# comando_24V.net
KiCad netlist of a schematic drawn in EAGLE
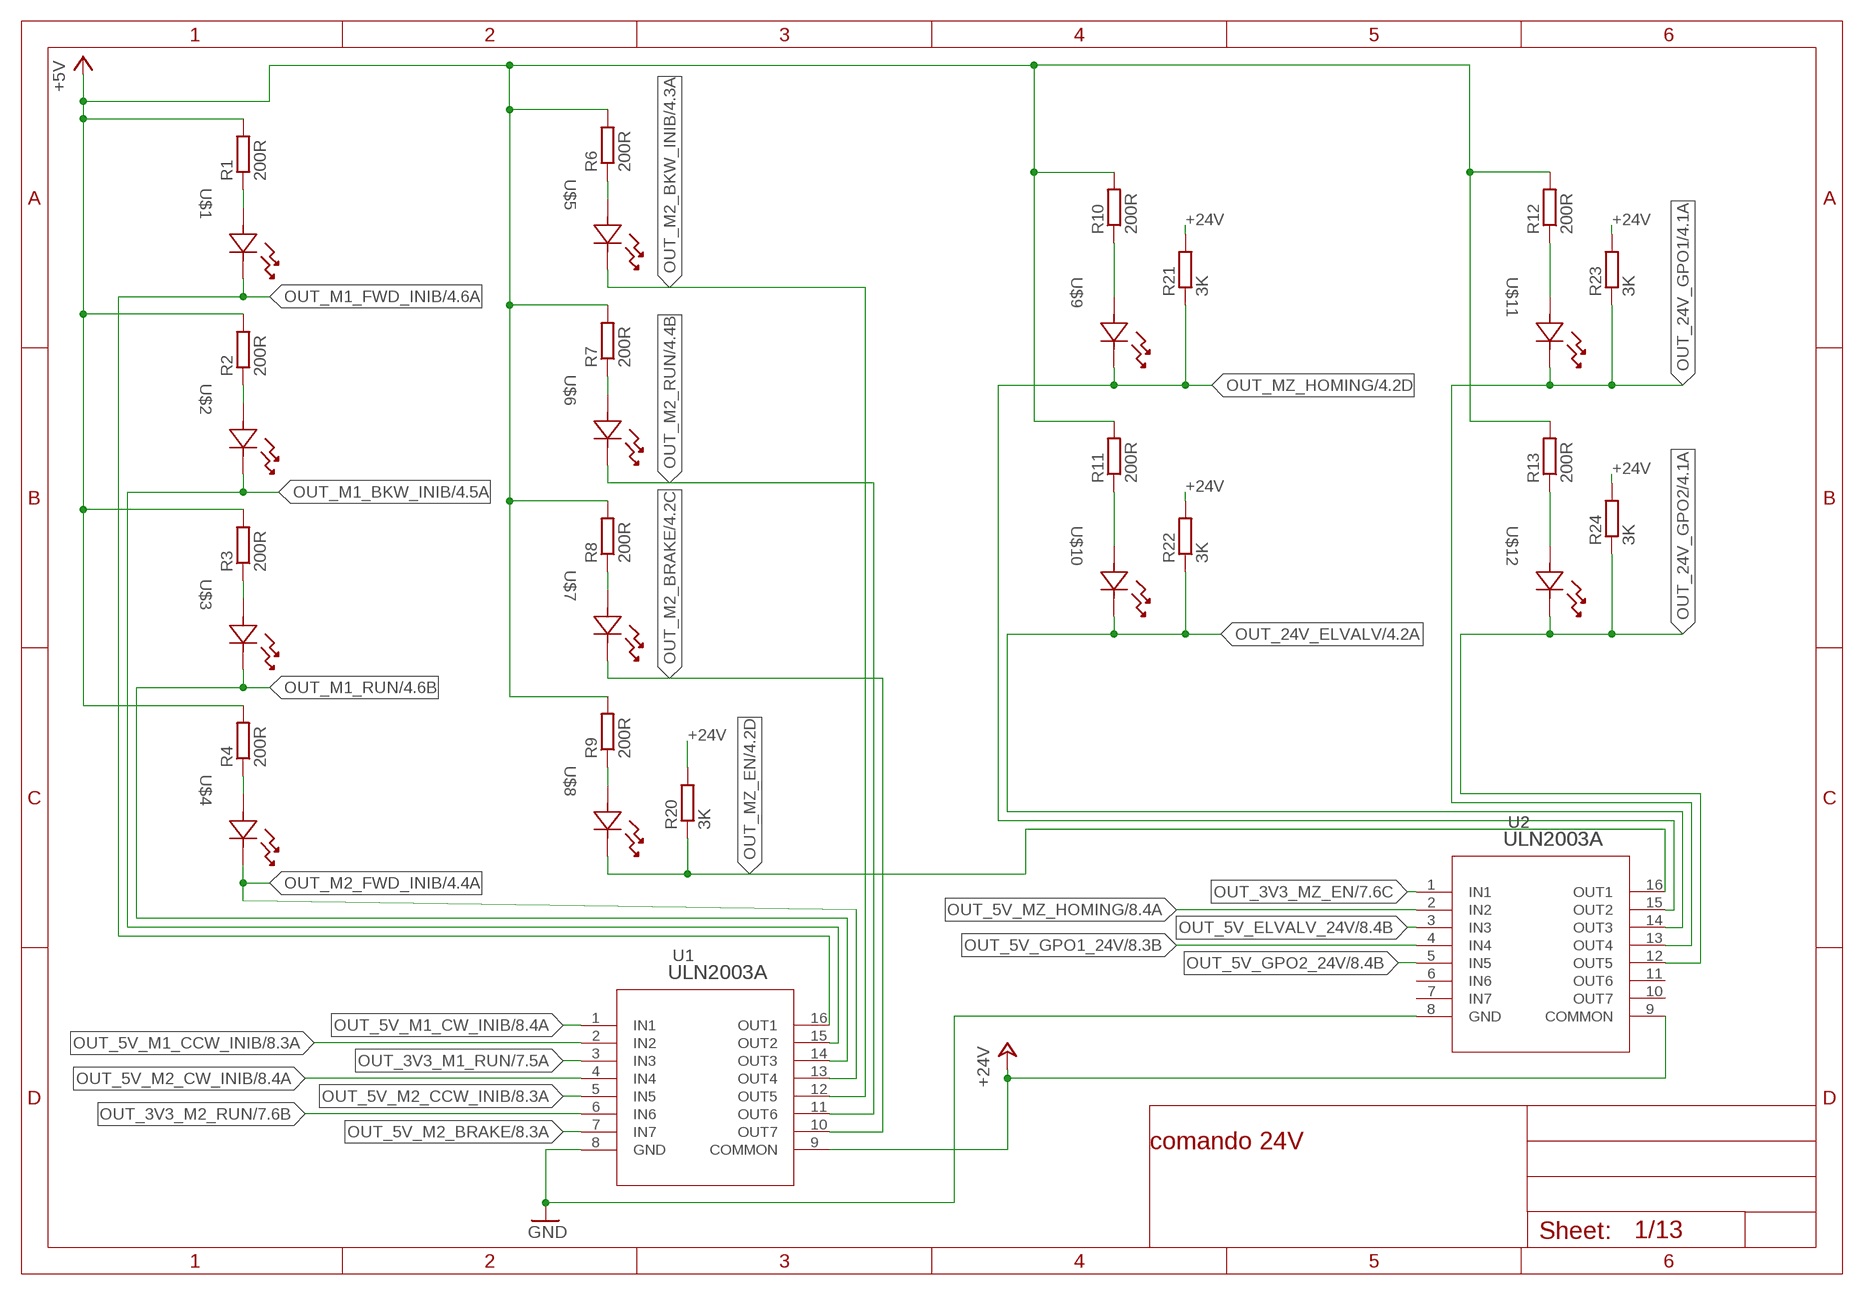
[diagram p0: schematic, sheet 1]
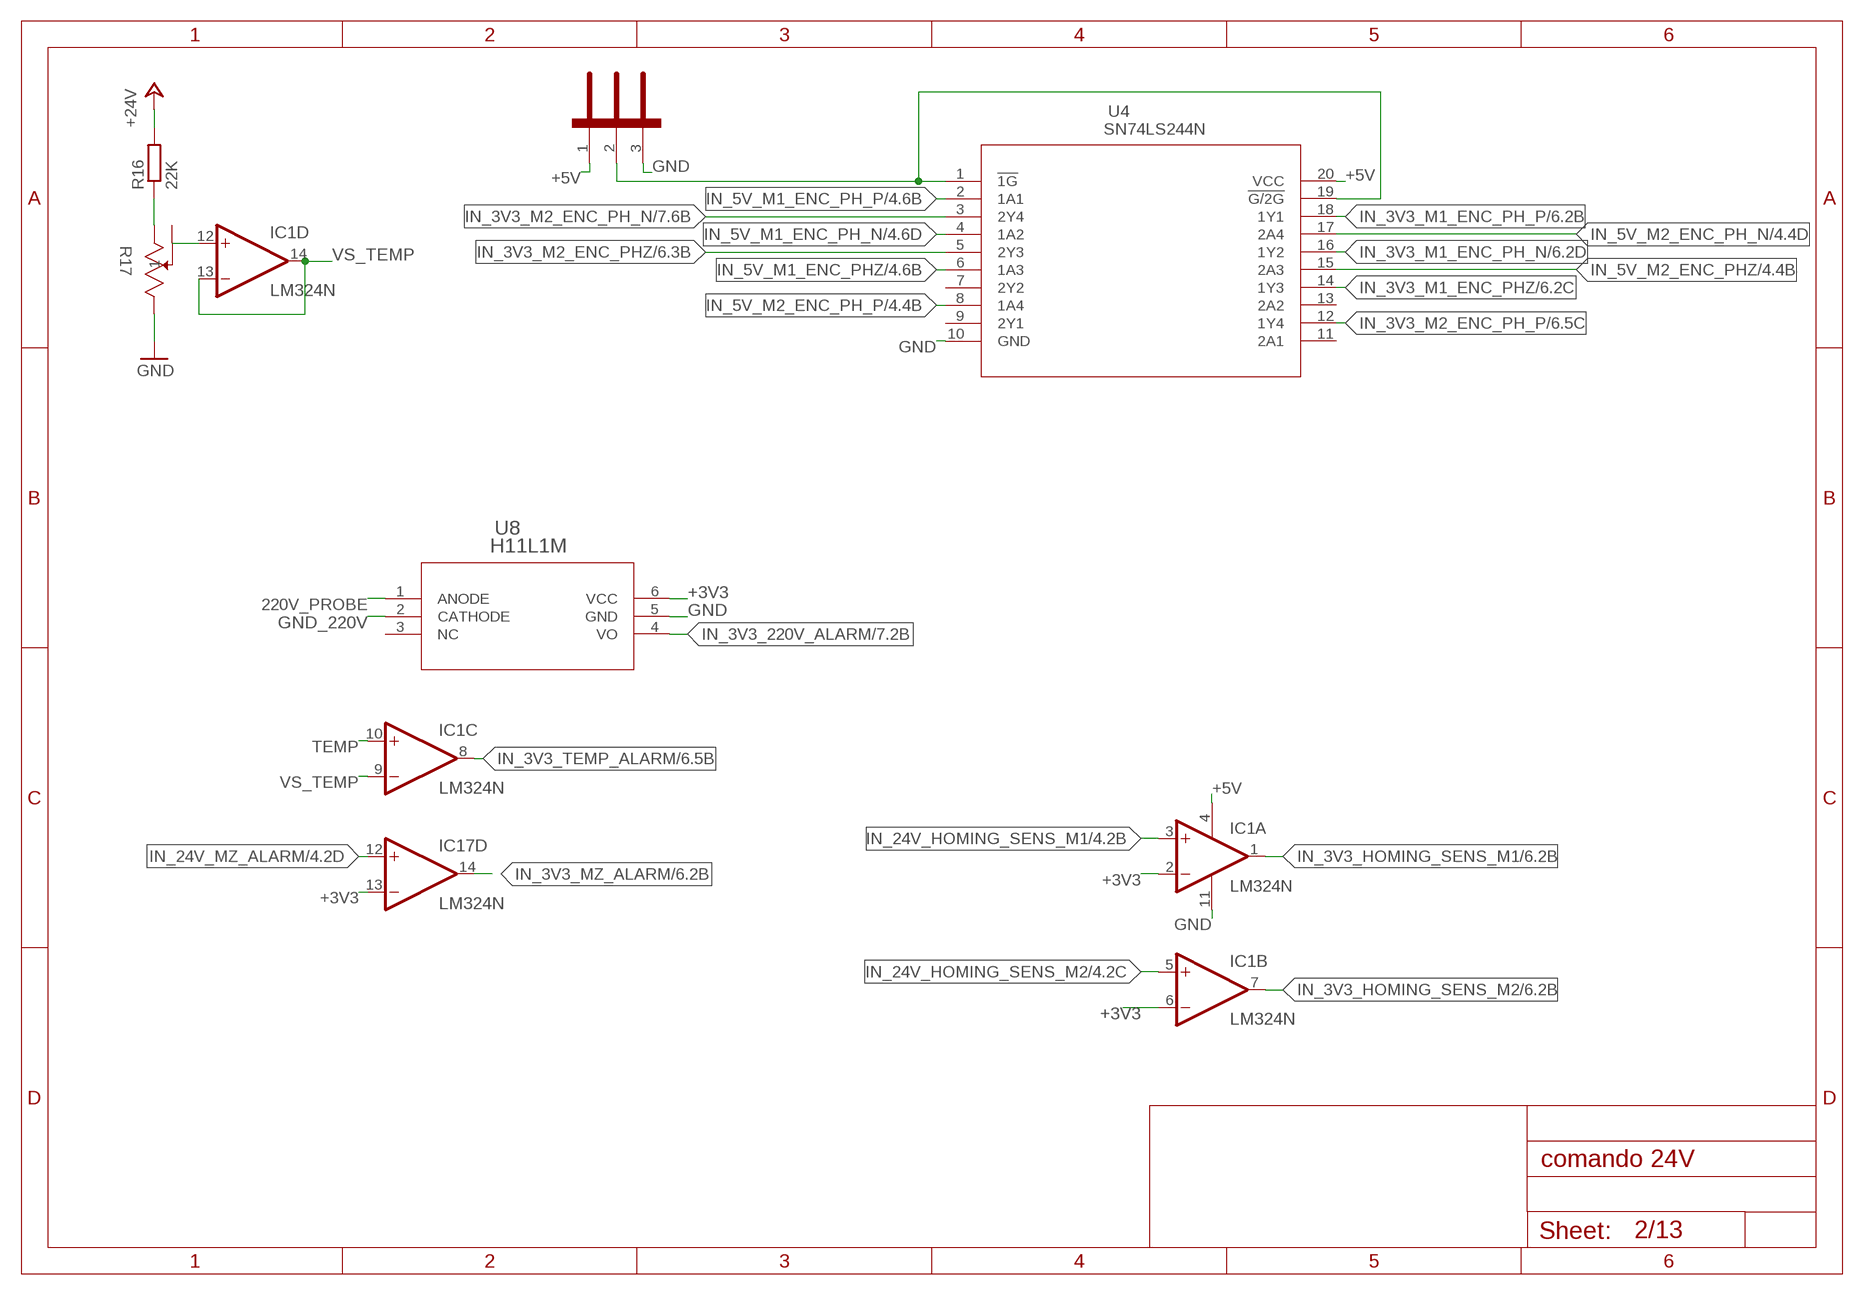
[diagram p1: schematic, sheet 2]
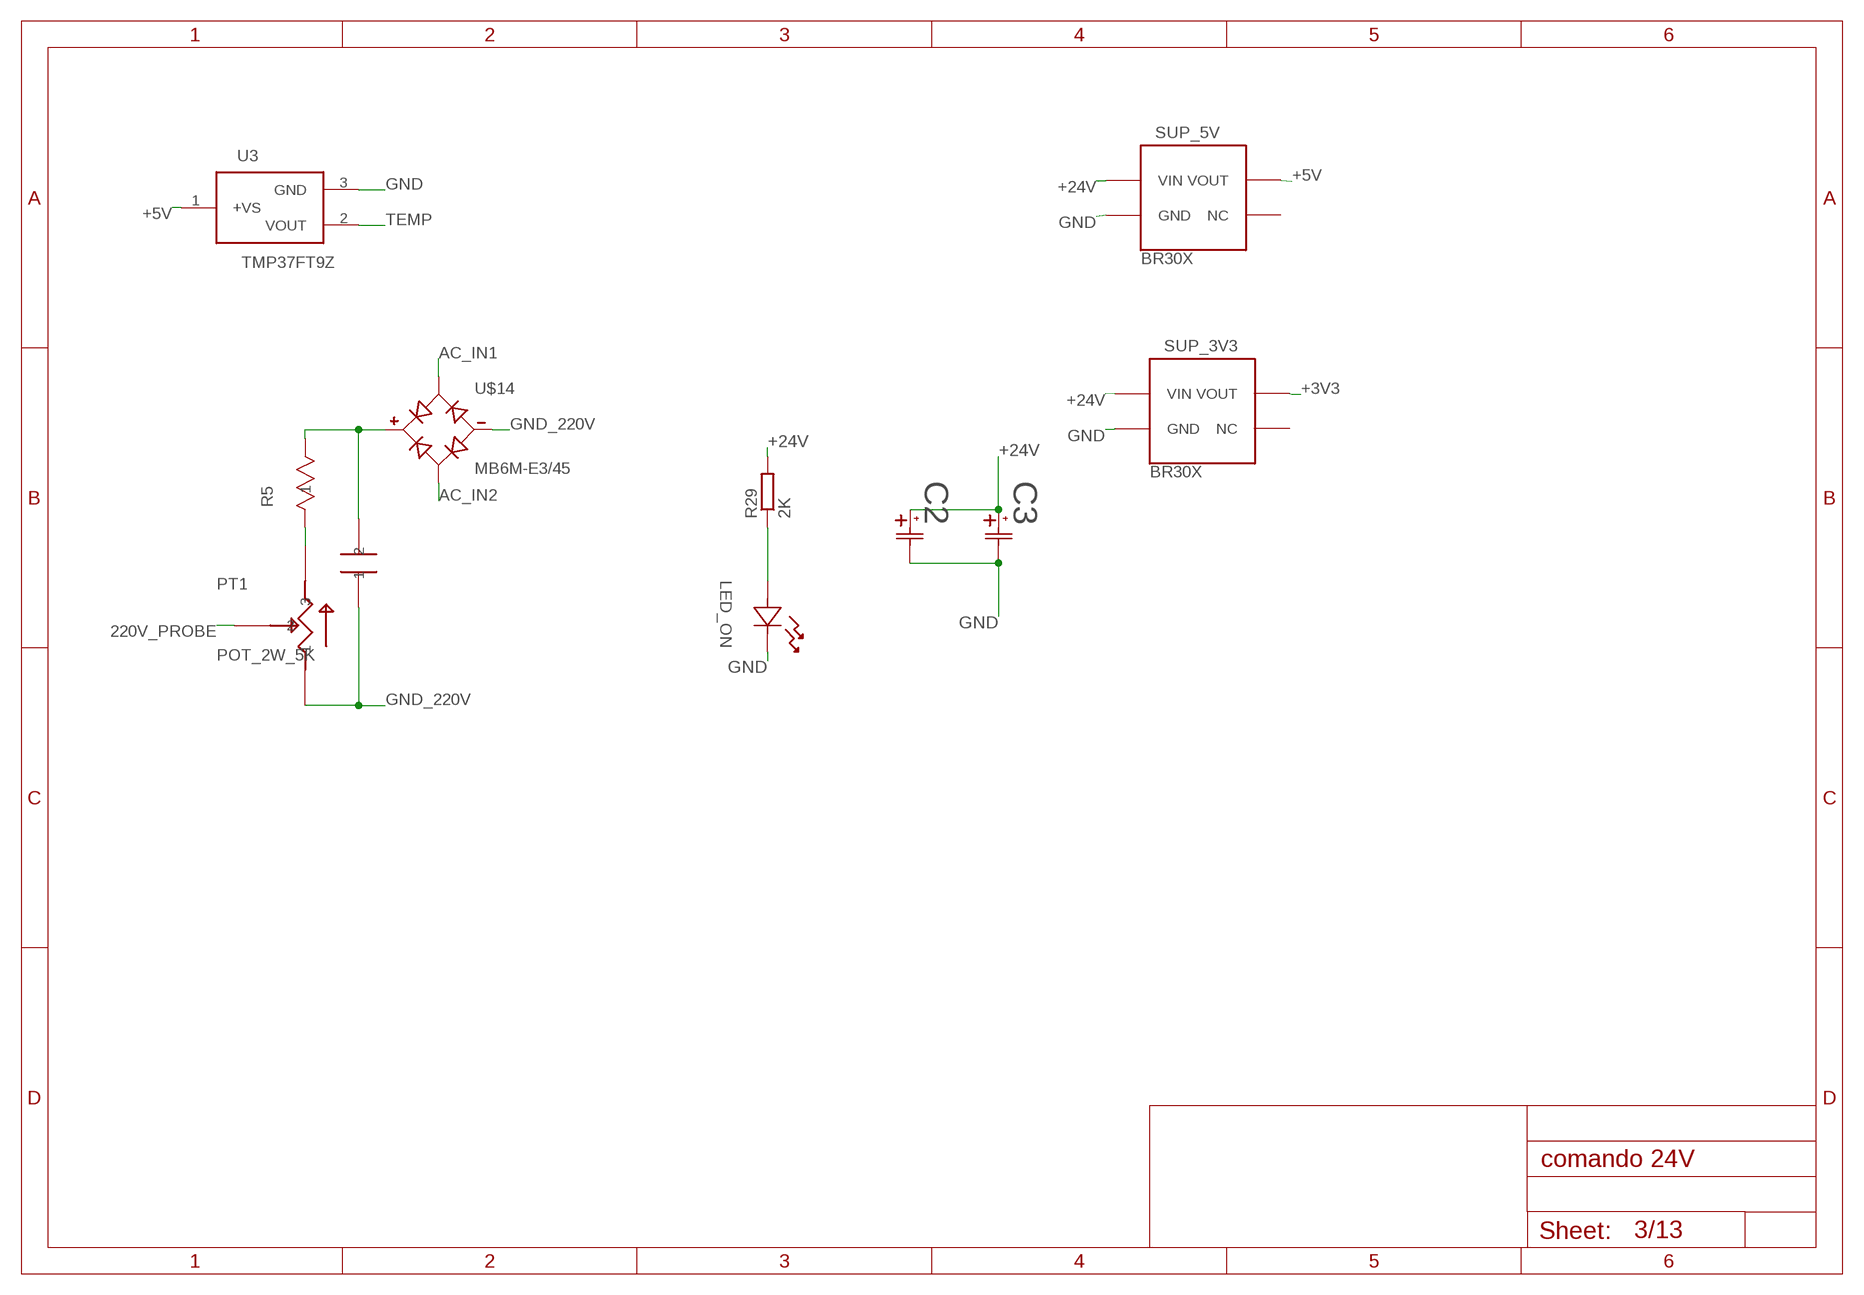
[diagram p2: schematic, sheet 3]
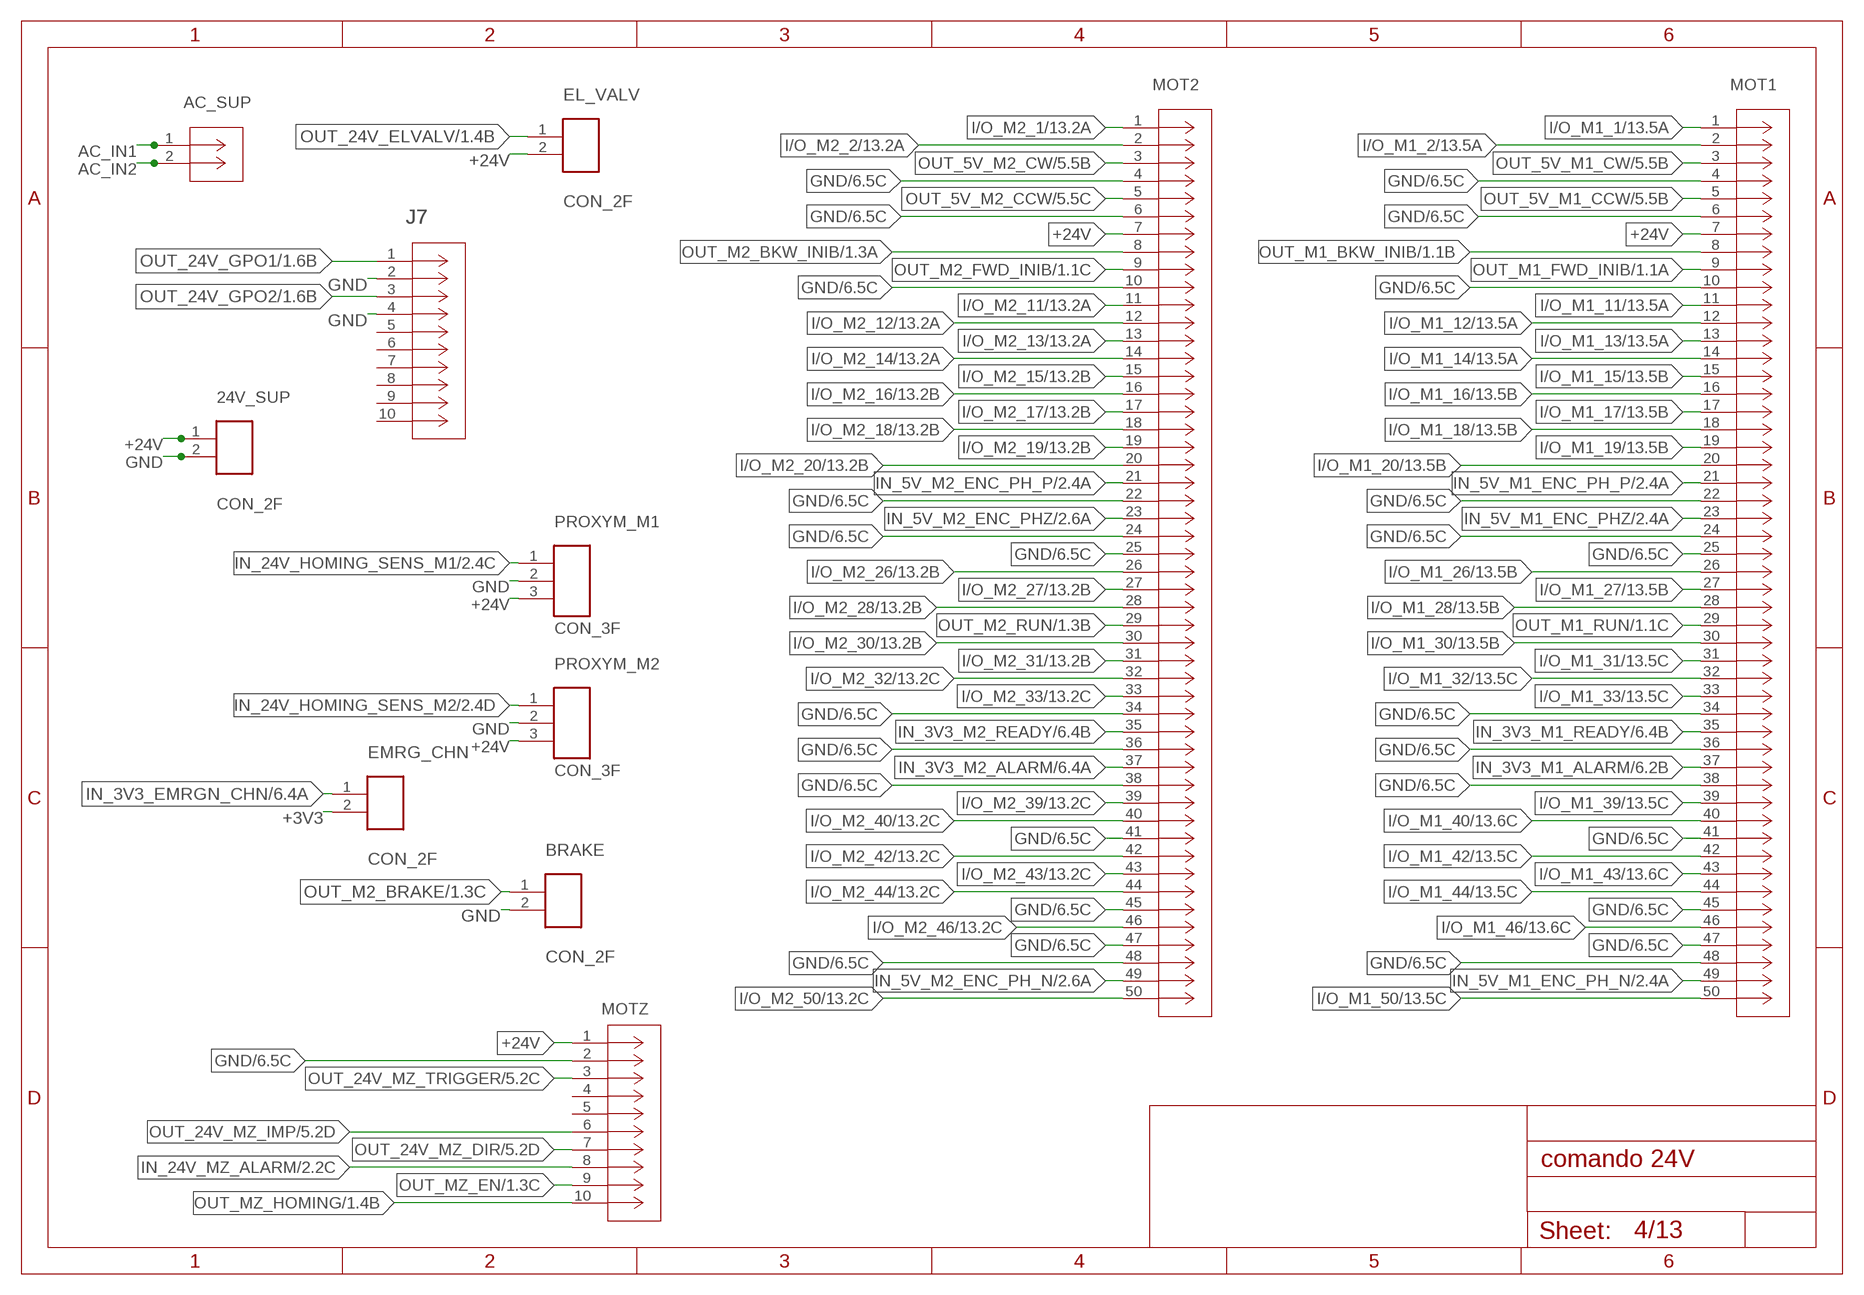
[diagram p3: schematic, sheet 4]
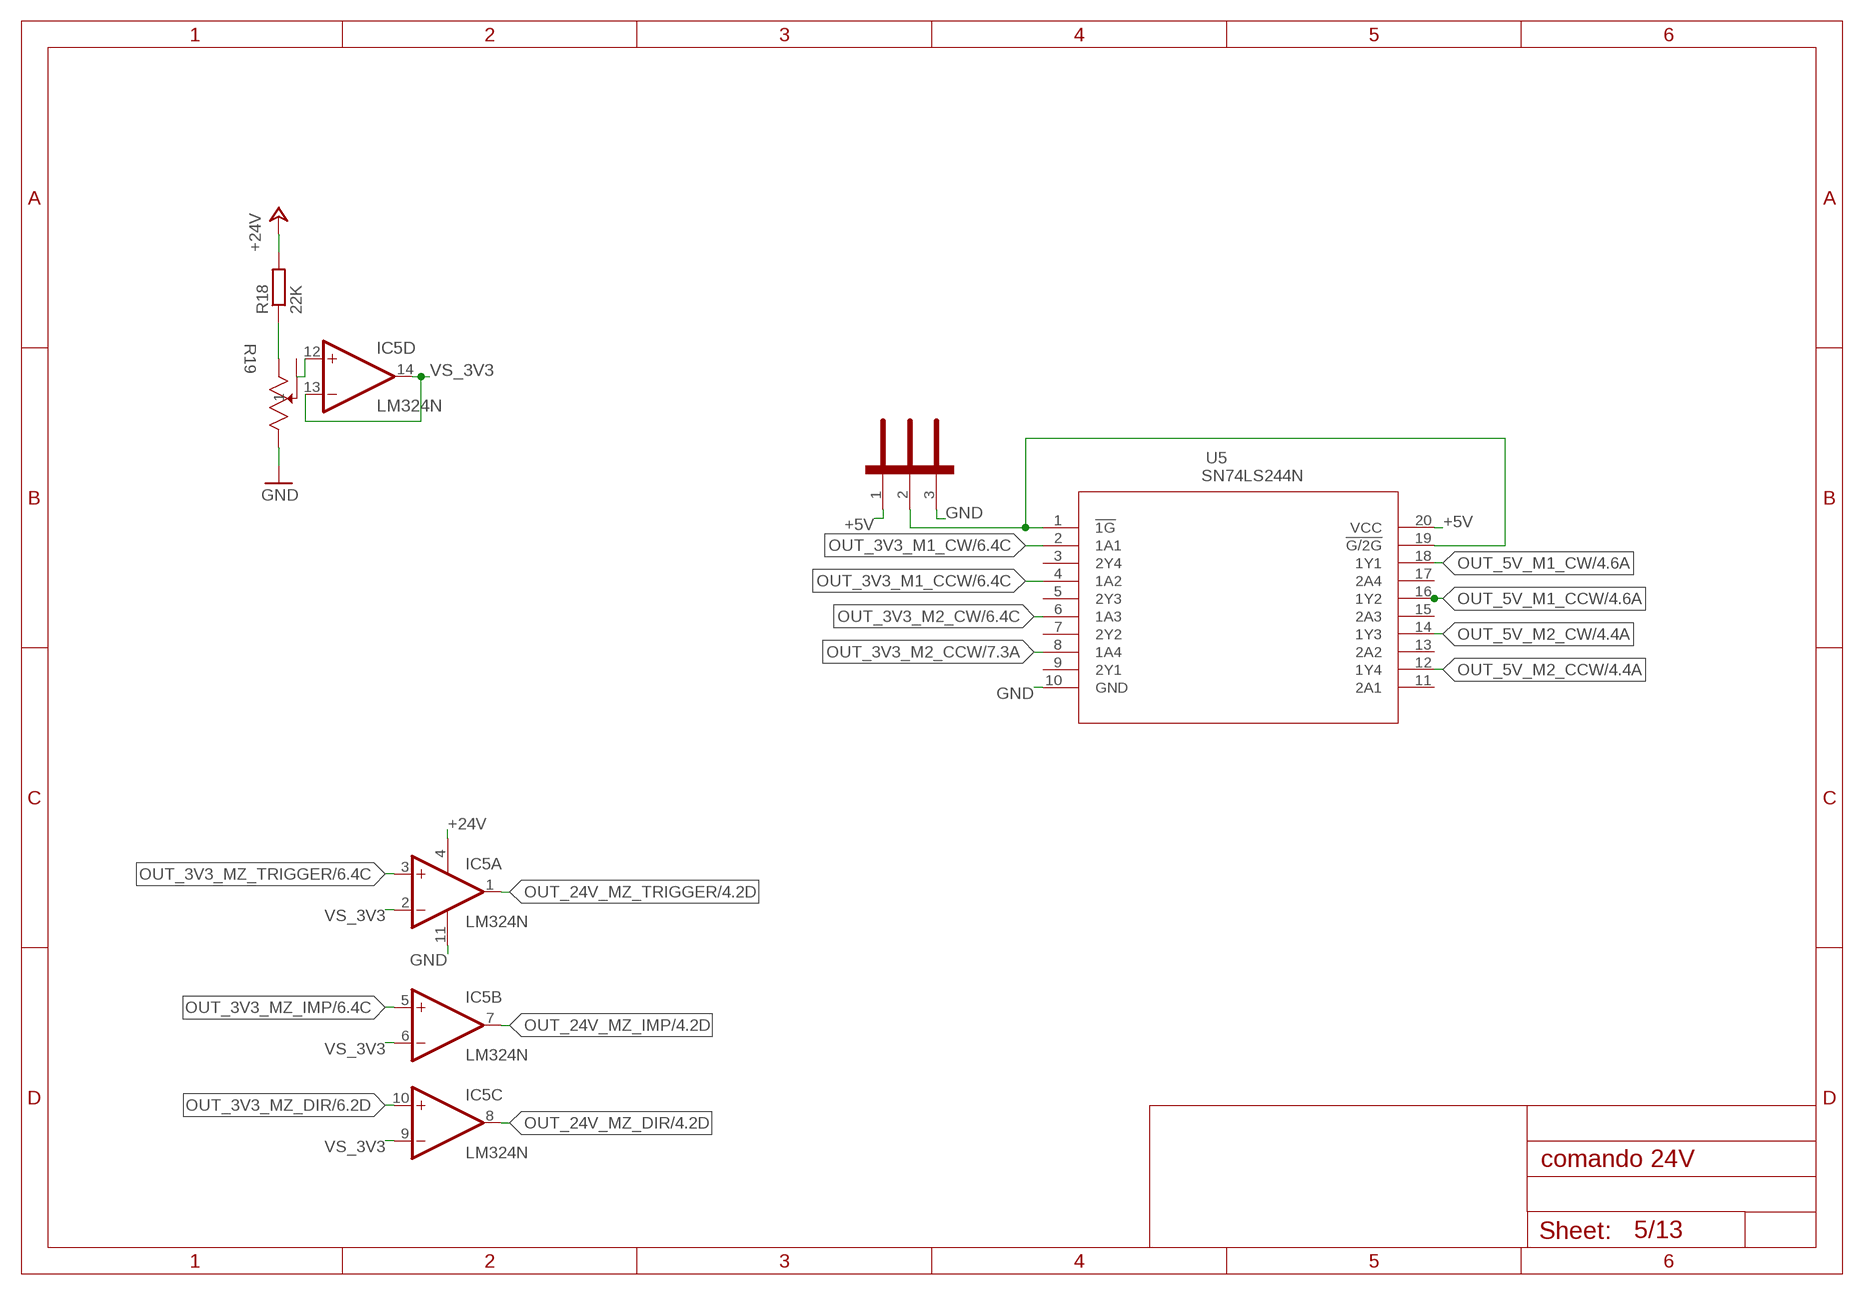
[diagram p4: schematic, sheet 5]
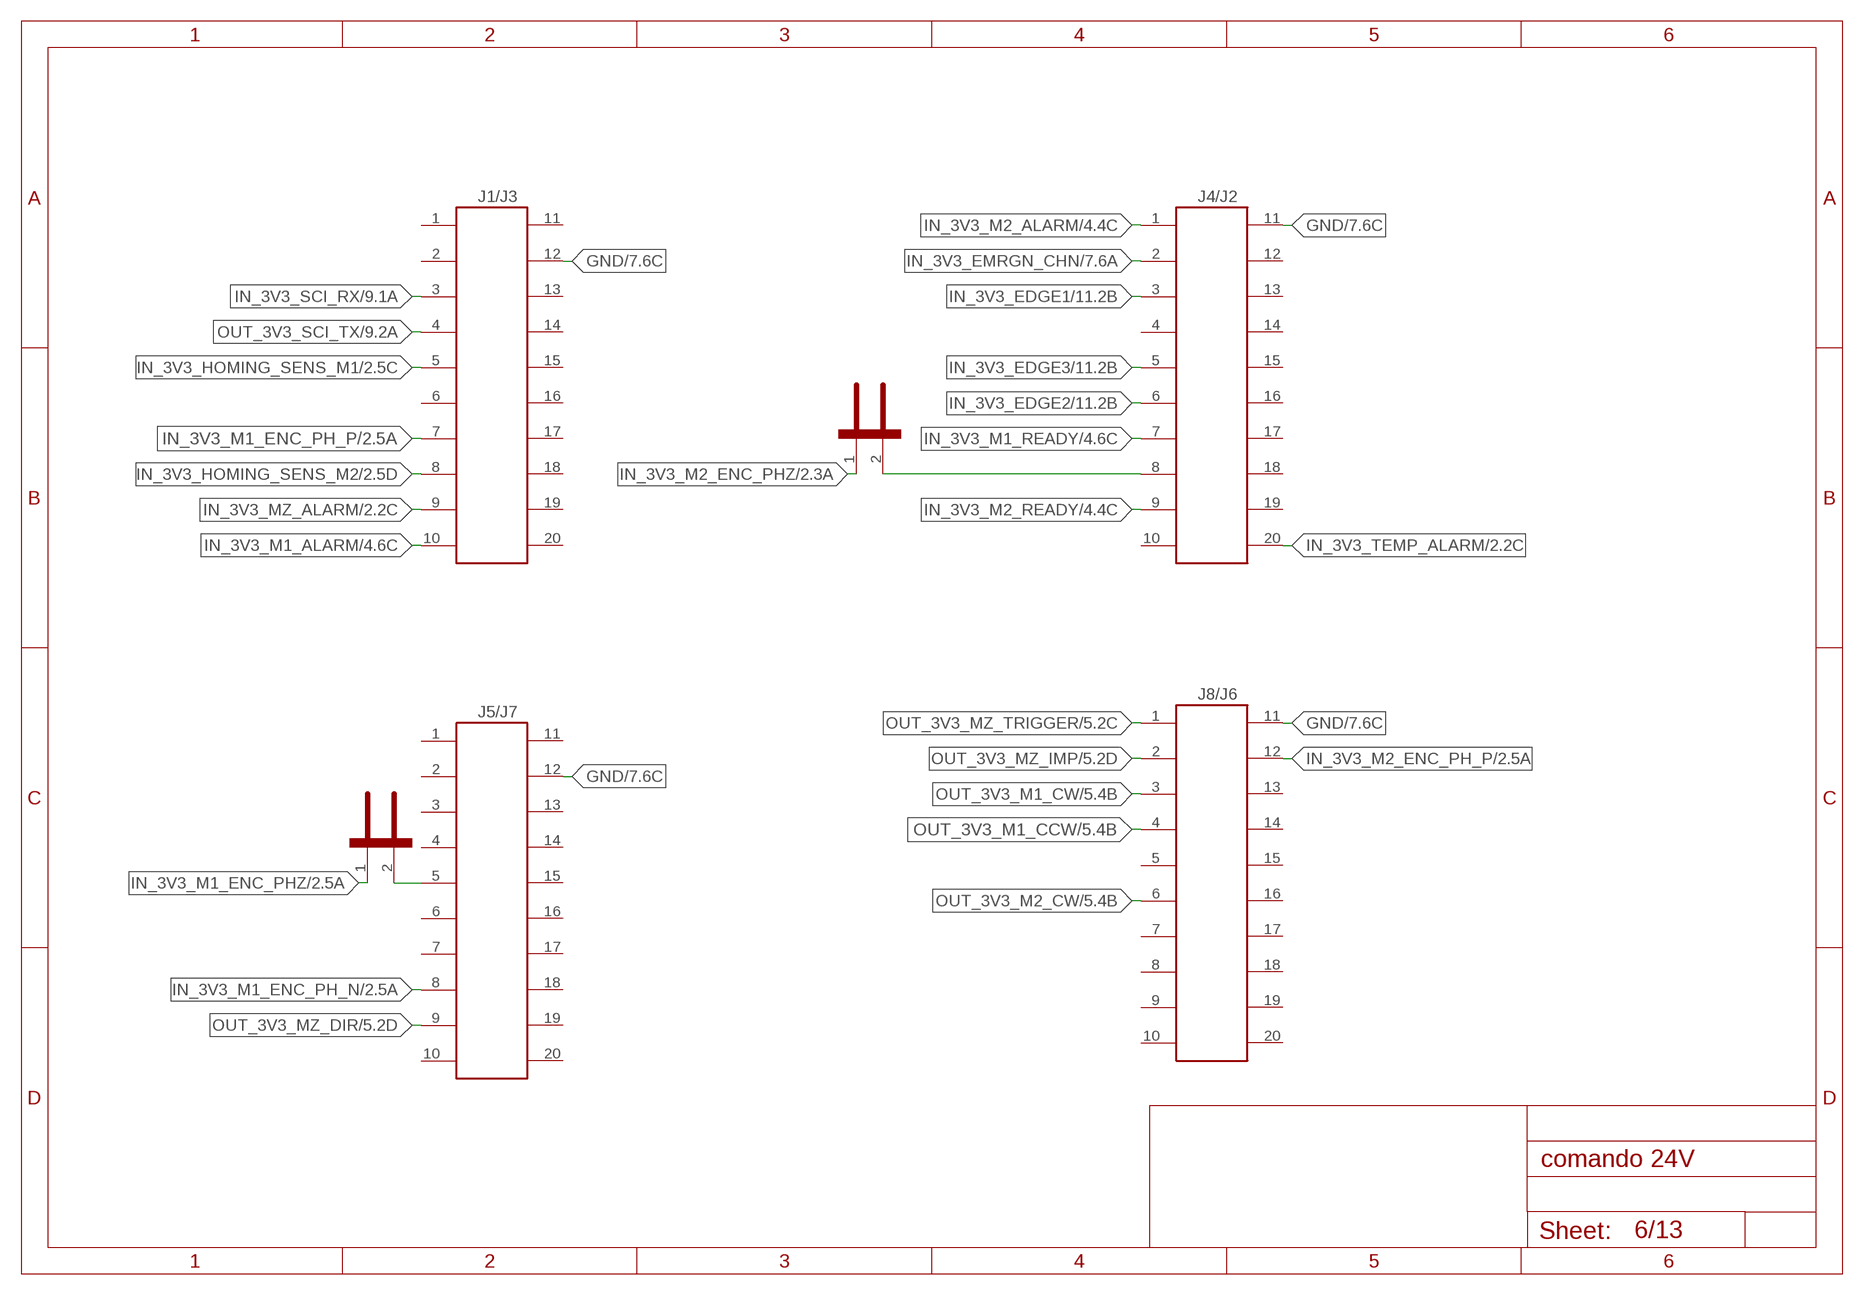
[diagram p5: schematic, sheet 6]
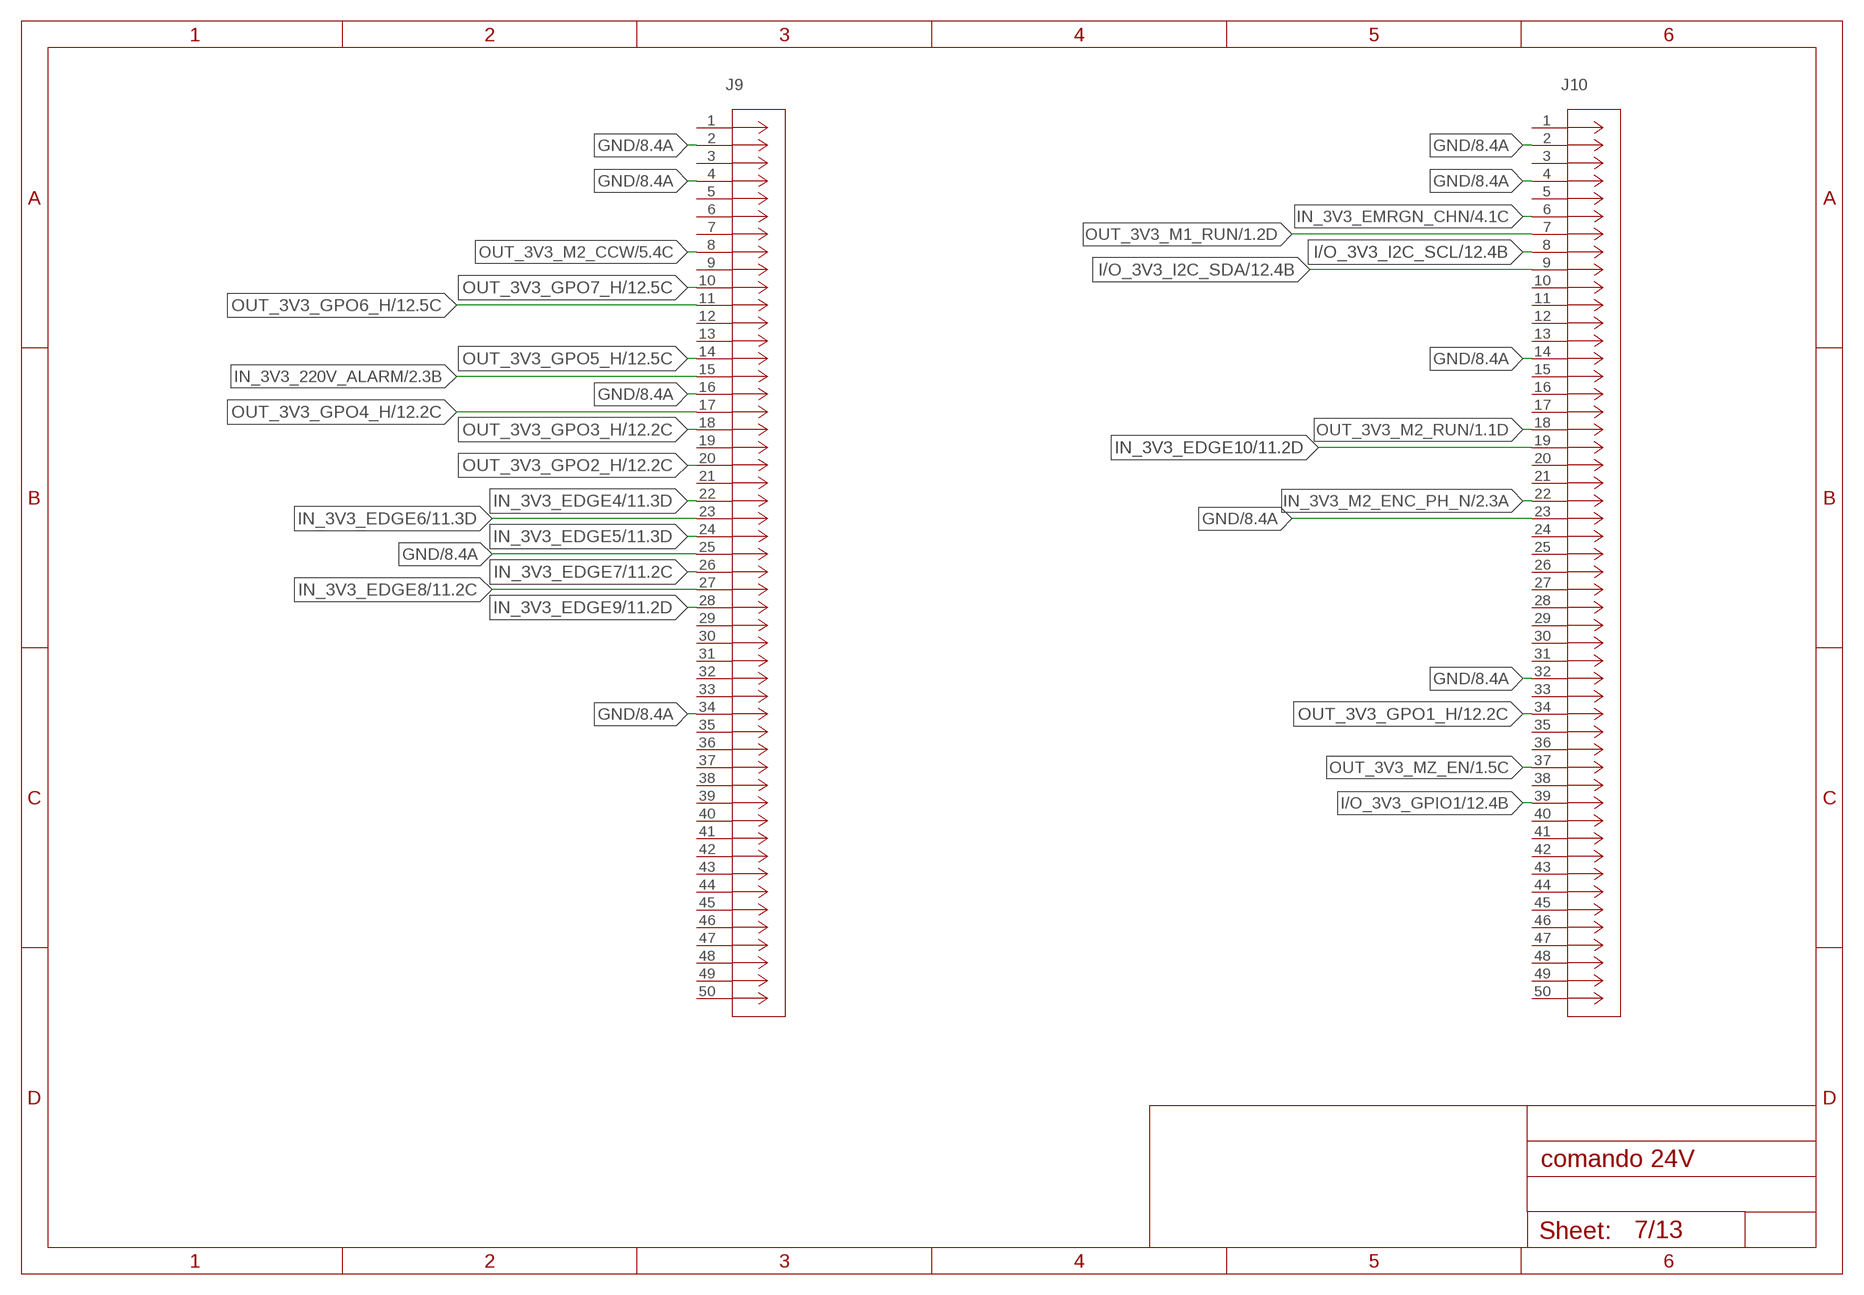
[diagram p6: schematic, sheet 7]
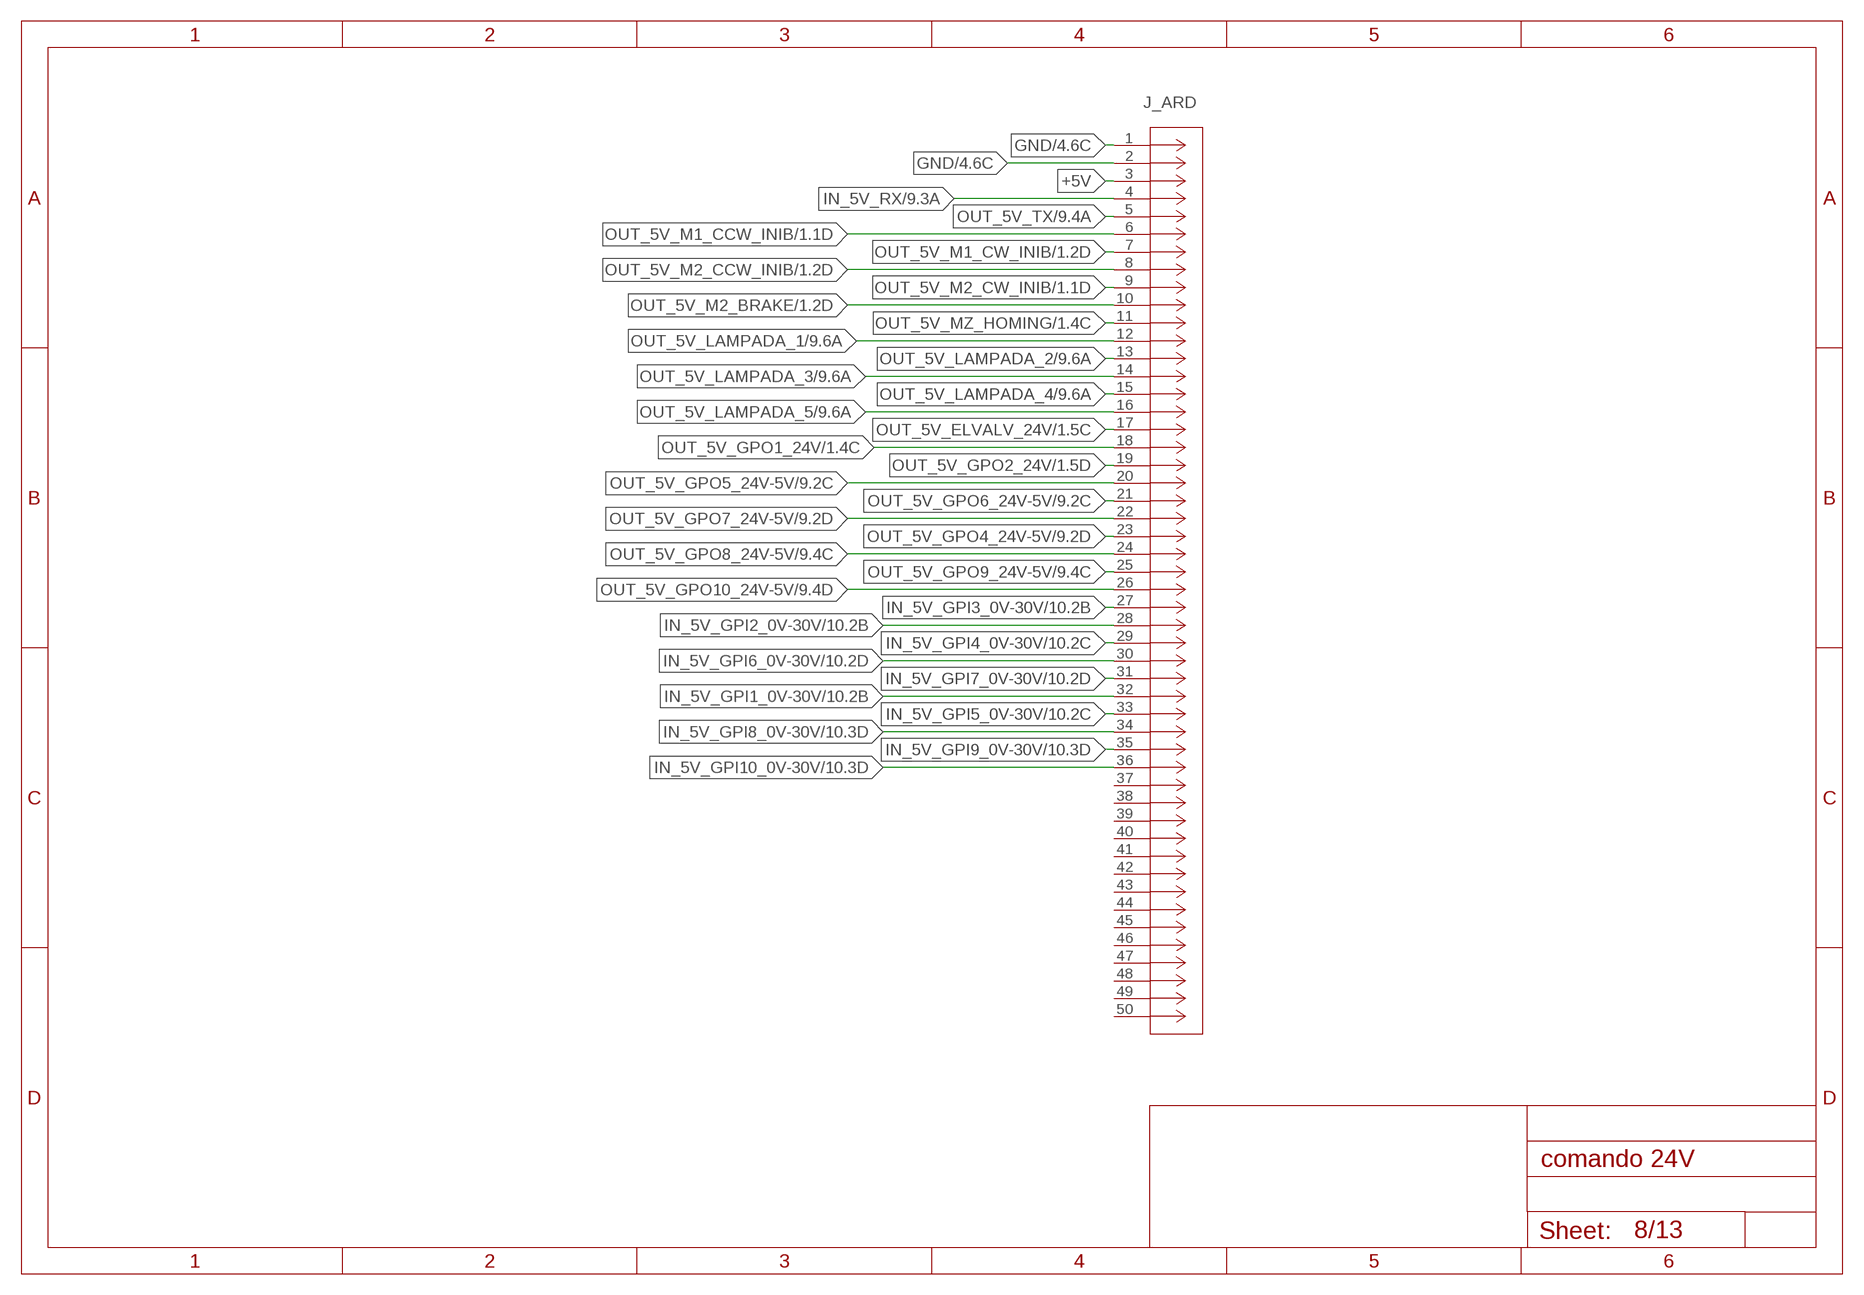
[diagram p7: schematic, sheet 8]
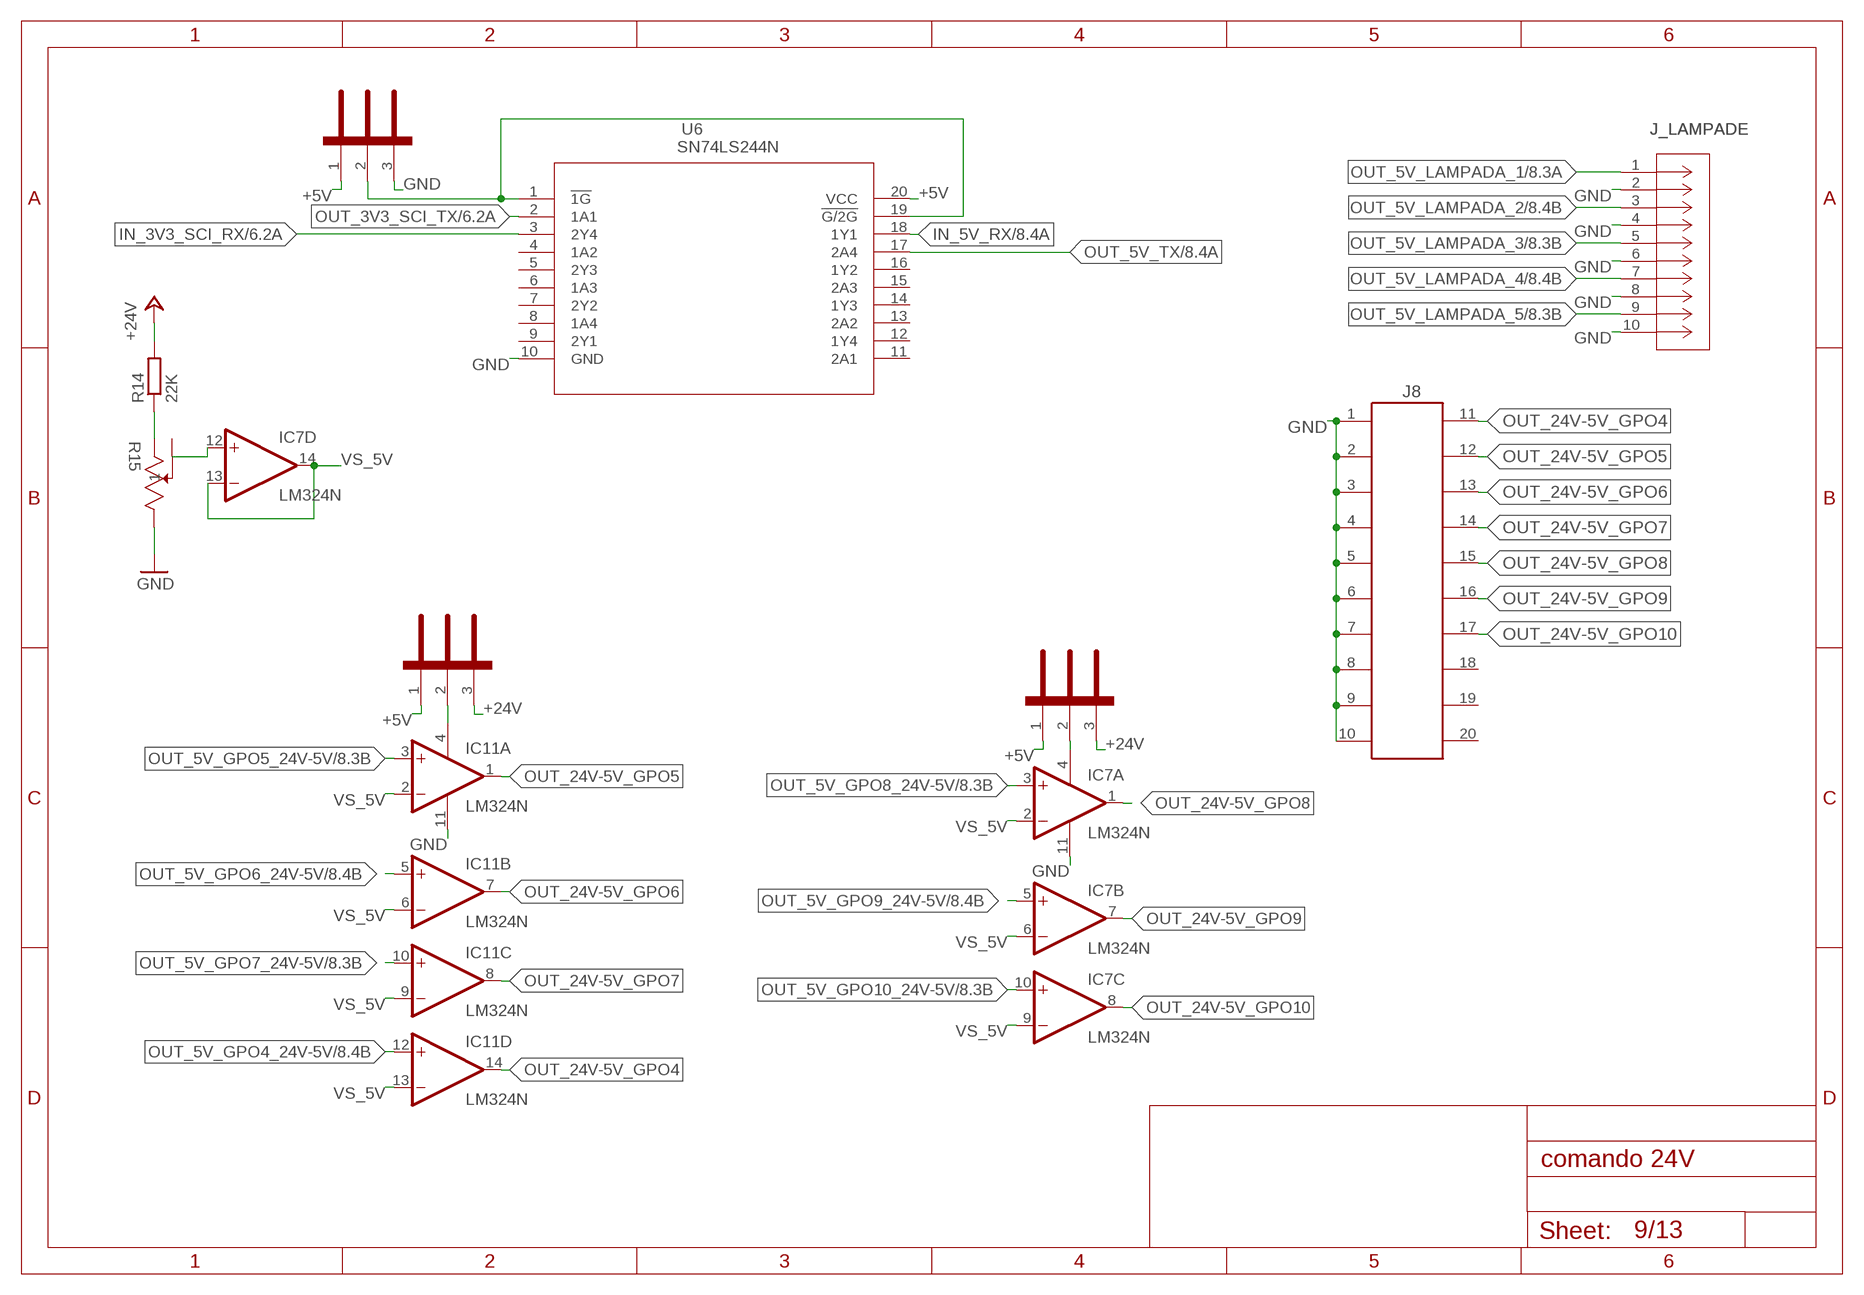
[diagram p8: schematic, sheet 9]
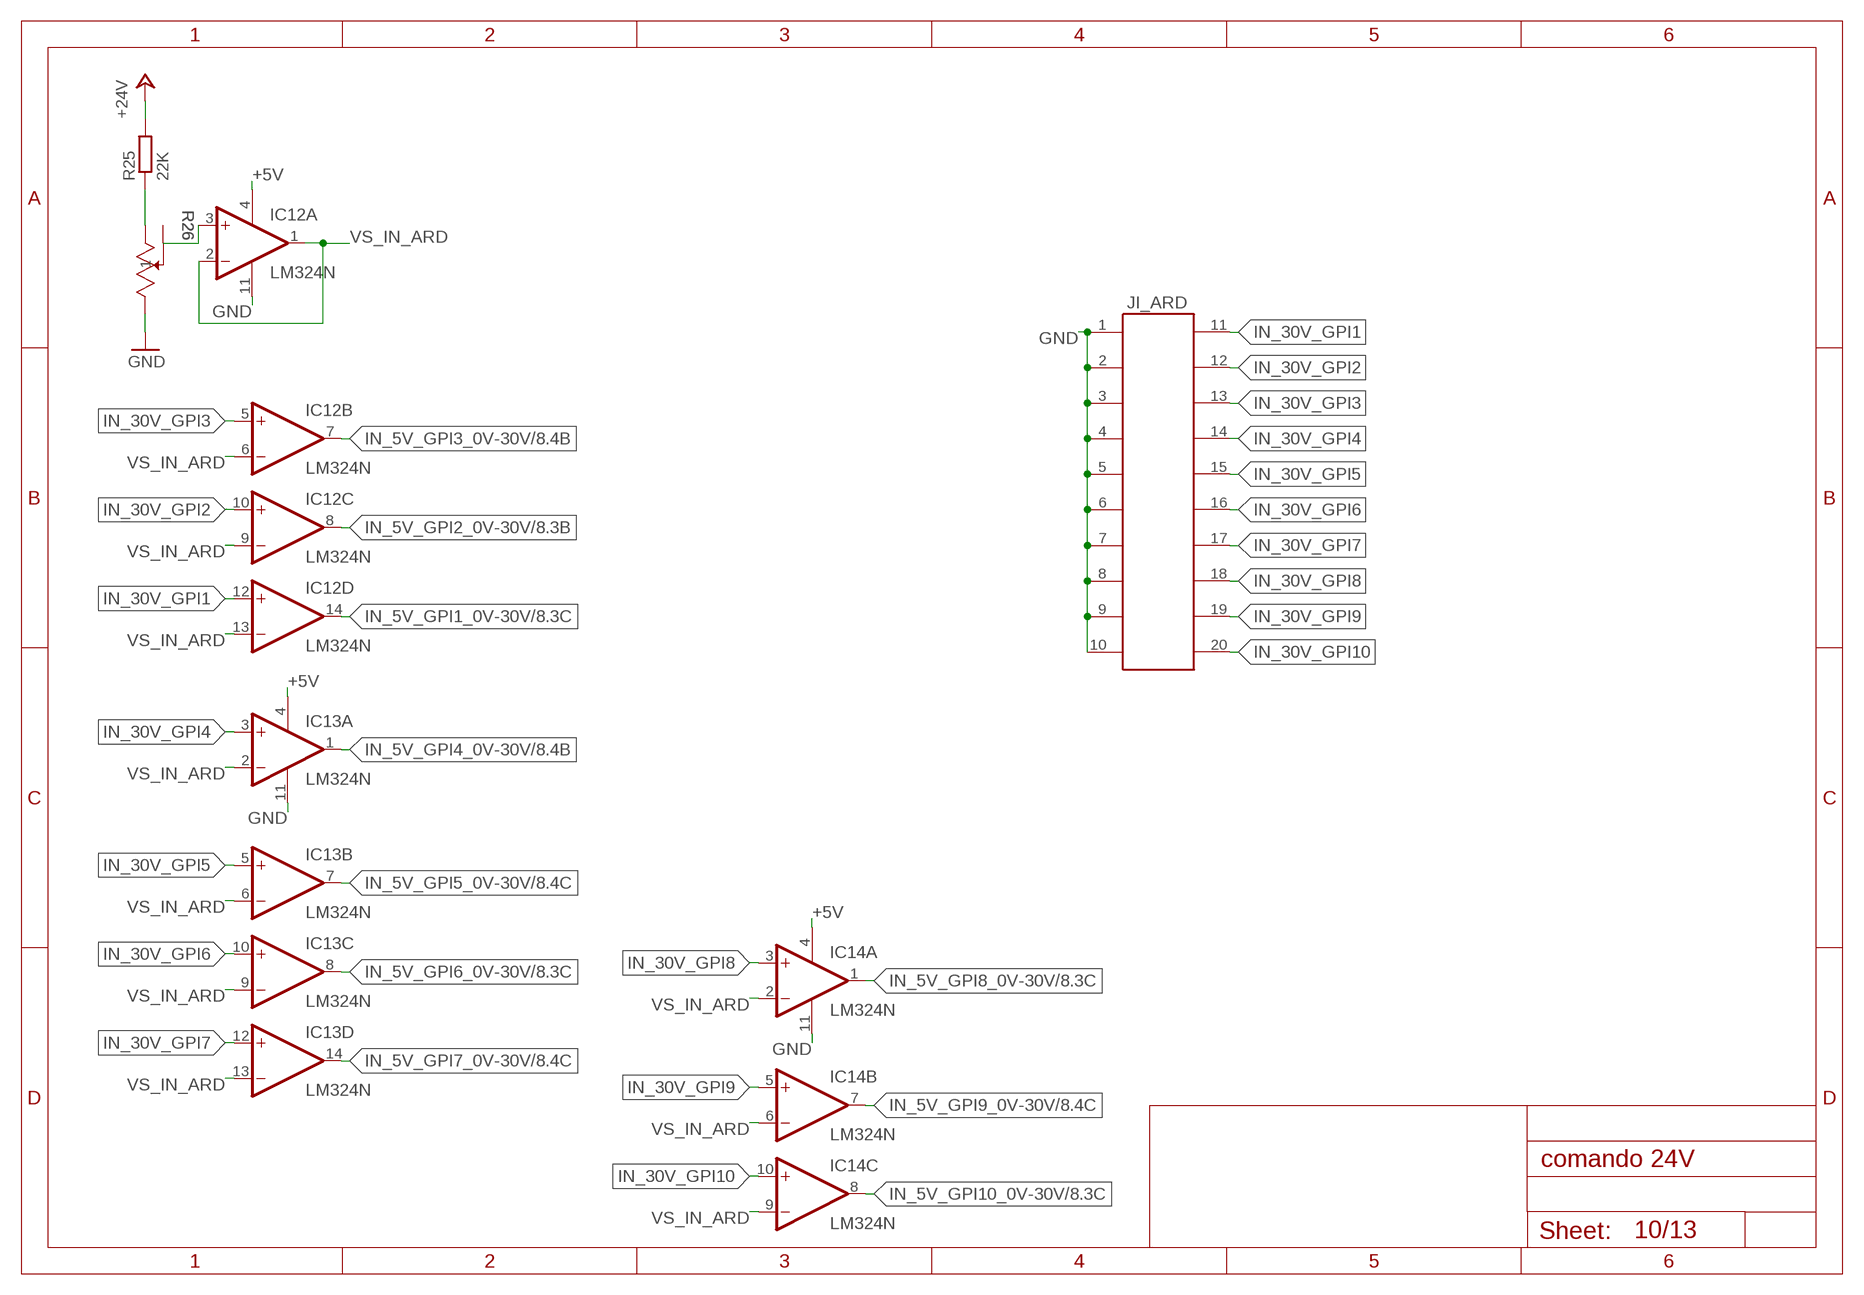
[diagram p9: schematic, sheet 10]
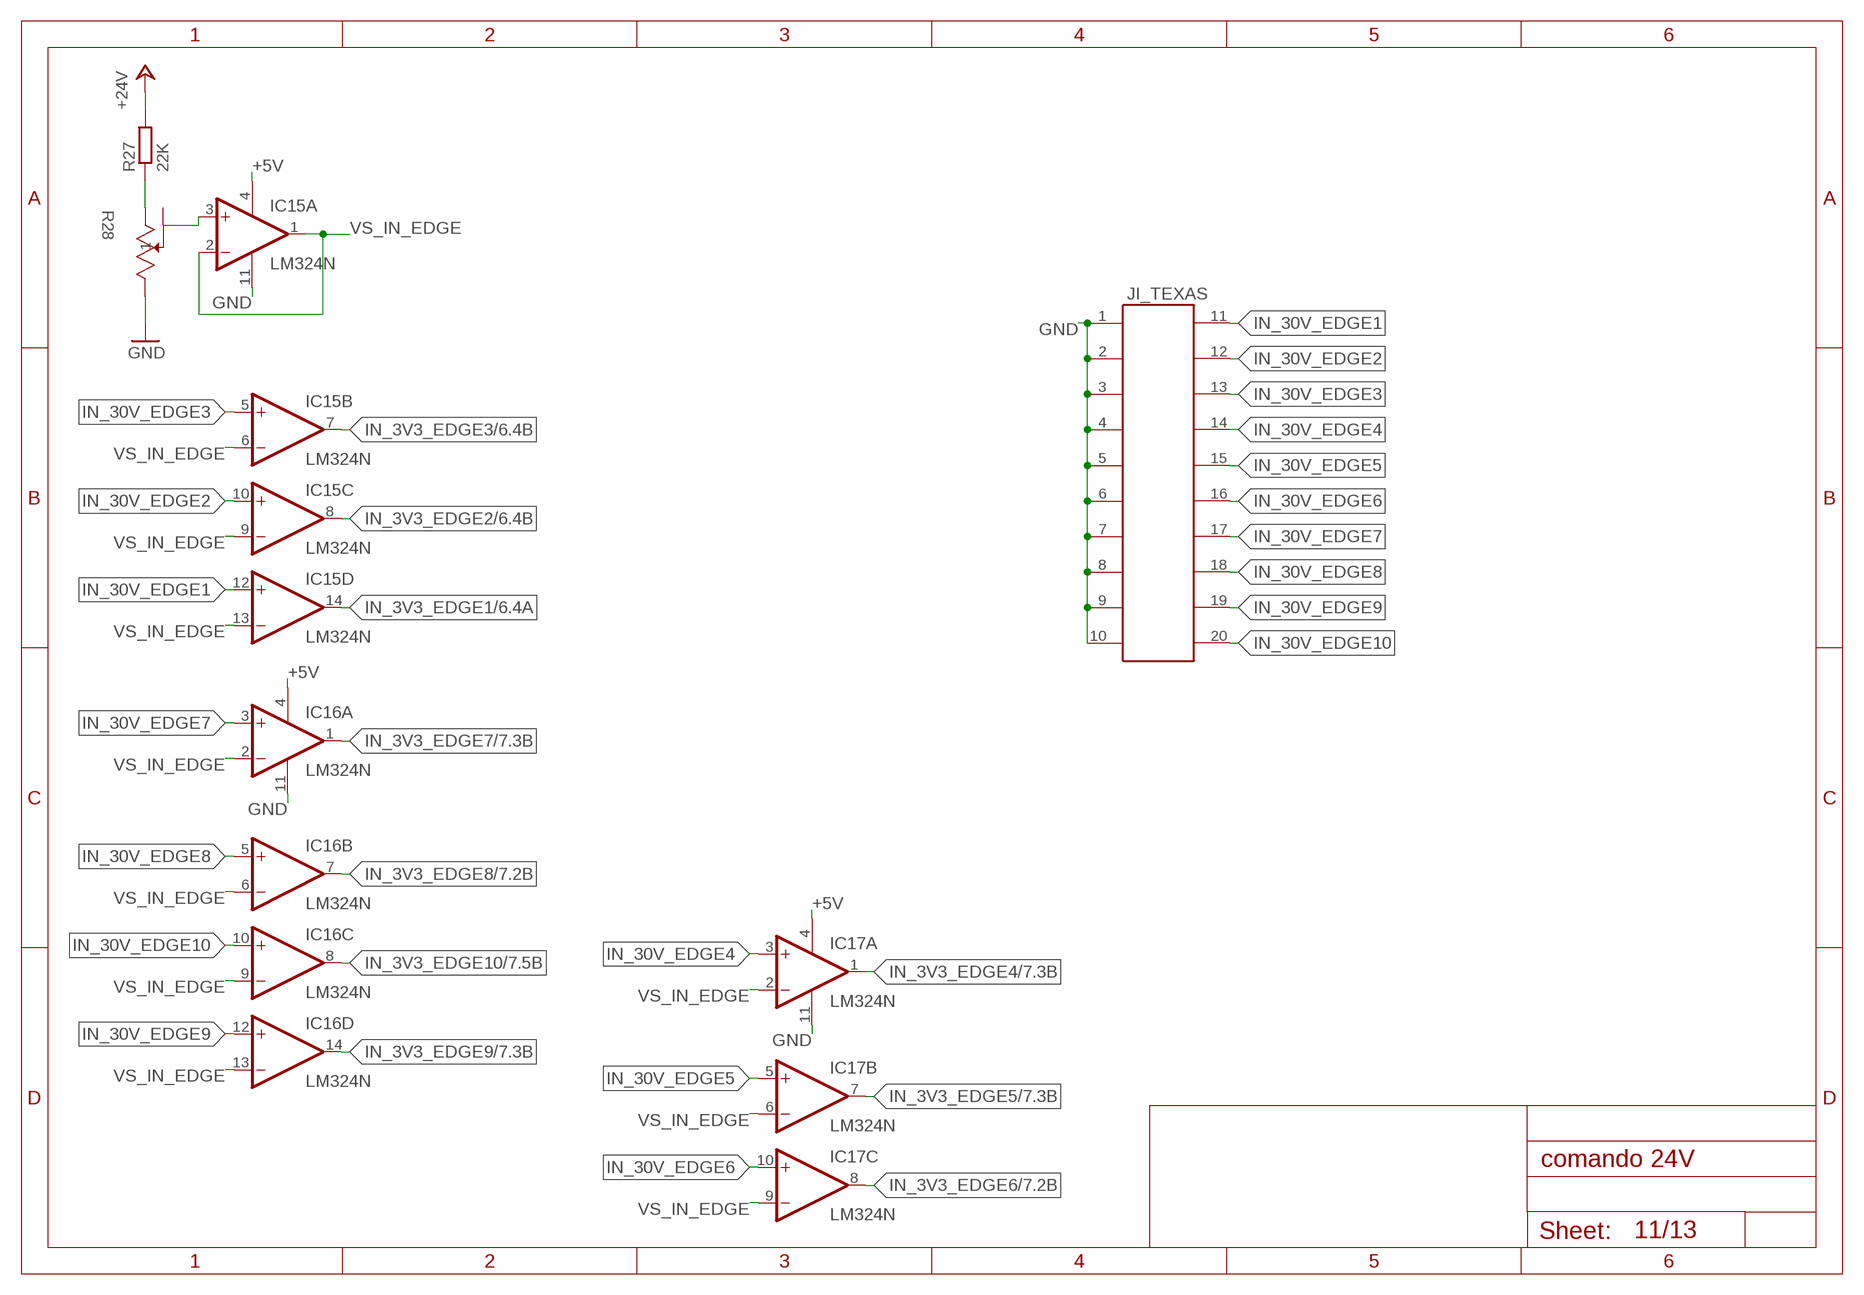
[diagram p10: schematic, sheet 11]
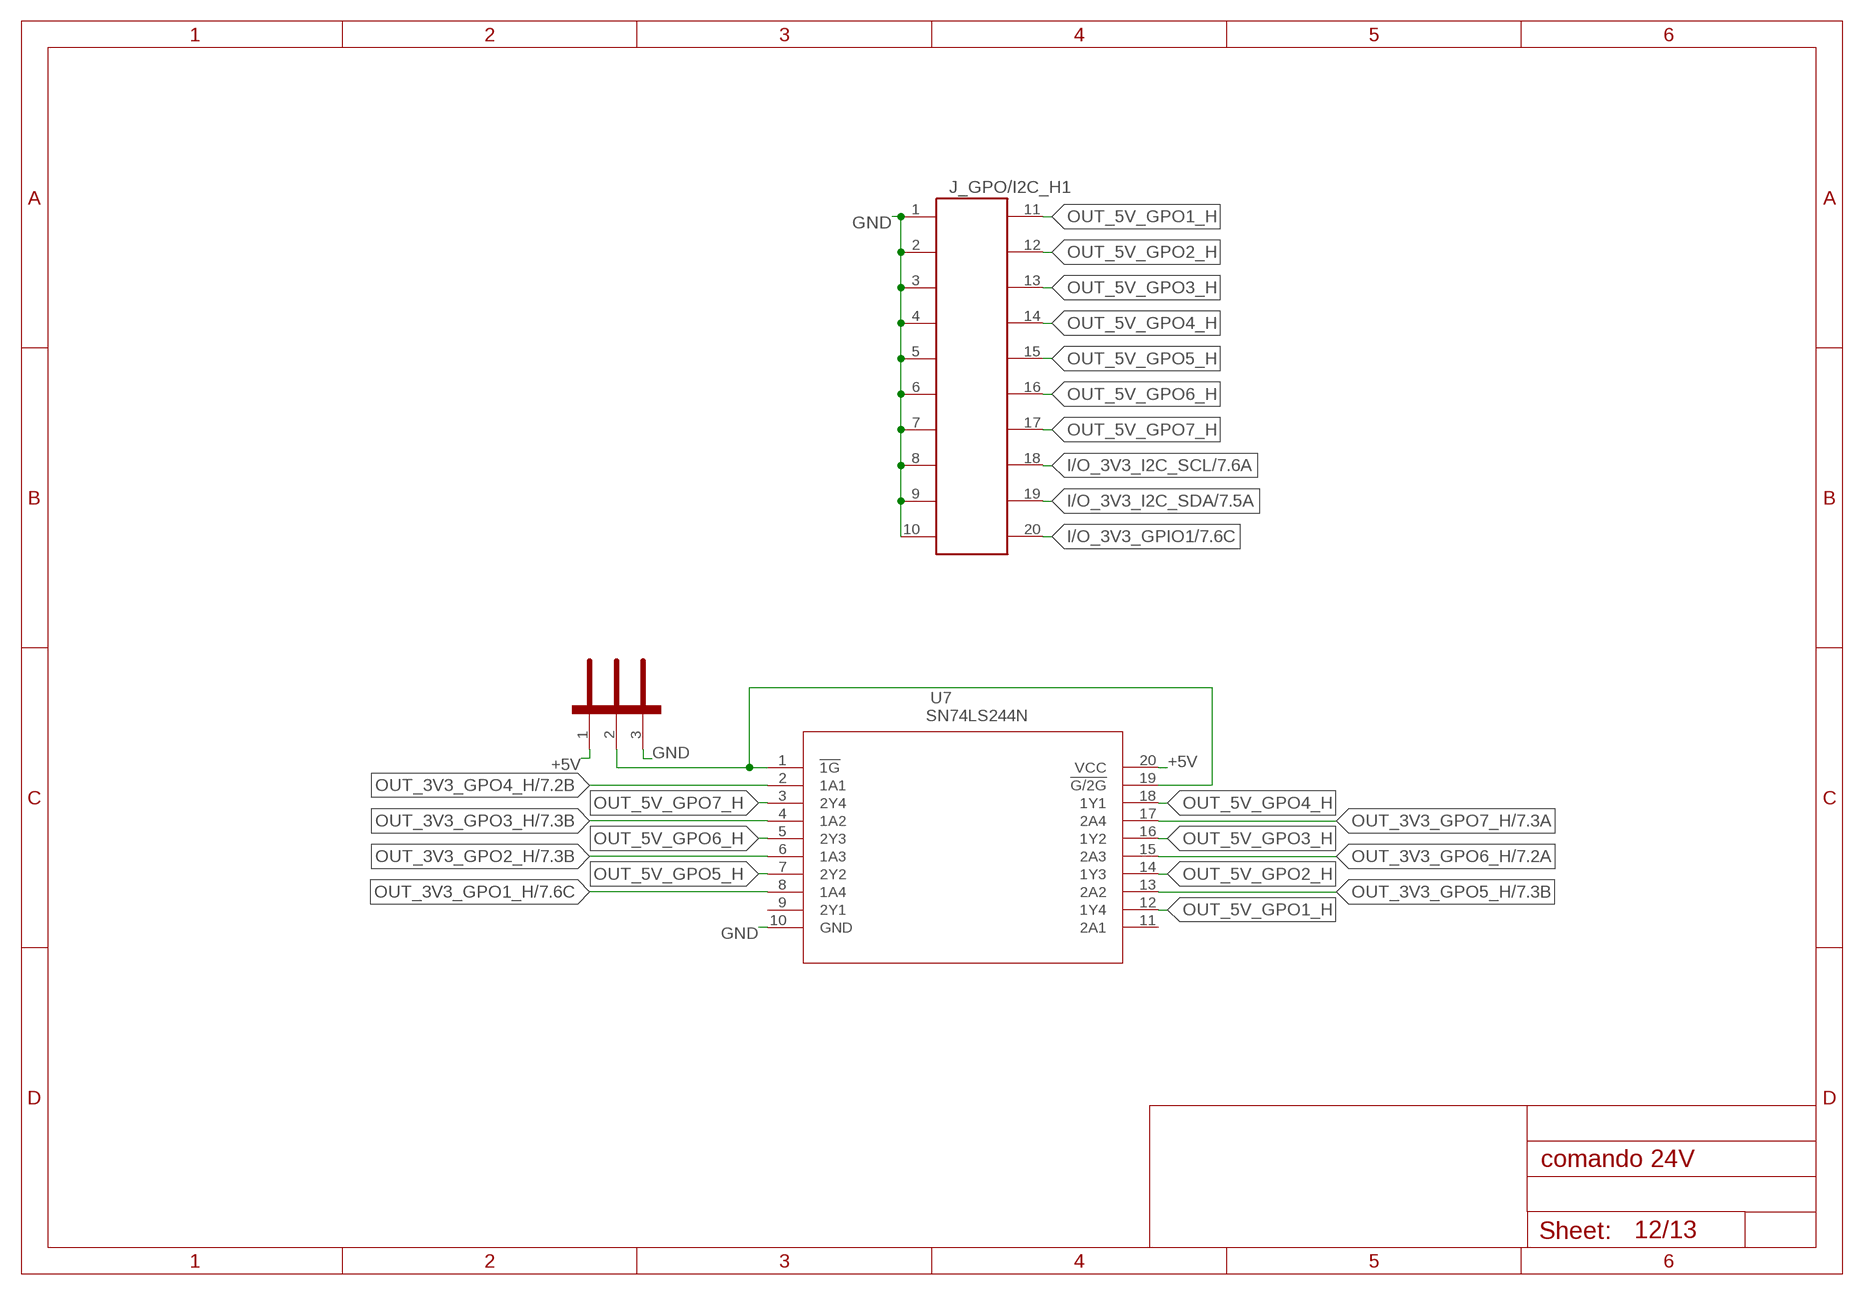
[diagram p11: schematic, sheet 12]
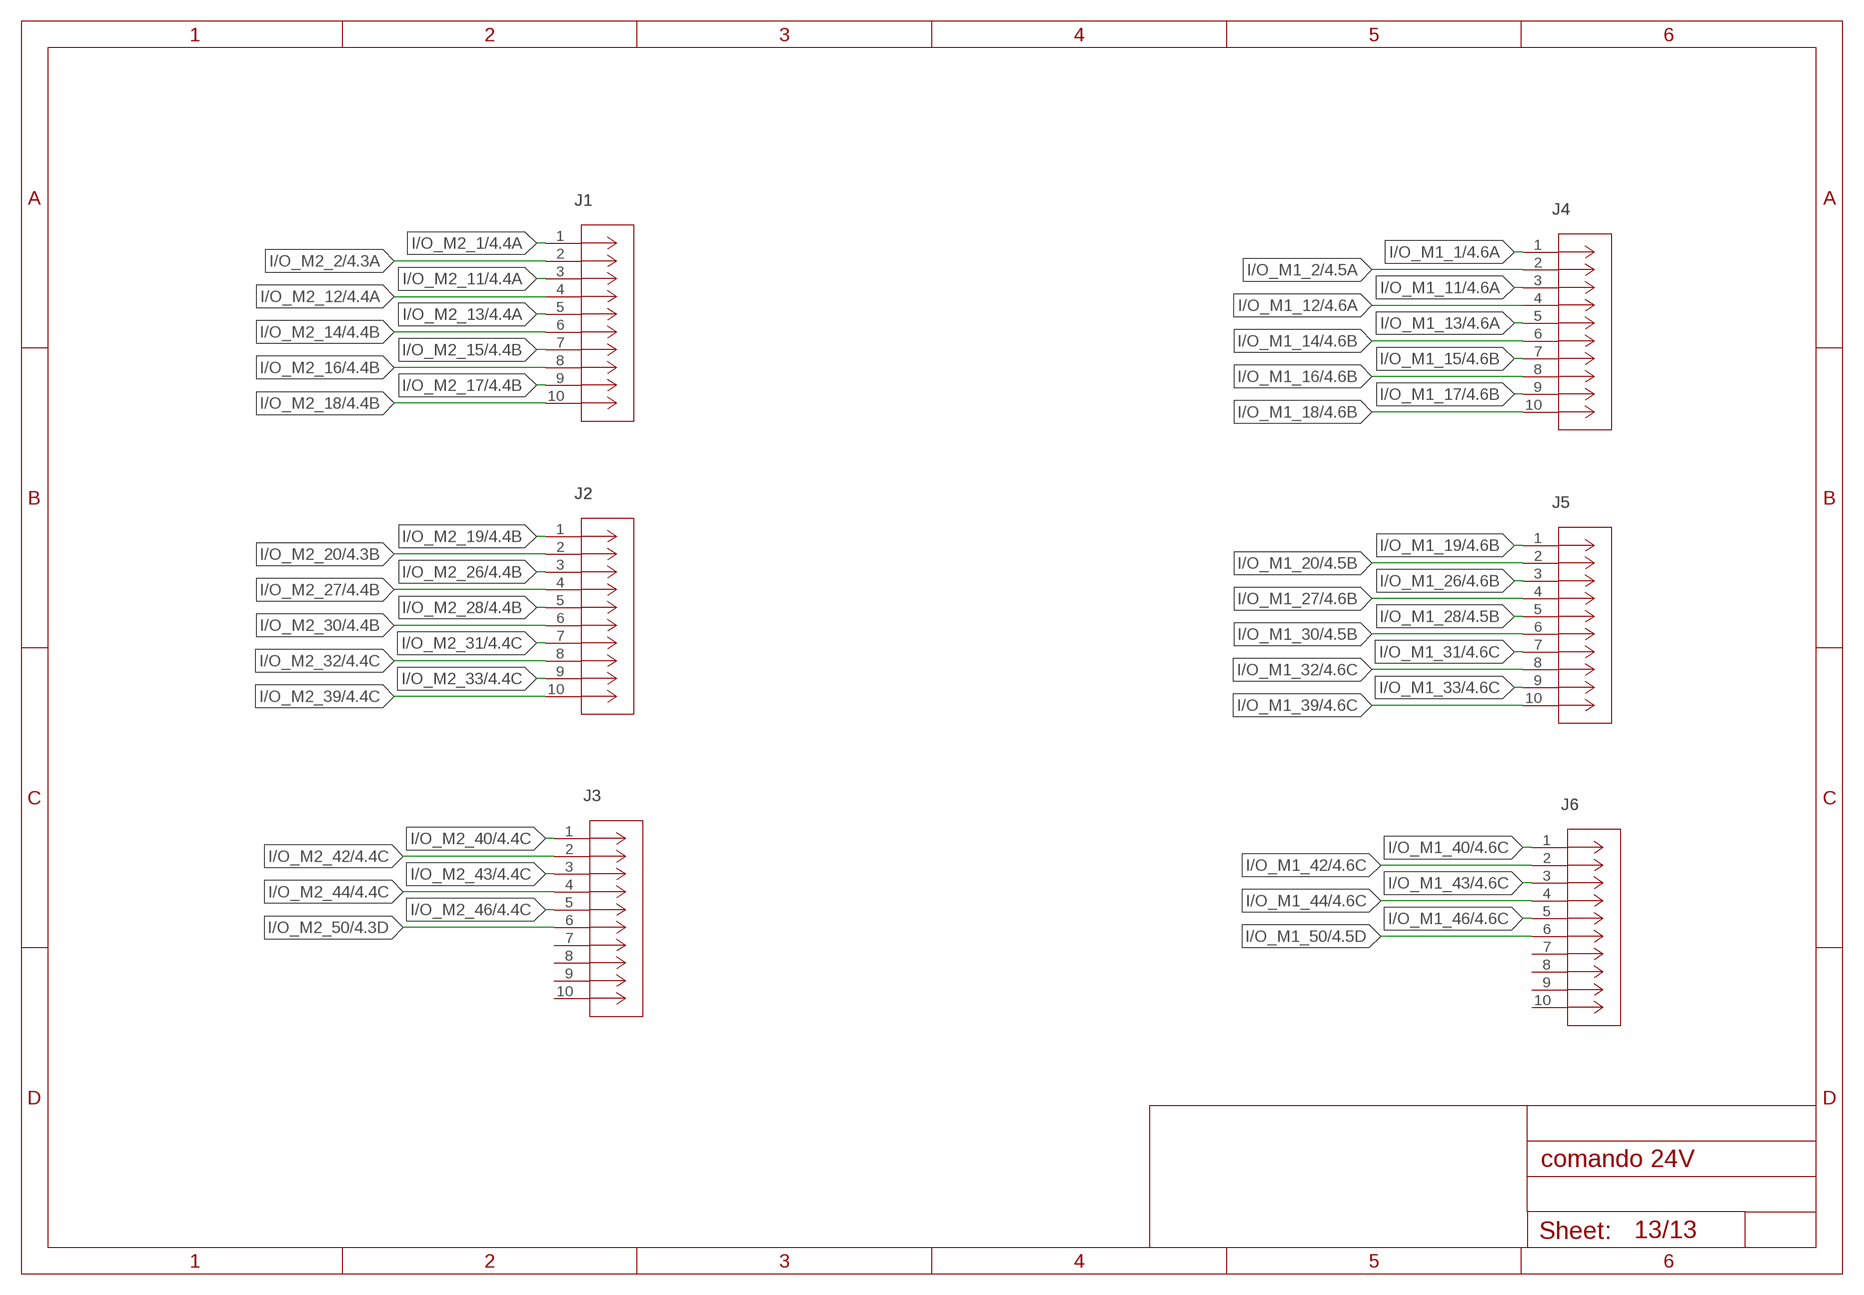
[diagram p12: schematic, sheet 13]

(export (version "E")
  (design (tool "Eeschema 10.0.6"))
  (components
    (comp (ref "J_ARD")
      (value "SBH11-PBPC-D25-ST-BK")
      (footprint "eagle-import:CONN_SBH11-PBPC-D25-ST-BK_SUL")
      (fields (field (name "COPYRIGHT") "Copyright (C) 2018 Accelerated Designs. All rights reserved"))
      (libsource (lib "eagle-import") (part "SBH11-PBPC-D25-ST-BK"))
    )
    (comp (ref "EN_IN_ENC")
      (value "STRIP_3")
      (footprint "eagle-import:STRIP_3")
      (libsource (lib "eagle-import") (part "STRIP_3"))
    )
    (comp (ref "IC1")
      (value "LM324N")
      (footprint "eagle-import:DIL14")
      (libsource (lib "eagle-import") (part "LM324N"))
    )
    (comp (ref "IC17")
      (value "LM324N")
      (footprint "eagle-import:DIL14")
      (libsource (lib "eagle-import") (part "LM324N"))
    )
    (comp (ref "R16")
      (value "22K")
      (footprint "eagle-import:0207_10")
      (libsource (lib "eagle-import") (part "R-EU_207/100207/10"))
    )
    (comp (ref "R17")
      (value "TEMP_ADJ")
      (footprint "eagle-import:RES3_64W_TTE")
      (fields
        (field (name "MANUFACTURER_PART_NUMBER") "64WR5KLF")
        (field (name "COPYRIGHT") "Copyright (C) 2016 Accelerated Designs. All rights reserved")
      )
      (libsource (lib "eagle-import") (part "64WR5KLF"))
    )
    (comp (ref "U4")
      (value "SN74LS244N")
      (footprint "eagle-import:N20")
      (fields
        (field (name "GENERIC_PART_NUMBER") "SN74LS244")
        (field (name "MANUFACTURER") "Texas Instruments")
      )
      (libsource (lib "eagle-import") (part "SN74LS244N"))
    )
    (comp (ref "U8")
      (value "H11L1M")
      (footprint "eagle-import:PDIP6-646BX_ONS")
      (fields (field (name "COPYRIGHT") "Copyright (C) 2018 Accelerated Designs. All rights reserved"))
      (libsource (lib "eagle-import") (part "H11L1M"))
    )
    (comp (ref "J1")
      (value "61201021621")
      (footprint "eagle-import:CONN_61201021621_WRE")
      (fields (field (name "COPYRIGHT") "Copyright (C) 2018 Accelerated Designs. All rights reserved"))
      (libsource (lib "eagle-import") (part "61201021621"))
    )
    (comp (ref "J2")
      (value "61201021621")
      (footprint "eagle-import:CONN_61201021621_WRE")
      (fields (field (name "COPYRIGHT") "Copyright (C) 2018 Accelerated Designs. All rights reserved"))
      (libsource (lib "eagle-import") (part "61201021621"))
    )
    (comp (ref "J3")
      (value "61201021621")
      (footprint "eagle-import:CONN_61201021621_WRE")
      (fields (field (name "COPYRIGHT") "Copyright (C) 2018 Accelerated Designs. All rights reserved"))
      (libsource (lib "eagle-import") (part "61201021621"))
    )
    (comp (ref "J4")
      (value "61201021621")
      (footprint "eagle-import:CONN_61201021621_WRE")
      (fields (field (name "COPYRIGHT") "Copyright (C) 2018 Accelerated Designs. All rights reserved"))
      (libsource (lib "eagle-import") (part "61201021621"))
    )
    (comp (ref "J5")
      (value "61201021621")
      (footprint "eagle-import:CONN_61201021621_WRE")
      (fields (field (name "COPYRIGHT") "Copyright (C) 2018 Accelerated Designs. All rights reserved"))
      (libsource (lib "eagle-import") (part "61201021621"))
    )
    (comp (ref "J6")
      (value "61201021621")
      (footprint "eagle-import:CONN_61201021621_WRE")
      (fields (field (name "COPYRIGHT") "Copyright (C) 2018 Accelerated Designs. All rights reserved"))
      (libsource (lib "eagle-import") (part "61201021621"))
    )
    (comp (ref "IC15")
      (value "LM324N")
      (footprint "eagle-import:DIL14")
      (libsource (lib "eagle-import") (part "LM324N"))
    )
    (comp (ref "IC16")
      (value "LM324N")
      (footprint "eagle-import:DIL14")
      (libsource (lib "eagle-import") (part "LM324N"))
    )
    (comp (ref "JI_TEXAS")
      (value "61202021621")
      (footprint "eagle-import:61202021621")
      (fields (field (name "DIGI-KEY_PART_NUMBER") "732-2096-ND") (field (name "MF") "Würth Elektronik"))
      (libsource (lib "eagle-import") (part "61202021621"))
    )
    (comp (ref "R27")
      (value "22K")
      (footprint "eagle-import:0207_10")
      (libsource (lib "eagle-import") (part "R-EU_207/100207/10"))
    )
    (comp (ref "R28")
      (value "VS_EDGE_ADJ")
      (footprint "eagle-import:RES3_64W_TTE")
      (fields
        (field (name "MANUFACTURER_PART_NUMBER") "64WR5KLF")
        (field (name "COPYRIGHT") "Copyright (C) 2016 Accelerated Designs. All rights reserved")
      )
      (libsource (lib "eagle-import") (part "64WR5KLF"))
    )
    (comp (ref "R1")
      (value "200R")
      (footprint "eagle-import:0207_10")
      (libsource (lib "eagle-import") (part "R-EU_207/100207/10"))
    )
    (comp (ref "R2")
      (value "200R")
      (footprint "eagle-import:0207_10")
      (libsource (lib "eagle-import") (part "R-EU_207/100207/10"))
    )
    (comp (ref "R3")
      (value "200R")
      (footprint "eagle-import:0207_10")
      (libsource (lib "eagle-import") (part "R-EU_207/100207/10"))
    )
    (comp (ref "R4")
      (value "200R")
      (footprint "eagle-import:0207_10")
      (libsource (lib "eagle-import") (part "R-EU_207/100207/10"))
    )
    (comp (ref "R6")
      (value "200R")
      (footprint "eagle-import:0207_10")
      (libsource (lib "eagle-import") (part "R-EU_207/100207/10"))
    )
    (comp (ref "R7")
      (value "200R")
      (footprint "eagle-import:0207_10")
      (libsource (lib "eagle-import") (part "R-EU_207/100207/10"))
    )
    (comp (ref "R8")
      (value "200R")
      (footprint "eagle-import:0207_10")
      (libsource (lib "eagle-import") (part "R-EU_207/100207/10"))
    )
    (comp (ref "R9")
      (value "200R")
      (footprint "eagle-import:0207_10")
      (libsource (lib "eagle-import") (part "R-EU_207/100207/10"))
    )
    (comp (ref "R10")
      (value "200R")
      (footprint "eagle-import:0207_10")
      (libsource (lib "eagle-import") (part "R-EU_207/100207/10"))
    )
    (comp (ref "R11")
      (value "200R")
      (footprint "eagle-import:0207_10")
      (libsource (lib "eagle-import") (part "R-EU_207/100207/10"))
    )
    (comp (ref "R12")
      (value "200R")
      (footprint "eagle-import:0207_10")
      (libsource (lib "eagle-import") (part "R-EU_207/100207/10"))
    )
    (comp (ref "R13")
      (value "200R")
      (footprint "eagle-import:0207_10")
      (libsource (lib "eagle-import") (part "R-EU_207/100207/10"))
    )
    (comp (ref "R20")
      (value "3K")
      (footprint "eagle-import:0207_10")
      (libsource (lib "eagle-import") (part "R-EU_207/100207/10"))
    )
    (comp (ref "R21")
      (value "3K")
      (footprint "eagle-import:0207_10")
      (libsource (lib "eagle-import") (part "R-EU_207/100207/10"))
    )
    (comp (ref "R22")
      (value "3K")
      (footprint "eagle-import:0207_10")
      (libsource (lib "eagle-import") (part "R-EU_207/100207/10"))
    )
    (comp (ref "R23")
      (value "3K")
      (footprint "eagle-import:0207_10")
      (libsource (lib "eagle-import") (part "R-EU_207/100207/10"))
    )
    (comp (ref "R24")
      (value "3K")
      (footprint "eagle-import:0207_10")
      (libsource (lib "eagle-import") (part "R-EU_207/100207/10"))
    )
    (comp (ref "U$1")
      (value "LED_TONDO")
      (footprint "eagle-import:LED_TONDO")
      (libsource (lib "eagle-import") (part "LED_TONDO"))
    )
    (comp (ref "U$2")
      (value "LED_TONDO")
      (footprint "eagle-import:LED_TONDO")
      (libsource (lib "eagle-import") (part "LED_TONDO"))
    )
    (comp (ref "U$3")
      (value "LED_TONDO")
      (footprint "eagle-import:LED_TONDO")
      (libsource (lib "eagle-import") (part "LED_TONDO"))
    )
    (comp (ref "U$4")
      (value "LED_TONDO")
      (footprint "eagle-import:LED_TONDO")
      (libsource (lib "eagle-import") (part "LED_TONDO"))
    )
    (comp (ref "U$5")
      (value "LED_TONDO")
      (footprint "eagle-import:LED_TONDO")
      (libsource (lib "eagle-import") (part "LED_TONDO"))
    )
    (comp (ref "U$6")
      (value "LED_TONDO")
      (footprint "eagle-import:LED_TONDO")
      (libsource (lib "eagle-import") (part "LED_TONDO"))
    )
    (comp (ref "U$7")
      (value "LED_TONDO")
      (footprint "eagle-import:LED_TONDO")
      (libsource (lib "eagle-import") (part "LED_TONDO"))
    )
    (comp (ref "U$8")
      (value "LED_TONDO")
      (footprint "eagle-import:LED_TONDO")
      (libsource (lib "eagle-import") (part "LED_TONDO"))
    )
    (comp (ref "U$9")
      (value "LED_TONDO")
      (footprint "eagle-import:LED_TONDO")
      (libsource (lib "eagle-import") (part "LED_TONDO"))
    )
    (comp (ref "U$10")
      (value "LED_TONDO")
      (footprint "eagle-import:LED_TONDO")
      (libsource (lib "eagle-import") (part "LED_TONDO"))
    )
    (comp (ref "U$11")
      (value "LED_TONDO")
      (footprint "eagle-import:LED_TONDO")
      (libsource (lib "eagle-import") (part "LED_TONDO"))
    )
    (comp (ref "U$12")
      (value "LED_TONDO")
      (footprint "eagle-import:LED_TONDO")
      (libsource (lib "eagle-import") (part "LED_TONDO"))
    )
    (comp (ref "U1")
      (value "ULN2003A")
      (footprint "eagle-import:DIP-16_STM")
      (libsource (lib "eagle-import") (part "ULN2003A"))
    )
    (comp (ref "U2")
      (value "ULN2003A")
      (footprint "eagle-import:DIP-16_STM")
      (libsource (lib "eagle-import") (part "ULN2003A"))
    )
    (comp (ref "EN_OUT_MOT")
      (value "STRIP_3")
      (footprint "eagle-import:STRIP_3")
      (libsource (lib "eagle-import") (part "STRIP_3"))
    )
    (comp (ref "IC5")
      (value "LM324N")
      (footprint "eagle-import:DIL14")
      (libsource (lib "eagle-import") (part "LM324N"))
    )
    (comp (ref "R18")
      (value "22K")
      (footprint "eagle-import:0207_10")
      (libsource (lib "eagle-import") (part "R-EU_207/100207/10"))
    )
    (comp (ref "R19")
      (value "VS_3V3_ADJ")
      (footprint "eagle-import:RES3_64W_TTE")
      (fields
        (field (name "MANUFACTURER_PART_NUMBER") "64WR5KLF")
        (field (name "COPYRIGHT") "Copyright (C) 2016 Accelerated Designs. All rights reserved")
      )
      (libsource (lib "eagle-import") (part "64WR5KLF"))
    )
    (comp (ref "U5")
      (value "SN74LS244N")
      (footprint "eagle-import:N20")
      (fields
        (field (name "GENERIC_PART_NUMBER") "SN74LS244")
        (field (name "MANUFACTURER") "Texas Instruments")
      )
      (libsource (lib "eagle-import") (part "SN74LS244N"))
    )
    (comp (ref "24V_SUP")
      (value "CON_2F")
      (footprint "eagle-import:CON_2F")
      (libsource (lib "eagle-import") (part "CON_2F"))
    )
    (comp (ref "AC_SUP")
      (value "B2B-XH-A(LF)(SN)")
      (footprint "eagle-import:CONN_B2B-XH-A(LF)(SN)_JST")
      (fields (field (name "COPYRIGHT") "Copyright (C) 2018 Accelerated Designs. All rights reserved"))
      (libsource (lib "eagle-import") (part "B2B-XH-A(LF)(SN)"))
    )
    (comp (ref "BRAKE")
      (value "CON_2F")
      (footprint "eagle-import:CON_2F")
      (libsource (lib "eagle-import") (part "CON_2F"))
    )
    (comp (ref "EL_VALV")
      (value "CON_2F")
      (footprint "eagle-import:CON_2F")
      (libsource (lib "eagle-import") (part "CON_2F"))
    )
    (comp (ref "EMRG_CHN")
      (value "CON_2F")
      (footprint "eagle-import:CON_2F")
      (libsource (lib "eagle-import") (part "CON_2F"))
    )
    (comp (ref "J7")
      (value "61201021621")
      (footprint "eagle-import:CONN_61201021621_WRE")
      (fields (field (name "COPYRIGHT") "Copyright (C) 2018 Accelerated Designs. All rights reserved"))
      (libsource (lib "eagle-import") (part "61201021621"))
    )
    (comp (ref "MOT1")
      (value "SBH11-PBPC-D25-ST-BK")
      (footprint "eagle-import:CONN_SBH11-PBPC-D25-ST-BK_SUL")
      (fields (field (name "COPYRIGHT") "Copyright (C) 2018 Accelerated Designs. All rights reserved"))
      (libsource (lib "eagle-import") (part "SBH11-PBPC-D25-ST-BK"))
    )
    (comp (ref "MOT2")
      (value "SBH11-PBPC-D25-ST-BK")
      (footprint "eagle-import:CONN_SBH11-PBPC-D25-ST-BK_SUL")
      (fields (field (name "COPYRIGHT") "Copyright (C) 2018 Accelerated Designs. All rights reserved"))
      (libsource (lib "eagle-import") (part "SBH11-PBPC-D25-ST-BK"))
    )
    (comp (ref "MOTZ")
      (value "61201021621")
      (footprint "eagle-import:CONN_61201021621_WRE")
      (fields (field (name "COPYRIGHT") "Copyright (C) 2018 Accelerated Designs. All rights reserved"))
      (libsource (lib "eagle-import") (part "61201021621"))
    )
    (comp (ref "PROXYM_M1")
      (value "CON_3F")
      (footprint "eagle-import:CON_3F")
      (libsource (lib "eagle-import") (part "CON_3F"))
    )
    (comp (ref "PROXYM_M2")
      (value "CON_3F")
      (footprint "eagle-import:CON_3F")
      (libsource (lib "eagle-import") (part "CON_3F"))
    )
    (comp (ref "J9")
      (value "SBH11-PBPC-D25-ST-BK")
      (footprint "eagle-import:CONN_SBH11-PBPC-D25-ST-BK_SUL")
      (fields (field (name "COPYRIGHT") "Copyright (C) 2018 Accelerated Designs. All rights reserved"))
      (libsource (lib "eagle-import") (part "SBH11-PBPC-D25-ST-BK"))
    )
    (comp (ref "J10")
      (value "SBH11-PBPC-D25-ST-BK")
      (footprint "eagle-import:CONN_SBH11-PBPC-D25-ST-BK_SUL")
      (fields (field (name "COPYRIGHT") "Copyright (C) 2018 Accelerated Designs. All rights reserved"))
      (libsource (lib "eagle-import") (part "SBH11-PBPC-D25-ST-BK"))
    )
    (comp (ref "EN_M1_ENC_PHZ")
      (value "STRIP_2")
      (footprint "eagle-import:STRIP_2")
      (libsource (lib "eagle-import") (part "STRIP_2"))
    )
    (comp (ref "EN_M2_ENC_PHZ")
      (value "STRIP_2")
      (footprint "eagle-import:STRIP_2")
      (libsource (lib "eagle-import") (part "STRIP_2"))
    )
    (comp (ref "J1/J3")
      (value "61202021621")
      (footprint "eagle-import:61202021621")
      (fields (field (name "DIGI-KEY_PART_NUMBER") "732-2096-ND") (field (name "MF") "Würth Elektronik"))
      (libsource (lib "eagle-import") (part "61202021621"))
    )
    (comp (ref "J4/J2")
      (value "61202021621")
      (footprint "eagle-import:61202021621")
      (fields (field (name "DIGI-KEY_PART_NUMBER") "732-2096-ND") (field (name "MF") "Würth Elektronik"))
      (libsource (lib "eagle-import") (part "61202021621"))
    )
    (comp (ref "J5/J7")
      (value "61202021621")
      (footprint "eagle-import:61202021621")
      (fields (field (name "DIGI-KEY_PART_NUMBER") "732-2096-ND") (field (name "MF") "Würth Elektronik"))
      (libsource (lib "eagle-import") (part "61202021621"))
    )
    (comp (ref "J8/J6")
      (value "61202021621")
      (footprint "eagle-import:61202021621")
      (fields (field (name "DIGI-KEY_PART_NUMBER") "732-2096-ND") (field (name "MF") "Würth Elektronik"))
      (libsource (lib "eagle-import") (part "61202021621"))
    )
    (comp (ref "C2")
      (value "QYX1H102JTP3TA")
      (footprint "eagle-import:CAP_QYX_2P5X5X8P5_NCH")
      (fields (field (name "COPYRIGHT") "Copyright (C) 2018 Accelerated Designs. All rights reserved"))
      (libsource (lib "eagle-import") (part "QYX1H102JTP3TA"))
    )
    (comp (ref "C3")
      (value "UBY2A301MHL")
      (footprint "eagle-import:CAP_UBY_12P5X31P5_NCH")
      (fields (field (name "COPYRIGHT") "Copyright (C) 2018 Accelerated Designs. All rights reserved"))
      (libsource (lib "eagle-import") (part "UBY2A301MHL"))
    )
    (comp (ref "PT1")
      (value "POT_2W_5K")
      (footprint "eagle-import:POT_2W_5K")
      (libsource (lib "eagle-import") (part "POT_2W_5K"))
    )
    (comp (ref "R5")
      (value "OY104KE")
      (footprint "eagle-import:RES_OY_OHM")
      (libsource (lib "eagle-import") (part "OY104KE"))
    )
    (comp (ref "R29")
      (value "2K")
      (footprint "eagle-import:0207_10")
      (libsource (lib "eagle-import") (part "R-EU_207/100207/10"))
    )
    (comp (ref "SUP_3V3")
      (value "BR30X")
      (footprint "eagle-import:BR30X")
      (libsource (lib "eagle-import") (part "BR30X"))
    )
    (comp (ref "SUP_5V")
      (value "BR30X")
      (footprint "eagle-import:BR30X")
      (libsource (lib "eagle-import") (part "BR30X"))
    )
    (comp (ref "U$13")
      (value "C0U12F")
      (footprint "eagle-import:C0U12F")
      (libsource (lib "eagle-import") (part "C0U12F"))
    )
    (comp (ref "U$14")
      (value "MB6M-E3/45")
      (footprint "eagle-import:DIP508W58P254L483H270Q4")
      (libsource (lib "eagle-import") (part "MB6M-E3/45"))
    )
    (comp (ref "U$15")
      (value "LED_ON")
      (footprint "eagle-import:LED_TONDO")
      (libsource (lib "eagle-import") (part "LED_TONDO"))
    )
    (comp (ref "U3")
      (value "TMP37FT9Z")
      (footprint "eagle-import:T_3_ADI")
      (libsource (lib "eagle-import") (part "TMP37FT9Z"))
    )
    (comp (ref "EN_SCI")
      (value "STRIP_3")
      (footprint "eagle-import:STRIP_3")
      (libsource (lib "eagle-import") (part "STRIP_3"))
    )
    (comp (ref "IC7")
      (value "LM324N")
      (footprint "eagle-import:DIL14")
      (libsource (lib "eagle-import") (part "LM324N"))
    )
    (comp (ref "IC11")
      (value "LM324N")
      (footprint "eagle-import:DIL14")
      (libsource (lib "eagle-import") (part "LM324N"))
    )
    (comp (ref "J8")
      (value "61202021621")
      (footprint "eagle-import:61202021621")
      (fields (field (name "DIGI-KEY_PART_NUMBER") "732-2096-ND") (field (name "MF") "Würth Elektronik"))
      (libsource (lib "eagle-import") (part "61202021621"))
    )
    (comp (ref "J_LAMPADE")
      (value "61201021621")
      (footprint "eagle-import:CONN_61201021621_WRE")
      (fields (field (name "COPYRIGHT") "Copyright (C) 2018 Accelerated Designs. All rights reserved"))
      (libsource (lib "eagle-import") (part "61201021621"))
    )
    (comp (ref "OUT_ARD_4-7_5V-24V")
      (value "STRIP_3")
      (footprint "eagle-import:STRIP_3")
      (libsource (lib "eagle-import") (part "STRIP_3"))
    )
    (comp (ref "OUT_ARD_8-11_5V-24V")
      (value "STRIP_3")
      (footprint "eagle-import:STRIP_3")
      (libsource (lib "eagle-import") (part "STRIP_3"))
    )
    (comp (ref "R14")
      (value "22K")
      (footprint "eagle-import:0207_10")
      (libsource (lib "eagle-import") (part "R-EU_207/100207/10"))
    )
    (comp (ref "R15")
      (value "VS_5v_ADJ")
      (footprint "eagle-import:RES3_64W_TTE")
      (fields
        (field (name "MANUFACTURER_PART_NUMBER") "64WR5KLF")
        (field (name "COPYRIGHT") "Copyright (C) 2016 Accelerated Designs. All rights reserved")
      )
      (libsource (lib "eagle-import") (part "64WR5KLF"))
    )
    (comp (ref "U6")
      (value "SN74LS244N")
      (footprint "eagle-import:N20")
      (fields
        (field (name "GENERIC_PART_NUMBER") "SN74LS244")
        (field (name "MANUFACTURER") "Texas Instruments")
      )
      (libsource (lib "eagle-import") (part "SN74LS244N"))
    )
    (comp (ref "EN_GPO_H")
      (value "STRIP_3")
      (footprint "eagle-import:STRIP_3")
      (libsource (lib "eagle-import") (part "STRIP_3"))
    )
    (comp (ref "J_GPO/I2C_H1")
      (value "61202021621")
      (footprint "eagle-import:61202021621")
      (fields (field (name "DIGI-KEY_PART_NUMBER") "732-2096-ND") (field (name "MF") "Würth Elektronik"))
      (libsource (lib "eagle-import") (part "61202021621"))
    )
    (comp (ref "U7")
      (value "SN74LS244N")
      (footprint "eagle-import:N20")
      (fields
        (field (name "GENERIC_PART_NUMBER") "SN74LS244")
        (field (name "MANUFACTURER") "Texas Instruments")
      )
      (libsource (lib "eagle-import") (part "SN74LS244N"))
    )
    (comp (ref "IC12")
      (value "LM324N")
      (footprint "eagle-import:DIL14")
      (libsource (lib "eagle-import") (part "LM324N"))
    )
    (comp (ref "IC13")
      (value "LM324N")
      (footprint "eagle-import:DIL14")
      (libsource (lib "eagle-import") (part "LM324N"))
    )
    (comp (ref "IC14")
      (value "LM324N")
      (footprint "eagle-import:DIL14")
      (libsource (lib "eagle-import") (part "LM324N"))
    )
    (comp (ref "JI_ARD")
      (value "61202021621")
      (footprint "eagle-import:61202021621")
      (fields (field (name "DIGI-KEY_PART_NUMBER") "732-2096-ND") (field (name "MF") "Würth Elektronik"))
      (libsource (lib "eagle-import") (part "61202021621"))
    )
    (comp (ref "R25")
      (value "22K")
      (footprint "eagle-import:0207_10")
      (libsource (lib "eagle-import") (part "R-EU_207/100207/10"))
    )
    (comp (ref "R26")
      (value "VS_ARD_ADJ")
      (footprint "eagle-import:RES3_64W_TTE")
      (fields
        (field (name "MANUFACTURER_PART_NUMBER") "64WR5KLF")
        (field (name "COPYRIGHT") "Copyright (C) 2016 Accelerated Designs. All rights reserved")
      )
      (libsource (lib "eagle-import") (part "64WR5KLF"))
    )
  )
  (nets
    (net (code "1") (name "+3V3") (class "Default")
      (node (ref "EMRG_CHN") (pin "2") (pinfunction "2_2") (pintype "bidirectional"))
      (node (ref "IC1") (pin "2") (pinfunction "-IN_2") (pintype "input"))
      (node (ref "IC1") (pin "6") (pinfunction "-IN_6") (pintype "input"))
      (node (ref "IC17") (pin "13") (pinfunction "-IN_13") (pintype "input"))
      (node (ref "SUP_3V3") (pin "VOUT") (pinfunction "VOUT_VOUT") (pintype "output"))
      (node (ref "U8") (pin "6") (pinfunction "VCC_6") (pintype "power_in"))
    )
    (net (code "2") (name "+5V") (class "Default")
      (node (ref "EN_GPO_H") (pin "1") (pinfunction "1_1") (pintype "passive"))
      (node (ref "EN_IN_ENC") (pin "1") (pinfunction "1_1") (pintype "passive"))
      (node (ref "EN_OUT_MOT") (pin "1") (pinfunction "1_1") (pintype "passive"))
      (node (ref "EN_SCI") (pin "1") (pinfunction "1_1") (pintype "passive"))
      (node (ref "IC1") (pin "4") (pinfunction "V+_4") (pintype "power_in"))
      (node (ref "IC12") (pin "4") (pinfunction "V+_4") (pintype "power_in"))
      (node (ref "IC13") (pin "4") (pinfunction "V+_4") (pintype "power_in"))
      (node (ref "IC14") (pin "4") (pinfunction "V+_4") (pintype "power_in"))
      (node (ref "IC15") (pin "4") (pinfunction "V+_4") (pintype "power_in"))
      (node (ref "IC16") (pin "4") (pinfunction "V+_4") (pintype "power_in"))
      (node (ref "IC17") (pin "4") (pinfunction "V+_4") (pintype "power_in"))
      (node (ref "J_ARD") (pin "3") (pinfunction "3_3") (pintype "passive"))
      (node (ref "OUT_ARD_4-7_5V-24V") (pin "1") (pinfunction "1_1") (pintype "passive"))
      (node (ref "OUT_ARD_8-11_5V-24V") (pin "1") (pinfunction "1_1") (pintype "passive"))
      (node (ref "R1") (pin "2") (pinfunction "2_2") (pintype "passive"))
      (node (ref "R10") (pin "2") (pinfunction "2_2") (pintype "passive"))
      (node (ref "R11") (pin "2") (pinfunction "2_2") (pintype "passive"))
      (node (ref "R12") (pin "2") (pinfunction "2_2") (pintype "passive"))
      (node (ref "R13") (pin "2") (pinfunction "2_2") (pintype "passive"))
      (node (ref "R2") (pin "2") (pinfunction "2_2") (pintype "passive"))
      (node (ref "R3") (pin "2") (pinfunction "2_2") (pintype "passive"))
      (node (ref "R4") (pin "2") (pinfunction "2_2") (pintype "passive"))
      (node (ref "R6") (pin "2") (pinfunction "2_2") (pintype "passive"))
      (node (ref "R7") (pin "2") (pinfunction "2_2") (pintype "passive"))
      (node (ref "R8") (pin "2") (pinfunction "2_2") (pintype "passive"))
      (node (ref "R9") (pin "2") (pinfunction "2_2") (pintype "passive"))
      (node (ref "SUP_5V") (pin "VOUT") (pinfunction "VOUT_VOUT") (pintype "output"))
      (node (ref "U3") (pin "1") (pinfunction "+VS_1") (pintype "power_in"))
      (node (ref "U4") (pin "20") (pinfunction "VCC_20") (pintype "power_in"))
      (node (ref "U5") (pin "20") (pinfunction "VCC_20") (pintype "power_in"))
      (node (ref "U6") (pin "20") (pinfunction "VCC_20") (pintype "power_in"))
      (node (ref "U7") (pin "20") (pinfunction "VCC_20") (pintype "power_in"))
    )
    (net (code "3") (name "+24V") (class "Default")
      (node (ref "24V_SUP") (pin "1") (pinfunction "1_1") (pintype "bidirectional"))
      (node (ref "C2") (pin "1") (pinfunction "1_1") (pintype "passive"))
      (node (ref "C3") (pin "1") (pinfunction "1_1") (pintype "passive"))
      (node (ref "EL_VALV") (pin "2") (pinfunction "2_2") (pintype "bidirectional"))
      (node (ref "IC5") (pin "4") (pinfunction "V+_4") (pintype "power_in"))
      (node (ref "MOT1") (pin "7") (pinfunction "7_7") (pintype "passive"))
      (node (ref "MOT2") (pin "7") (pinfunction "7_7") (pintype "passive"))
      (node (ref "MOTZ") (pin "1") (pinfunction "1_1") (pintype "passive"))
      (node (ref "OUT_ARD_4-7_5V-24V") (pin "3") (pinfunction "3_3") (pintype "passive"))
      (node (ref "OUT_ARD_8-11_5V-24V") (pin "3") (pinfunction "3_3") (pintype "passive"))
      (node (ref "PROXYM_M1") (pin "3") (pinfunction "3_3") (pintype "bidirectional"))
      (node (ref "PROXYM_M2") (pin "3") (pinfunction "3_3") (pintype "bidirectional"))
      (node (ref "R14") (pin "2") (pinfunction "2_2") (pintype "passive"))
      (node (ref "R16") (pin "2") (pinfunction "2_2") (pintype "passive"))
      (node (ref "R18") (pin "2") (pinfunction "2_2") (pintype "passive"))
      (node (ref "R20") (pin "2") (pinfunction "2_2") (pintype "passive"))
      (node (ref "R21") (pin "2") (pinfunction "2_2") (pintype "passive"))
      (node (ref "R22") (pin "2") (pinfunction "2_2") (pintype "passive"))
      (node (ref "R23") (pin "2") (pinfunction "2_2") (pintype "passive"))
      (node (ref "R24") (pin "2") (pinfunction "2_2") (pintype "passive"))
      (node (ref "R25") (pin "2") (pinfunction "2_2") (pintype "passive"))
      (node (ref "R27") (pin "2") (pinfunction "2_2") (pintype "passive"))
      (node (ref "R29") (pin "2") (pinfunction "2_2") (pintype "passive"))
      (node (ref "SUP_3V3") (pin "VIN") (pinfunction "VIN_VIN") (pintype "power_in"))
      (node (ref "SUP_5V") (pin "VIN") (pinfunction "VIN_VIN") (pintype "power_in"))
      (node (ref "U1") (pin "9") (pinfunction "COMMON_9") (pintype "passive"))
      (node (ref "U2") (pin "9") (pinfunction "COMMON_9") (pintype "passive"))
    )
    (net (code "4") (name "220V_PROBE") (class "Default")
      (node (ref "PT1") (pin "2") (pinfunction "2_2") (pintype "passive"))
      (node (ref "U8") (pin "1") (pinfunction "ANODE_1") (pintype "passive"))
    )
    (net (code "5") (name "AC_IN1") (class "Default")
      (node (ref "AC_SUP") (pin "1") (pinfunction "1_1") (pintype "passive"))
      (node (ref "U$14") (pin "3") (pinfunction "AC1_3") (pintype "passive"))
    )
    (net (code "6") (name "AC_IN2") (class "Default")
      (node (ref "AC_SUP") (pin "2") (pinfunction "2_2") (pintype "passive"))
      (node (ref "U$14") (pin "4") (pinfunction "AC2_4") (pintype "passive"))
    )
    (net (code "7") (name "GND") (class "Default")
      (node (ref "24V_SUP") (pin "2") (pinfunction "2_2") (pintype "bidirectional"))
      (node (ref "BRAKE") (pin "2") (pinfunction "2_2") (pintype "bidirectional"))
      (node (ref "C2") (pin "2") (pinfunction "2_2") (pintype "passive"))
      (node (ref "C3") (pin "2") (pinfunction "2_2") (pintype "passive"))
      (node (ref "EN_GPO_H") (pin "3") (pinfunction "3_3") (pintype "passive"))
      (node (ref "EN_IN_ENC") (pin "3") (pinfunction "3_3") (pintype "passive"))
      (node (ref "EN_OUT_MOT") (pin "3") (pinfunction "3_3") (pintype "passive"))
      (node (ref "EN_SCI") (pin "3") (pinfunction "3_3") (pintype "passive"))
      (node (ref "IC1") (pin "11") (pinfunction "V-_11") (pintype "power_in"))
      (node (ref "IC11") (pin "11") (pinfunction "V-_11") (pintype "power_in"))
      (node (ref "IC12") (pin "11") (pinfunction "V-_11") (pintype "power_in"))
      (node (ref "IC13") (pin "11") (pinfunction "V-_11") (pintype "power_in"))
      (node (ref "IC14") (pin "11") (pinfunction "V-_11") (pintype "power_in"))
      (node (ref "IC15") (pin "11") (pinfunction "V-_11") (pintype "power_in"))
      (node (ref "IC16") (pin "11") (pinfunction "V-_11") (pintype "power_in"))
      (node (ref "IC17") (pin "11") (pinfunction "V-_11") (pintype "power_in"))
      (node (ref "IC5") (pin "11") (pinfunction "V-_11") (pintype "power_in"))
      (node (ref "IC7") (pin "11") (pinfunction "V-_11") (pintype "power_in"))
      (node (ref "J1/J3") (pin "12") (pinfunction "4_12") (pintype "passive"))
      (node (ref "J10") (pin "14") (pinfunction "14_14") (pintype "passive"))
      (node (ref "J10") (pin "2") (pinfunction "2_2") (pintype "passive"))
      (node (ref "J10") (pin "23") (pinfunction "23_23") (pintype "passive"))
      (node (ref "J10") (pin "32") (pinfunction "32_32") (pintype "passive"))
      (node (ref "J10") (pin "4") (pinfunction "4_4") (pintype "passive"))
      (node (ref "J4/J2") (pin "11") (pinfunction "2_11") (pintype "passive"))
      (node (ref "J5/J7") (pin "12") (pinfunction "4_12") (pintype "passive"))
      (node (ref "J7") (pin "2") (pinfunction "2_2") (pintype "passive"))
      (node (ref "J7") (pin "4") (pinfunction "4_4") (pintype "passive"))
      (node (ref "J8") (pin "1") (pinfunction "1_1") (pintype "passive"))
      (node (ref "J8") (pin "10") (pinfunction "19_10") (pintype "passive"))
      (node (ref "J8") (pin "2") (pinfunction "3_2") (pintype "passive"))
      (node (ref "J8") (pin "3") (pinfunction "5_3") (pintype "passive"))
      (node (ref "J8") (pin "4") (pinfunction "7_4") (pintype "passive"))
      (node (ref "J8") (pin "5") (pinfunction "9_5") (pintype "passive"))
      (node (ref "J8") (pin "6") (pinfunction "11_6") (pintype "passive"))
      (node (ref "J8") (pin "7") (pinfunction "13_7") (pintype "passive"))
      (node (ref "J8") (pin "8") (pinfunction "15_8") (pintype "passive"))
      (node (ref "J8") (pin "9") (pinfunction "17_9") (pintype "passive"))
      (node (ref "J8/J6") (pin "11") (pinfunction "2_11") (pintype "passive"))
      (node (ref "J9") (pin "16") (pinfunction "16_16") (pintype "passive"))
      (node (ref "J9") (pin "2") (pinfunction "2_2") (pintype "passive"))
      (node (ref "J9") (pin "25") (pinfunction "25_25") (pintype "passive"))
      (node (ref "J9") (pin "34") (pinfunction "34_34") (pintype "passive"))
      (node (ref "J9") (pin "4") (pinfunction "4_4") (pintype "passive"))
      (node (ref "JI_ARD") (pin "1") (pinfunction "1_1") (pintype "passive"))
      (node (ref "JI_ARD") (pin "10") (pinfunction "19_10") (pintype "passive"))
      (node (ref "JI_ARD") (pin "2") (pinfunction "3_2") (pintype "passive"))
      (node (ref "JI_ARD") (pin "3") (pinfunction "5_3") (pintype "passive"))
      (node (ref "JI_ARD") (pin "4") (pinfunction "7_4") (pintype "passive"))
      (node (ref "JI_ARD") (pin "5") (pinfunction "9_5") (pintype "passive"))
      (node (ref "JI_ARD") (pin "6") (pinfunction "11_6") (pintype "passive"))
      (node (ref "JI_ARD") (pin "7") (pinfunction "13_7") (pintype "passive"))
      (node (ref "JI_ARD") (pin "8") (pinfunction "15_8") (pintype "passive"))
      (node (ref "JI_ARD") (pin "9") (pinfunction "17_9") (pintype "passive"))
      (node (ref "JI_TEXAS") (pin "1") (pinfunction "1_1") (pintype "passive"))
      (node (ref "JI_TEXAS") (pin "10") (pinfunction "19_10") (pintype "passive"))
      (node (ref "JI_TEXAS") (pin "2") (pinfunction "3_2") (pintype "passive"))
      (node (ref "JI_TEXAS") (pin "3") (pinfunction "5_3") (pintype "passive"))
      (node (ref "JI_TEXAS") (pin "4") (pinfunction "7_4") (pintype "passive"))
      (node (ref "JI_TEXAS") (pin "5") (pinfunction "9_5") (pintype "passive"))
      (node (ref "JI_TEXAS") (pin "6") (pinfunction "11_6") (pintype "passive"))
      (node (ref "JI_TEXAS") (pin "7") (pinfunction "13_7") (pintype "passive"))
      (node (ref "JI_TEXAS") (pin "8") (pinfunction "15_8") (pintype "passive"))
      (node (ref "JI_TEXAS") (pin "9") (pinfunction "17_9") (pintype "passive"))
      (node (ref "J_ARD") (pin "1") (pinfunction "1_1") (pintype "passive"))
      (node (ref "J_ARD") (pin "2") (pinfunction "2_2") (pintype "passive"))
      (node (ref "J_GPO/I2C_H1") (pin "1") (pinfunction "1_1") (pintype "passive"))
      (node (ref "J_GPO/I2C_H1") (pin "10") (pinfunction "19_10") (pintype "passive"))
      (node (ref "J_GPO/I2C_H1") (pin "2") (pinfunction "3_2") (pintype "passive"))
      (node (ref "J_GPO/I2C_H1") (pin "3") (pinfunction "5_3") (pintype "passive"))
      (node (ref "J_GPO/I2C_H1") (pin "4") (pinfunction "7_4") (pintype "passive"))
      (node (ref "J_GPO/I2C_H1") (pin "5") (pinfunction "9_5") (pintype "passive"))
      (node (ref "J_GPO/I2C_H1") (pin "6") (pinfunction "11_6") (pintype "passive"))
      (node (ref "J_GPO/I2C_H1") (pin "7") (pinfunction "13_7") (pintype "passive"))
      (node (ref "J_GPO/I2C_H1") (pin "8") (pinfunction "15_8") (pintype "passive"))
      (node (ref "J_GPO/I2C_H1") (pin "9") (pinfunction "17_9") (pintype "passive"))
      (node (ref "J_LAMPADE") (pin "10") (pinfunction "10_10") (pintype "passive"))
      (node (ref "J_LAMPADE") (pin "2") (pinfunction "2_2") (pintype "passive"))
      (node (ref "J_LAMPADE") (pin "4") (pinfunction "4_4") (pintype "passive"))
      (node (ref "J_LAMPADE") (pin "6") (pinfunction "6_6") (pintype "passive"))
      (node (ref "J_LAMPADE") (pin "8") (pinfunction "8_8") (pintype "passive"))
      (node (ref "MOT1") (pin "10") (pinfunction "10_10") (pintype "passive"))
      (node (ref "MOT1") (pin "22") (pinfunction "22_22") (pintype "passive"))
      (node (ref "MOT1") (pin "24") (pinfunction "24_24") (pintype "passive"))
      (node (ref "MOT1") (pin "25") (pinfunction "25_25") (pintype "passive"))
      (node (ref "MOT1") (pin "34") (pinfunction "34_34") (pintype "passive"))
      (node (ref "MOT1") (pin "36") (pinfunction "36_36") (pintype "passive"))
      (node (ref "MOT1") (pin "38") (pinfunction "38_38") (pintype "passive"))
      (node (ref "MOT1") (pin "4") (pinfunction "4_4") (pintype "passive"))
      (node (ref "MOT1") (pin "41") (pinfunction "41_41") (pintype "passive"))
      (node (ref "MOT1") (pin "45") (pinfunction "45_45") (pintype "passive"))
      (node (ref "MOT1") (pin "47") (pinfunction "47_47") (pintype "passive"))
      (node (ref "MOT1") (pin "48") (pinfunction "48_48") (pintype "passive"))
      (node (ref "MOT1") (pin "6") (pinfunction "6_6") (pintype "passive"))
      (node (ref "MOT2") (pin "10") (pinfunction "10_10") (pintype "passive"))
      (node (ref "MOT2") (pin "22") (pinfunction "22_22") (pintype "passive"))
      (node (ref "MOT2") (pin "24") (pinfunction "24_24") (pintype "passive"))
      (node (ref "MOT2") (pin "25") (pinfunction "25_25") (pintype "passive"))
      (node (ref "MOT2") (pin "34") (pinfunction "34_34") (pintype "passive"))
      (node (ref "MOT2") (pin "36") (pinfunction "36_36") (pintype "passive"))
      (node (ref "MOT2") (pin "38") (pinfunction "38_38") (pintype "passive"))
      (node (ref "MOT2") (pin "4") (pinfunction "4_4") (pintype "passive"))
      (node (ref "MOT2") (pin "41") (pinfunction "41_41") (pintype "passive"))
      (node (ref "MOT2") (pin "45") (pinfunction "45_45") (pintype "passive"))
      (node (ref "MOT2") (pin "47") (pinfunction "47_47") (pintype "passive"))
      (node (ref "MOT2") (pin "48") (pinfunction "48_48") (pintype "passive"))
      (node (ref "MOT2") (pin "6") (pinfunction "6_6") (pintype "passive"))
      (node (ref "MOTZ") (pin "2") (pinfunction "2_2") (pintype "passive"))
      (node (ref "PROXYM_M1") (pin "2") (pinfunction "2_2") (pintype "bidirectional"))
      (node (ref "PROXYM_M2") (pin "2") (pinfunction "2_2") (pintype "bidirectional"))
      (node (ref "R15") (pin "3") (pinfunction "3_3") (pintype "passive"))
      (node (ref "R17") (pin "3") (pinfunction "3_3") (pintype "passive"))
      (node (ref "R19") (pin "3") (pinfunction "3_3") (pintype "passive"))
      (node (ref "R26") (pin "3") (pinfunction "3_3") (pintype "passive"))
      (node (ref "R28") (pin "3") (pinfunction "3_3") (pintype "passive"))
      (node (ref "SUP_3V3") (pin "GND") (pinfunction "GND_GND") (pintype "power_in"))
      (node (ref "SUP_5V") (pin "GND") (pinfunction "GND_GND") (pintype "power_in"))
      (node (ref "U$15") (pin "1") (pinfunction "1_1") (pintype "passive"))
      (node (ref "U1") (pin "8") (pinfunction "GND_8") (pintype "passive"))
      (node (ref "U2") (pin "8") (pinfunction "GND_8") (pintype "passive"))
      (node (ref "U3") (pin "3") (pinfunction "GND_3") (pintype "passive"))
      (node (ref "U4") (pin "10") (pinfunction "GND_10") (pintype "power_in"))
      (node (ref "U5") (pin "10") (pinfunction "GND_10") (pintype "power_in"))
      (node (ref "U6") (pin "10") (pinfunction "GND_10") (pintype "power_in"))
      (node (ref "U7") (pin "10") (pinfunction "GND_10") (pintype "power_in"))
      (node (ref "U8") (pin "5") (pinfunction "GND_5") (pintype "passive"))
    )
    (net (code "8") (name "GND_220V") (class "Default")
      (node (ref "PT1") (pin "1") (pinfunction "1_1") (pintype "passive"))
      (node (ref "U$13") (pin "P$2") (pinfunction "2_P$2") (pintype "passive"))
      (node (ref "U$14") (pin "2") (pinfunction "-_2") (pintype "passive"))
      (node (ref "U8") (pin "2") (pinfunction "CATHODE_2") (pintype "passive"))
    )
    (net (code "9") (name "IN_3V3_220V_ALARM") (class "Default")
      (node (ref "J9") (pin "15") (pinfunction "15_15") (pintype "passive"))
      (node (ref "U8") (pin "4") (pinfunction "VO_4") (pintype "passive"))
    )
    (net (code "10") (name "IN_3V3_EDGE1") (class "Default")
      (node (ref "IC15") (pin "14") (pinfunction "OUT_14") (pintype "output"))
      (node (ref "J4/J2") (pin "3") (pinfunction "5_3") (pintype "passive"))
    )
    (net (code "11") (name "IN_3V3_EDGE2") (class "Default")
      (node (ref "IC15") (pin "8") (pinfunction "OUT_8") (pintype "output"))
      (node (ref "J4/J2") (pin "6") (pinfunction "11_6") (pintype "passive"))
    )
    (net (code "12") (name "IN_3V3_EDGE3") (class "Default")
      (node (ref "IC15") (pin "7") (pinfunction "OUT_7") (pintype "output"))
      (node (ref "J4/J2") (pin "5") (pinfunction "9_5") (pintype "passive"))
    )
    (net (code "13") (name "IN_3V3_EDGE4") (class "Default")
      (node (ref "IC17") (pin "1") (pinfunction "OUT_1") (pintype "output"))
      (node (ref "J9") (pin "22") (pinfunction "22_22") (pintype "passive"))
    )
    (net (code "14") (name "IN_3V3_EDGE5") (class "Default")
      (node (ref "IC17") (pin "7") (pinfunction "OUT_7") (pintype "output"))
      (node (ref "J9") (pin "24") (pinfunction "24_24") (pintype "passive"))
    )
    (net (code "15") (name "IN_3V3_EDGE6") (class "Default")
      (node (ref "IC17") (pin "8") (pinfunction "OUT_8") (pintype "output"))
      (node (ref "J9") (pin "23") (pinfunction "23_23") (pintype "passive"))
    )
    (net (code "16") (name "IN_3V3_EDGE7") (class "Default")
      (node (ref "IC16") (pin "1") (pinfunction "OUT_1") (pintype "output"))
      (node (ref "J9") (pin "26") (pinfunction "26_26") (pintype "passive"))
    )
    (net (code "17") (name "IN_3V3_EDGE8") (class "Default")
      (node (ref "IC16") (pin "7") (pinfunction "OUT_7") (pintype "output"))
      (node (ref "J9") (pin "27") (pinfunction "27_27") (pintype "passive"))
    )
    (net (code "18") (name "IN_3V3_EDGE9") (class "Default")
      (node (ref "IC16") (pin "14") (pinfunction "OUT_14") (pintype "output"))
      (node (ref "J9") (pin "28") (pinfunction "28_28") (pintype "passive"))
    )
    (net (code "19") (name "IN_3V3_EDGE10") (class "Default")
      (node (ref "IC16") (pin "8") (pinfunction "OUT_8") (pintype "output"))
      (node (ref "J10") (pin "19") (pinfunction "19_19") (pintype "passive"))
    )
    (net (code "20") (name "IN_3V3_EMRGN_CHN") (class "Default")
      (node (ref "EMRG_CHN") (pin "1") (pinfunction "1_1") (pintype "bidirectional"))
      (node (ref "J10") (pin "6") (pinfunction "6_6") (pintype "passive"))
      (node (ref "J4/J2") (pin "2") (pinfunction "3_2") (pintype "passive"))
    )
    (net (code "21") (name "IN_3V3_HOMING_SENS_M1") (class "Default")
      (node (ref "IC1") (pin "1") (pinfunction "OUT_1") (pintype "output"))
      (node (ref "J1/J3") (pin "5") (pinfunction "9_5") (pintype "passive"))
    )
    (net (code "22") (name "IN_3V3_HOMING_SENS_M2") (class "Default")
      (node (ref "IC1") (pin "7") (pinfunction "OUT_7") (pintype "output"))
      (node (ref "J1/J3") (pin "8") (pinfunction "15_8") (pintype "passive"))
    )
    (net (code "23") (name "IN_3V3_M1_ALARM") (class "Default")
      (node (ref "J1/J3") (pin "10") (pinfunction "19_10") (pintype "passive"))
      (node (ref "MOT1") (pin "37") (pinfunction "37_37") (pintype "passive"))
    )
    (net (code "24") (name "IN_3V3_M1_ENC_PHZ") (class "Default")
      (node (ref "EN_M1_ENC_PHZ") (pin "1") (pinfunction "1_1") (pintype "passive"))
      (node (ref "U4") (pin "14") (pinfunction "1Y3_14") (pintype "output"))
    )
    (net (code "25") (name "IN_3V3_M1_ENC_PH_N") (class "Default")
      (node (ref "J5/J7") (pin "8") (pinfunction "15_8") (pintype "passive"))
      (node (ref "U4") (pin "16") (pinfunction "1Y2_16") (pintype "output"))
    )
    (net (code "26") (name "IN_3V3_M1_ENC_PH_P") (class "Default")
      (node (ref "J1/J3") (pin "7") (pinfunction "13_7") (pintype "passive"))
      (node (ref "U4") (pin "18") (pinfunction "1Y1_18") (pintype "output"))
    )
    (net (code "27") (name "IN_3V3_M1_READY") (class "Default")
      (node (ref "J4/J2") (pin "7") (pinfunction "13_7") (pintype "passive"))
      (node (ref "MOT1") (pin "35") (pinfunction "35_35") (pintype "passive"))
    )
    (net (code "28") (name "IN_3V3_M2_ALARM") (class "Default")
      (node (ref "J4/J2") (pin "1") (pinfunction "1_1") (pintype "passive"))
      (node (ref "MOT2") (pin "37") (pinfunction "37_37") (pintype "passive"))
    )
    (net (code "29") (name "IN_3V3_M2_ENC_PHZ") (class "Default")
      (node (ref "EN_M2_ENC_PHZ") (pin "1") (pinfunction "1_1") (pintype "passive"))
      (node (ref "U4") (pin "5") (pinfunction "2Y3_5") (pintype "output"))
    )
    (net (code "30") (name "IN_3V3_M2_ENC_PH_N") (class "Default")
      (node (ref "J10") (pin "22") (pinfunction "22_22") (pintype "passive"))
      (node (ref "U4") (pin "3") (pinfunction "2Y4_3") (pintype "output"))
    )
    (net (code "31") (name "IN_3V3_M2_ENC_PH_P") (class "Default")
      (node (ref "J8/J6") (pin "12") (pinfunction "4_12") (pintype "passive"))
      (node (ref "U4") (pin "12") (pinfunction "1Y4_12") (pintype "output"))
    )
    (net (code "32") (name "IN_3V3_M2_READY") (class "Default")
      (node (ref "J4/J2") (pin "9") (pinfunction "17_9") (pintype "passive"))
      (node (ref "MOT2") (pin "35") (pinfunction "35_35") (pintype "passive"))
    )
    (net (code "33") (name "IN_3V3_MZ_ALARM") (class "Default")
      (node (ref "IC17") (pin "14") (pinfunction "OUT_14") (pintype "output"))
      (node (ref "J1/J3") (pin "9") (pinfunction "17_9") (pintype "passive"))
    )
    (net (code "34") (name "IN_3V3_SCI_RX") (class "Default")
      (node (ref "J1/J3") (pin "3") (pinfunction "5_3") (pintype "passive"))
      (node (ref "U6") (pin "3") (pinfunction "2Y4_3") (pintype "output"))
    )
    (net (code "35") (name "IN_3V3_TEMP_ALARM") (class "Default")
      (node (ref "IC1") (pin "8") (pinfunction "OUT_8") (pintype "output"))
      (node (ref "J4/J2") (pin "20") (pinfunction "20_20") (pintype "passive"))
    )
    (net (code "36") (name "IN_5V_GPI1_0V-30V") (class "Default")
      (node (ref "IC12") (pin "14") (pinfunction "OUT_14") (pintype "output"))
      (node (ref "J_ARD") (pin "32") (pinfunction "32_32") (pintype "passive"))
    )
    (net (code "37") (name "IN_5V_GPI2_0V-30V") (class "Default")
      (node (ref "IC12") (pin "8") (pinfunction "OUT_8") (pintype "output"))
      (node (ref "J_ARD") (pin "28") (pinfunction "28_28") (pintype "passive"))
    )
    (net (code "38") (name "IN_5V_GPI3_0V-30V") (class "Default")
      (node (ref "IC12") (pin "7") (pinfunction "OUT_7") (pintype "output"))
      (node (ref "J_ARD") (pin "27") (pinfunction "27_27") (pintype "passive"))
    )
    (net (code "39") (name "IN_5V_GPI4_0V-30V") (class "Default")
      (node (ref "IC13") (pin "1") (pinfunction "OUT_1") (pintype "output"))
      (node (ref "J_ARD") (pin "29") (pinfunction "29_29") (pintype "passive"))
    )
    (net (code "40") (name "IN_5V_GPI5_0V-30V") (class "Default")
      (node (ref "IC13") (pin "7") (pinfunction "OUT_7") (pintype "output"))
      (node (ref "J_ARD") (pin "33") (pinfunction "33_33") (pintype "passive"))
    )
    (net (code "41") (name "IN_5V_GPI6_0V-30V") (class "Default")
      (node (ref "IC13") (pin "8") (pinfunction "OUT_8") (pintype "output"))
      (node (ref "J_ARD") (pin "30") (pinfunction "30_30") (pintype "passive"))
    )
    (net (code "42") (name "IN_5V_GPI7_0V-30V") (class "Default")
      (node (ref "IC13") (pin "14") (pinfunction "OUT_14") (pintype "output"))
      (node (ref "J_ARD") (pin "31") (pinfunction "31_31") (pintype "passive"))
    )
    (net (code "43") (name "IN_5V_GPI8_0V-30V") (class "Default")
      (node (ref "IC14") (pin "1") (pinfunction "OUT_1") (pintype "output"))
      (node (ref "J_ARD") (pin "34") (pinfunction "34_34") (pintype "passive"))
    )
    (net (code "44") (name "IN_5V_GPI9_0V-30V") (class "Default")
      (node (ref "IC14") (pin "7") (pinfunction "OUT_7") (pintype "output"))
      (node (ref "J_ARD") (pin "35") (pinfunction "35_35") (pintype "passive"))
    )
    (net (code "45") (name "IN_5V_GPI10_0V-30V") (class "Default")
      (node (ref "IC14") (pin "8") (pinfunction "OUT_8") (pintype "output"))
      (node (ref "J_ARD") (pin "36") (pinfunction "36_36") (pintype "passive"))
    )
    (net (code "46") (name "IN_5V_M1_ENC_PHZ") (class "Default")
      (node (ref "MOT1") (pin "23") (pinfunction "23_23") (pintype "passive"))
      (node (ref "U4") (pin "6") (pinfunction "1A3_6") (pintype "input"))
    )
    (net (code "47") (name "IN_5V_M1_ENC_PH_N") (class "Default")
      (node (ref "MOT1") (pin "49") (pinfunction "49_49") (pintype "passive"))
      (node (ref "U4") (pin "4") (pinfunction "1A2_4") (pintype "input"))
    )
    (net (code "48") (name "IN_5V_M1_ENC_PH_P") (class "Default")
      (node (ref "MOT1") (pin "21") (pinfunction "21_21") (pintype "passive"))
      (node (ref "U4") (pin "2") (pinfunction "1A1_2") (pintype "input"))
    )
    (net (code "49") (name "IN_5V_M2_ENC_PHZ") (class "Default")
      (node (ref "MOT2") (pin "23") (pinfunction "23_23") (pintype "passive"))
      (node (ref "U4") (pin "15") (pinfunction "2A3_15") (pintype "input"))
    )
    (net (code "50") (name "IN_5V_M2_ENC_PH_N") (class "Default")
      (node (ref "MOT2") (pin "49") (pinfunction "49_49") (pintype "passive"))
      (node (ref "U4") (pin "17") (pinfunction "2A4_17") (pintype "input"))
    )
    (net (code "51") (name "IN_5V_M2_ENC_PH_P") (class "Default")
      (node (ref "MOT2") (pin "21") (pinfunction "21_21") (pintype "passive"))
      (node (ref "U4") (pin "8") (pinfunction "1A4_8") (pintype "input"))
    )
    (net (code "52") (name "IN_5V_RX") (class "Default")
      (node (ref "J_ARD") (pin "4") (pinfunction "4_4") (pintype "passive"))
      (node (ref "U6") (pin "18") (pinfunction "1Y1_18") (pintype "output"))
    )
    (net (code "53") (name "IN_24V_HOMING_SENS_M1") (class "Default")
      (node (ref "IC1") (pin "3") (pinfunction "+IN_3") (pintype "input"))
      (node (ref "PROXYM_M1") (pin "1") (pinfunction "1_1") (pintype "bidirectional"))
    )
    (net (code "54") (name "IN_24V_HOMING_SENS_M2") (class "Default")
      (node (ref "IC1") (pin "5") (pinfunction "+IN_5") (pintype "input"))
      (node (ref "PROXYM_M2") (pin "1") (pinfunction "1_1") (pintype "bidirectional"))
    )
    (net (code "55") (name "IN_24V_MZ_ALARM") (class "Default")
      (node (ref "IC17") (pin "12") (pinfunction "+IN_12") (pintype "input"))
      (node (ref "MOTZ") (pin "8") (pinfunction "8_8") (pintype "passive"))
    )
    (net (code "56") (name "IN_30V_EDGE1") (class "Default")
      (node (ref "IC15") (pin "12") (pinfunction "+IN_12") (pintype "input"))
      (node (ref "JI_TEXAS") (pin "11") (pinfunction "2_11") (pintype "passive"))
    )
    (net (code "57") (name "IN_30V_EDGE2") (class "Default")
      (node (ref "IC15") (pin "10") (pinfunction "+IN_10") (pintype "input"))
      (node (ref "JI_TEXAS") (pin "12") (pinfunction "4_12") (pintype "passive"))
    )
    (net (code "58") (name "IN_30V_EDGE3") (class "Default")
      (node (ref "IC15") (pin "5") (pinfunction "+IN_5") (pintype "input"))
      (node (ref "JI_TEXAS") (pin "13") (pinfunction "6_13") (pintype "passive"))
    )
    (net (code "59") (name "IN_30V_EDGE4") (class "Default")
      (node (ref "IC17") (pin "3") (pinfunction "+IN_3") (pintype "input"))
      (node (ref "JI_TEXAS") (pin "14") (pinfunction "8_14") (pintype "passive"))
    )
    (net (code "60") (name "IN_30V_EDGE5") (class "Default")
      (node (ref "IC17") (pin "5") (pinfunction "+IN_5") (pintype "input"))
      (node (ref "JI_TEXAS") (pin "15") (pinfunction "10_15") (pintype "passive"))
    )
    (net (code "61") (name "IN_30V_EDGE6") (class "Default")
      (node (ref "IC17") (pin "10") (pinfunction "+IN_10") (pintype "input"))
      (node (ref "JI_TEXAS") (pin "16") (pinfunction "12_16") (pintype "passive"))
    )
    (net (code "62") (name "IN_30V_EDGE7") (class "Default")
      (node (ref "IC16") (pin "3") (pinfunction "+IN_3") (pintype "input"))
      (node (ref "JI_TEXAS") (pin "17") (pinfunction "14_17") (pintype "passive"))
    )
    (net (code "63") (name "IN_30V_EDGE8") (class "Default")
      (node (ref "IC16") (pin "5") (pinfunction "+IN_5") (pintype "input"))
      (node (ref "JI_TEXAS") (pin "18") (pinfunction "16_18") (pintype "passive"))
    )
    (net (code "64") (name "IN_30V_EDGE9") (class "Default")
      (node (ref "IC16") (pin "12") (pinfunction "+IN_12") (pintype "input"))
      (node (ref "JI_TEXAS") (pin "19") (pinfunction "18_19") (pintype "passive"))
    )
    (net (code "65") (name "IN_30V_EDGE10") (class "Default")
      (node (ref "IC16") (pin "10") (pinfunction "+IN_10") (pintype "input"))
      (node (ref "JI_TEXAS") (pin "20") (pinfunction "20_20") (pintype "passive"))
    )
    (net (code "66") (name "IN_30V_GPI1") (class "Default")
      (node (ref "IC12") (pin "12") (pinfunction "+IN_12") (pintype "input"))
      (node (ref "JI_ARD") (pin "11") (pinfunction "2_11") (pintype "passive"))
    )
    (net (code "67") (name "IN_30V_GPI2") (class "Default")
      (node (ref "IC12") (pin "10") (pinfunction "+IN_10") (pintype "input"))
      (node (ref "JI_ARD") (pin "12") (pinfunction "4_12") (pintype "passive"))
    )
    (net (code "68") (name "IN_30V_GPI3") (class "Default")
      (node (ref "IC12") (pin "5") (pinfunction "+IN_5") (pintype "input"))
      (node (ref "JI_ARD") (pin "13") (pinfunction "6_13") (pintype "passive"))
    )
    (net (code "69") (name "IN_30V_GPI4") (class "Default")
      (node (ref "IC13") (pin "3") (pinfunction "+IN_3") (pintype "input"))
      (node (ref "JI_ARD") (pin "14") (pinfunction "8_14") (pintype "passive"))
    )
    (net (code "70") (name "IN_30V_GPI5") (class "Default")
      (node (ref "IC13") (pin "5") (pinfunction "+IN_5") (pintype "input"))
      (node (ref "JI_ARD") (pin "15") (pinfunction "10_15") (pintype "passive"))
    )
    (net (code "71") (name "IN_30V_GPI6") (class "Default")
      (node (ref "IC13") (pin "10") (pinfunction "+IN_10") (pintype "input"))
      (node (ref "JI_ARD") (pin "16") (pinfunction "12_16") (pintype "passive"))
    )
    (net (code "72") (name "IN_30V_GPI7") (class "Default")
      (node (ref "IC13") (pin "12") (pinfunction "+IN_12") (pintype "input"))
      (node (ref "JI_ARD") (pin "17") (pinfunction "14_17") (pintype "passive"))
    )
    (net (code "73") (name "IN_30V_GPI8") (class "Default")
      (node (ref "IC14") (pin "3") (pinfunction "+IN_3") (pintype "input"))
      (node (ref "JI_ARD") (pin "18") (pinfunction "16_18") (pintype "passive"))
    )
    (net (code "74") (name "IN_30V_GPI9") (class "Default")
      (node (ref "IC14") (pin "5") (pinfunction "+IN_5") (pintype "input"))
      (node (ref "JI_ARD") (pin "19") (pinfunction "18_19") (pintype "passive"))
    )
    (net (code "75") (name "IN_30V_GPI10") (class "Default")
      (node (ref "IC14") (pin "10") (pinfunction "+IN_10") (pintype "input"))
      (node (ref "JI_ARD") (pin "20") (pinfunction "20_20") (pintype "passive"))
    )
    (net (code "76") (name "I{slash}O_3V3_GPIO1") (class "Default")
      (node (ref "J10") (pin "39") (pinfunction "39_39") (pintype "passive"))
      (node (ref "J_GPO/I2C_H1") (pin "20") (pinfunction "20_20") (pintype "passive"))
    )
    (net (code "77") (name "I{slash}O_3V3_I2C_SCL") (class "Default")
      (node (ref "J10") (pin "8") (pinfunction "8_8") (pintype "passive"))
      (node (ref "J_GPO/I2C_H1") (pin "18") (pinfunction "16_18") (pintype "passive"))
    )
    (net (code "78") (name "I{slash}O_3V3_I2C_SDA") (class "Default")
      (node (ref "J10") (pin "9") (pinfunction "9_9") (pintype "passive"))
      (node (ref "J_GPO/I2C_H1") (pin "19") (pinfunction "18_19") (pintype "passive"))
    )
    (net (code "79") (name "I{slash}O_M1_1") (class "Default")
      (node (ref "J4") (pin "1") (pinfunction "1_1") (pintype "passive"))
      (node (ref "MOT1") (pin "1") (pinfunction "1_1") (pintype "passive"))
    )
    (net (code "80") (name "I{slash}O_M1_2") (class "Default")
      (node (ref "J4") (pin "2") (pinfunction "2_2") (pintype "passive"))
      (node (ref "MOT1") (pin "2") (pinfunction "2_2") (pintype "passive"))
    )
    (net (code "81") (name "I{slash}O_M1_11") (class "Default")
      (node (ref "J4") (pin "3") (pinfunction "3_3") (pintype "passive"))
      (node (ref "MOT1") (pin "11") (pinfunction "11_11") (pintype "passive"))
    )
    (net (code "82") (name "I{slash}O_M1_12") (class "Default")
      (node (ref "J4") (pin "4") (pinfunction "4_4") (pintype "passive"))
      (node (ref "MOT1") (pin "12") (pinfunction "12_12") (pintype "passive"))
    )
    (net (code "83") (name "I{slash}O_M1_13") (class "Default")
      (node (ref "J4") (pin "5") (pinfunction "5_5") (pintype "passive"))
      (node (ref "MOT1") (pin "13") (pinfunction "13_13") (pintype "passive"))
    )
    (net (code "84") (name "I{slash}O_M1_14") (class "Default")
      (node (ref "J4") (pin "6") (pinfunction "6_6") (pintype "passive"))
      (node (ref "MOT1") (pin "14") (pinfunction "14_14") (pintype "passive"))
    )
    (net (code "85") (name "I{slash}O_M1_15") (class "Default")
      (node (ref "J4") (pin "7") (pinfunction "7_7") (pintype "passive"))
      (node (ref "MOT1") (pin "15") (pinfunction "15_15") (pintype "passive"))
    )
    (net (code "86") (name "I{slash}O_M1_16") (class "Default")
      (node (ref "J4") (pin "8") (pinfunction "8_8") (pintype "passive"))
      (node (ref "MOT1") (pin "16") (pinfunction "16_16") (pintype "passive"))
    )
    (net (code "87") (name "I{slash}O_M1_17") (class "Default")
      (node (ref "J4") (pin "9") (pinfunction "9_9") (pintype "passive"))
      (node (ref "MOT1") (pin "17") (pinfunction "17_17") (pintype "passive"))
    )
    (net (code "88") (name "I{slash}O_M1_18") (class "Default")
      (node (ref "J4") (pin "10") (pinfunction "10_10") (pintype "passive"))
      (node (ref "MOT1") (pin "18") (pinfunction "18_18") (pintype "passive"))
    )
    (net (code "89") (name "I{slash}O_M1_19") (class "Default")
      (node (ref "J5") (pin "1") (pinfunction "1_1") (pintype "passive"))
      (node (ref "MOT1") (pin "19") (pinfunction "19_19") (pintype "passive"))
    )
    (net (code "90") (name "I{slash}O_M1_20") (class "Default")
      (node (ref "J5") (pin "2") (pinfunction "2_2") (pintype "passive"))
      (node (ref "MOT1") (pin "20") (pinfunction "20_20") (pintype "passive"))
    )
    (net (code "91") (name "I{slash}O_M1_26") (class "Default")
      (node (ref "J5") (pin "3") (pinfunction "3_3") (pintype "passive"))
      (node (ref "MOT1") (pin "26") (pinfunction "26_26") (pintype "passive"))
    )
    (net (code "92") (name "I{slash}O_M1_27") (class "Default")
      (node (ref "J5") (pin "4") (pinfunction "4_4") (pintype "passive"))
      (node (ref "MOT1") (pin "27") (pinfunction "27_27") (pintype "passive"))
    )
    (net (code "93") (name "I{slash}O_M1_28") (class "Default")
      (node (ref "J5") (pin "5") (pinfunction "5_5") (pintype "passive"))
      (node (ref "MOT1") (pin "28") (pinfunction "28_28") (pintype "passive"))
    )
    (net (code "94") (name "I{slash}O_M1_30") (class "Default")
      (node (ref "J5") (pin "6") (pinfunction "6_6") (pintype "passive"))
      (node (ref "MOT1") (pin "30") (pinfunction "30_30") (pintype "passive"))
    )
    (net (code "95") (name "I{slash}O_M1_31") (class "Default")
      (node (ref "J5") (pin "7") (pinfunction "7_7") (pintype "passive"))
      (node (ref "MOT1") (pin "31") (pinfunction "31_31") (pintype "passive"))
    )
    (net (code "96") (name "I{slash}O_M1_32") (class "Default")
      (node (ref "J5") (pin "8") (pinfunction "8_8") (pintype "passive"))
      (node (ref "MOT1") (pin "32") (pinfunction "32_32") (pintype "passive"))
    )
    (net (code "97") (name "I{slash}O_M1_33") (class "Default")
      (node (ref "J5") (pin "9") (pinfunction "9_9") (pintype "passive"))
      (node (ref "MOT1") (pin "33") (pinfunction "33_33") (pintype "passive"))
    )
    (net (code "98") (name "I{slash}O_M1_39") (class "Default")
      (node (ref "J5") (pin "10") (pinfunction "10_10") (pintype "passive"))
      (node (ref "MOT1") (pin "39") (pinfunction "39_39") (pintype "passive"))
    )
    (net (code "99") (name "I{slash}O_M1_40") (class "Default")
      (node (ref "J6") (pin "1") (pinfunction "1_1") (pintype "passive"))
      (node (ref "MOT1") (pin "40") (pinfunction "40_40") (pintype "passive"))
    )
    (net (code "100") (name "I{slash}O_M1_42") (class "Default")
      (node (ref "J6") (pin "2") (pinfunction "2_2") (pintype "passive"))
      (node (ref "MOT1") (pin "42") (pinfunction "42_42") (pintype "passive"))
    )
    (net (code "101") (name "I{slash}O_M1_43") (class "Default")
      (node (ref "J6") (pin "3") (pinfunction "3_3") (pintype "passive"))
      (node (ref "MOT1") (pin "43") (pinfunction "43_43") (pintype "passive"))
    )
    (net (code "102") (name "I{slash}O_M1_44") (class "Default")
      (node (ref "J6") (pin "4") (pinfunction "4_4") (pintype "passive"))
      (node (ref "MOT1") (pin "44") (pinfunction "44_44") (pintype "passive"))
    )
    (net (code "103") (name "I{slash}O_M1_46") (class "Default")
      (node (ref "J6") (pin "5") (pinfunction "5_5") (pintype "passive"))
      (node (ref "MOT1") (pin "46") (pinfunction "46_46") (pintype "passive"))
    )
    (net (code "104") (name "I{slash}O_M1_50") (class "Default")
      (node (ref "J6") (pin "6") (pinfunction "6_6") (pintype "passive"))
      (node (ref "MOT1") (pin "50") (pinfunction "50_50") (pintype "passive"))
    )
    (net (code "105") (name "I{slash}O_M2_1") (class "Default")
      (node (ref "J1") (pin "1") (pinfunction "1_1") (pintype "passive"))
      (node (ref "MOT2") (pin "1") (pinfunction "1_1") (pintype "passive"))
    )
    (net (code "106") (name "I{slash}O_M2_2") (class "Default")
      (node (ref "J1") (pin "2") (pinfunction "2_2") (pintype "passive"))
      (node (ref "MOT2") (pin "2") (pinfunction "2_2") (pintype "passive"))
    )
    (net (code "107") (name "I{slash}O_M2_11") (class "Default")
      (node (ref "J1") (pin "3") (pinfunction "3_3") (pintype "passive"))
      (node (ref "MOT2") (pin "11") (pinfunction "11_11") (pintype "passive"))
    )
    (net (code "108") (name "I{slash}O_M2_12") (class "Default")
      (node (ref "J1") (pin "4") (pinfunction "4_4") (pintype "passive"))
      (node (ref "MOT2") (pin "12") (pinfunction "12_12") (pintype "passive"))
    )
    (net (code "109") (name "I{slash}O_M2_13") (class "Default")
      (node (ref "J1") (pin "5") (pinfunction "5_5") (pintype "passive"))
      (node (ref "MOT2") (pin "13") (pinfunction "13_13") (pintype "passive"))
    )
    (net (code "110") (name "I{slash}O_M2_14") (class "Default")
      (node (ref "J1") (pin "6") (pinfunction "6_6") (pintype "passive"))
      (node (ref "MOT2") (pin "14") (pinfunction "14_14") (pintype "passive"))
    )
    (net (code "111") (name "I{slash}O_M2_15") (class "Default")
      (node (ref "J1") (pin "7") (pinfunction "7_7") (pintype "passive"))
      (node (ref "MOT2") (pin "15") (pinfunction "15_15") (pintype "passive"))
    )
    (net (code "112") (name "I{slash}O_M2_16") (class "Default")
      (node (ref "J1") (pin "8") (pinfunction "8_8") (pintype "passive"))
      (node (ref "MOT2") (pin "16") (pinfunction "16_16") (pintype "passive"))
    )
    (net (code "113") (name "I{slash}O_M2_17") (class "Default")
      (node (ref "J1") (pin "9") (pinfunction "9_9") (pintype "passive"))
      (node (ref "MOT2") (pin "17") (pinfunction "17_17") (pintype "passive"))
    )
    (net (code "114") (name "I{slash}O_M2_18") (class "Default")
      (node (ref "J1") (pin "10") (pinfunction "10_10") (pintype "passive"))
      (node (ref "MOT2") (pin "18") (pinfunction "18_18") (pintype "passive"))
    )
    (net (code "115") (name "I{slash}O_M2_19") (class "Default")
      (node (ref "J2") (pin "1") (pinfunction "1_1") (pintype "passive"))
      (node (ref "MOT2") (pin "19") (pinfunction "19_19") (pintype "passive"))
    )
    (net (code "116") (name "I{slash}O_M2_20") (class "Default")
      (node (ref "J2") (pin "2") (pinfunction "2_2") (pintype "passive"))
      (node (ref "MOT2") (pin "20") (pinfunction "20_20") (pintype "passive"))
    )
    (net (code "117") (name "I{slash}O_M2_26") (class "Default")
      (node (ref "J2") (pin "3") (pinfunction "3_3") (pintype "passive"))
      (node (ref "MOT2") (pin "26") (pinfunction "26_26") (pintype "passive"))
    )
    (net (code "118") (name "I{slash}O_M2_27") (class "Default")
      (node (ref "J2") (pin "4") (pinfunction "4_4") (pintype "passive"))
      (node (ref "MOT2") (pin "27") (pinfunction "27_27") (pintype "passive"))
    )
    (net (code "119") (name "I{slash}O_M2_28") (class "Default")
      (node (ref "J2") (pin "5") (pinfunction "5_5") (pintype "passive"))
      (node (ref "MOT2") (pin "28") (pinfunction "28_28") (pintype "passive"))
    )
    (net (code "120") (name "I{slash}O_M2_30") (class "Default")
      (node (ref "J2") (pin "6") (pinfunction "6_6") (pintype "passive"))
      (node (ref "MOT2") (pin "30") (pinfunction "30_30") (pintype "passive"))
    )
    (net (code "121") (name "I{slash}O_M2_31") (class "Default")
      (node (ref "J2") (pin "7") (pinfunction "7_7") (pintype "passive"))
      (node (ref "MOT2") (pin "31") (pinfunction "31_31") (pintype "passive"))
    )
    (net (code "122") (name "I{slash}O_M2_32") (class "Default")
      (node (ref "J2") (pin "8") (pinfunction "8_8") (pintype "passive"))
      (node (ref "MOT2") (pin "32") (pinfunction "32_32") (pintype "passive"))
    )
    (net (code "123") (name "I{slash}O_M2_33") (class "Default")
      (node (ref "J2") (pin "9") (pinfunction "9_9") (pintype "passive"))
      (node (ref "MOT2") (pin "33") (pinfunction "33_33") (pintype "passive"))
    )
    (net (code "124") (name "I{slash}O_M2_39") (class "Default")
      (node (ref "J2") (pin "10") (pinfunction "10_10") (pintype "passive"))
      (node (ref "MOT2") (pin "39") (pinfunction "39_39") (pintype "passive"))
    )
    (net (code "125") (name "I{slash}O_M2_40") (class "Default")
      (node (ref "J3") (pin "1") (pinfunction "1_1") (pintype "passive"))
      (node (ref "MOT2") (pin "40") (pinfunction "40_40") (pintype "passive"))
    )
    (net (code "126") (name "I{slash}O_M2_42") (class "Default")
      (node (ref "J3") (pin "2") (pinfunction "2_2") (pintype "passive"))
      (node (ref "MOT2") (pin "42") (pinfunction "42_42") (pintype "passive"))
    )
    (net (code "127") (name "I{slash}O_M2_43") (class "Default")
      (node (ref "J3") (pin "3") (pinfunction "3_3") (pintype "passive"))
      (node (ref "MOT2") (pin "43") (pinfunction "43_43") (pintype "passive"))
    )
    (net (code "128") (name "I{slash}O_M2_44") (class "Default")
      (node (ref "J3") (pin "4") (pinfunction "4_4") (pintype "passive"))
      (node (ref "MOT2") (pin "44") (pinfunction "44_44") (pintype "passive"))
    )
    (net (code "129") (name "I{slash}O_M2_46") (class "Default")
      (node (ref "J3") (pin "5") (pinfunction "5_5") (pintype "passive"))
      (node (ref "MOT2") (pin "46") (pinfunction "46_46") (pintype "passive"))
    )
    (net (code "130") (name "I{slash}O_M2_50") (class "Default")
      (node (ref "J3") (pin "6") (pinfunction "6_6") (pintype "passive"))
      (node (ref "MOT2") (pin "50") (pinfunction "50_50") (pintype "passive"))
    )
    (net (code "131") (name "Net-(IC1D-+IN)") (class "Default")
      (node (ref "IC1") (pin "12") (pinfunction "+IN_12") (pintype "input"))
      (node (ref "R17") (pin "2") (pinfunction "2_2") (pintype "passive"))
    )
    (net (code "132") (name "Net-(IC5D-+IN)") (class "Default")
      (node (ref "IC5") (pin "12") (pinfunction "+IN_12") (pintype "input"))
      (node (ref "R19") (pin "2") (pinfunction "2_2") (pintype "passive"))
    )
    (net (code "133") (name "Net-(IC7D-+IN)") (class "Default")
      (node (ref "IC7") (pin "12") (pinfunction "+IN_12") (pintype "input"))
      (node (ref "R15") (pin "2") (pinfunction "2_2") (pintype "passive"))
    )
    (net (code "134") (name "Net-(IC7E-V+)") (class "Default")
      (node (ref "IC7") (pin "4") (pinfunction "V+_4") (pintype "power_in"))
      (node (ref "OUT_ARD_8-11_5V-24V") (pin "2") (pinfunction "2_2") (pintype "passive"))
    )
    (net (code "135") (name "Net-(IC11E-V+)") (class "Default")
      (node (ref "IC11") (pin "4") (pinfunction "V+_4") (pintype "power_in"))
      (node (ref "OUT_ARD_4-7_5V-24V") (pin "2") (pinfunction "2_2") (pintype "passive"))
    )
    (net (code "136") (name "Net-(IC12A-+IN)") (class "Default")
      (node (ref "IC12") (pin "3") (pinfunction "+IN_3") (pintype "input"))
      (node (ref "R26") (pin "2") (pinfunction "2_2") (pintype "passive"))
    )
    (net (code "137") (name "Net-(IC15A-+IN)") (class "Default")
      (node (ref "IC15") (pin "3") (pinfunction "+IN_3") (pintype "input"))
      (node (ref "R28") (pin "2") (pinfunction "2_2") (pintype "passive"))
    )
    (net (code "138") (name "Net-(J4/J2-15)") (class "Default")
      (node (ref "EN_M2_ENC_PHZ") (pin "2") (pinfunction "2_2") (pintype "passive"))
      (node (ref "J4/J2") (pin "8") (pinfunction "15_8") (pintype "passive"))
    )
    (net (code "139") (name "Net-(J5/J7-9)") (class "Default")
      (node (ref "EN_M1_ENC_PHZ") (pin "2") (pinfunction "2_2") (pintype "passive"))
      (node (ref "J5/J7") (pin "5") (pinfunction "9_5") (pintype "passive"))
    )
    (net (code "140") (name "Net-(PT1-Pad3)") (class "Default")
      (node (ref "PT1") (pin "3") (pinfunction "3_3") (pintype "passive"))
      (node (ref "R5") (pin "1") (pinfunction "1_1") (pintype "passive"))
    )
    (net (code "141") (name "Net-(R1-Pad1)") (class "Default")
      (node (ref "R1") (pin "1") (pinfunction "1_1") (pintype "passive"))
      (node (ref "U$1") (pin "2") (pinfunction "2_2") (pintype "passive"))
    )
    (net (code "142") (name "Net-(R2-Pad1)") (class "Default")
      (node (ref "R2") (pin "1") (pinfunction "1_1") (pintype "passive"))
      (node (ref "U$2") (pin "2") (pinfunction "2_2") (pintype "passive"))
    )
    (net (code "143") (name "Net-(R3-Pad1)") (class "Default")
      (node (ref "R3") (pin "1") (pinfunction "1_1") (pintype "passive"))
      (node (ref "U$3") (pin "2") (pinfunction "2_2") (pintype "passive"))
    )
    (net (code "144") (name "Net-(R4-Pad1)") (class "Default")
      (node (ref "R4") (pin "1") (pinfunction "1_1") (pintype "passive"))
      (node (ref "U$4") (pin "2") (pinfunction "2_2") (pintype "passive"))
    )
    (net (code "145") (name "Net-(R6-Pad1)") (class "Default")
      (node (ref "R6") (pin "1") (pinfunction "1_1") (pintype "passive"))
      (node (ref "U$5") (pin "2") (pinfunction "2_2") (pintype "passive"))
    )
    (net (code "146") (name "Net-(R7-Pad1)") (class "Default")
      (node (ref "R7") (pin "1") (pinfunction "1_1") (pintype "passive"))
      (node (ref "U$6") (pin "2") (pinfunction "2_2") (pintype "passive"))
    )
    (net (code "147") (name "Net-(R8-Pad1)") (class "Default")
      (node (ref "R8") (pin "1") (pinfunction "1_1") (pintype "passive"))
      (node (ref "U$7") (pin "2") (pinfunction "2_2") (pintype "passive"))
    )
    (net (code "148") (name "Net-(R9-Pad1)") (class "Default")
      (node (ref "R9") (pin "1") (pinfunction "1_1") (pintype "passive"))
      (node (ref "U$8") (pin "2") (pinfunction "2_2") (pintype "passive"))
    )
    (net (code "149") (name "Net-(R10-Pad1)") (class "Default")
      (node (ref "R10") (pin "1") (pinfunction "1_1") (pintype "passive"))
      (node (ref "U$9") (pin "2") (pinfunction "2_2") (pintype "passive"))
    )
    (net (code "150") (name "Net-(R11-Pad1)") (class "Default")
      (node (ref "R11") (pin "1") (pinfunction "1_1") (pintype "passive"))
      (node (ref "U$10") (pin "2") (pinfunction "2_2") (pintype "passive"))
    )
    (net (code "151") (name "Net-(R12-Pad1)") (class "Default")
      (node (ref "R12") (pin "1") (pinfunction "1_1") (pintype "passive"))
      (node (ref "U$11") (pin "2") (pinfunction "2_2") (pintype "passive"))
    )
    (net (code "152") (name "Net-(R13-Pad1)") (class "Default")
      (node (ref "R13") (pin "1") (pinfunction "1_1") (pintype "passive"))
      (node (ref "U$12") (pin "2") (pinfunction "2_2") (pintype "passive"))
    )
    (net (code "153") (name "Net-(R14-Pad1)") (class "Default")
      (node (ref "R14") (pin "1") (pinfunction "1_1") (pintype "passive"))
      (node (ref "R15") (pin "1") (pinfunction "1_1") (pintype "passive"))
    )
    (net (code "154") (name "Net-(R16-Pad1)") (class "Default")
      (node (ref "R16") (pin "1") (pinfunction "1_1") (pintype "passive"))
      (node (ref "R17") (pin "1") (pinfunction "1_1") (pintype "passive"))
    )
    (net (code "155") (name "Net-(R18-Pad1)") (class "Default")
      (node (ref "R18") (pin "1") (pinfunction "1_1") (pintype "passive"))
      (node (ref "R19") (pin "1") (pinfunction "1_1") (pintype "passive"))
    )
    (net (code "156") (name "Net-(R25-Pad1)") (class "Default")
      (node (ref "R25") (pin "1") (pinfunction "1_1") (pintype "passive"))
      (node (ref "R26") (pin "1") (pinfunction "1_1") (pintype "passive"))
    )
    (net (code "157") (name "Net-(R27-Pad1)") (class "Default")
      (node (ref "R27") (pin "1") (pinfunction "1_1") (pintype "passive"))
      (node (ref "R28") (pin "1") (pinfunction "1_1") (pintype "passive"))
    )
    (net (code "158") (name "Net-(R29-Pad1)") (class "Default")
      (node (ref "R29") (pin "1") (pinfunction "1_1") (pintype "passive"))
      (node (ref "U$15") (pin "2") (pinfunction "2_2") (pintype "passive"))
    )
    (net (code "159") (name "Net-(U$13-1)") (class "Default")
      (node (ref "R5") (pin "2") (pinfunction "2_2") (pintype "passive"))
      (node (ref "U$13") (pin "P$1") (pinfunction "1_P$1") (pintype "passive"))
      (node (ref "U$14") (pin "1") (pinfunction "+_1") (pintype "passive"))
    )
    (net (code "160") (name "Net-(U4-~{1G})") (class "Default")
      (node (ref "EN_IN_ENC") (pin "2") (pinfunction "2_2") (pintype "passive"))
      (node (ref "U4") (pin "1") (pinfunction "~{1G}_1") (pintype "input"))
      (node (ref "U4") (pin "19") (pinfunction "~{G/2G}_19") (pintype "input"))
    )
    (net (code "161") (name "Net-(U5-~{1G})") (class "Default")
      (node (ref "EN_OUT_MOT") (pin "2") (pinfunction "2_2") (pintype "passive"))
      (node (ref "U5") (pin "1") (pinfunction "~{1G}_1") (pintype "input"))
      (node (ref "U5") (pin "19") (pinfunction "~{G/2G}_19") (pintype "input"))
    )
    (net (code "162") (name "Net-(U6-~{1G})") (class "Default")
      (node (ref "EN_SCI") (pin "2") (pinfunction "2_2") (pintype "passive"))
      (node (ref "U6") (pin "1") (pinfunction "~{1G}_1") (pintype "input"))
      (node (ref "U6") (pin "19") (pinfunction "~{G/2G}_19") (pintype "input"))
    )
    (net (code "163") (name "Net-(U7-~{1G})") (class "Default")
      (node (ref "EN_GPO_H") (pin "2") (pinfunction "2_2") (pintype "passive"))
      (node (ref "U7") (pin "1") (pinfunction "~{1G}_1") (pintype "input"))
      (node (ref "U7") (pin "19") (pinfunction "~{G/2G}_19") (pintype "input"))
    )
    (net (code "164") (name "OUT_3V3_GPO1_H") (class "Default")
      (node (ref "J10") (pin "34") (pinfunction "34_34") (pintype "passive"))
      (node (ref "U7") (pin "8") (pinfunction "1A4_8") (pintype "input"))
    )
    (net (code "165") (name "OUT_3V3_GPO2_H") (class "Default")
      (node (ref "J9") (pin "20") (pinfunction "20_20") (pintype "passive"))
      (node (ref "U7") (pin "6") (pinfunction "1A3_6") (pintype "input"))
    )
    (net (code "166") (name "OUT_3V3_GPO3_H") (class "Default")
      (node (ref "J9") (pin "18") (pinfunction "18_18") (pintype "passive"))
      (node (ref "U7") (pin "4") (pinfunction "1A2_4") (pintype "input"))
    )
    (net (code "167") (name "OUT_3V3_GPO4_H") (class "Default")
      (node (ref "J9") (pin "17") (pinfunction "17_17") (pintype "passive"))
      (node (ref "U7") (pin "2") (pinfunction "1A1_2") (pintype "input"))
    )
    (net (code "168") (name "OUT_3V3_GPO5_H") (class "Default")
      (node (ref "J9") (pin "14") (pinfunction "14_14") (pintype "passive"))
      (node (ref "U7") (pin "13") (pinfunction "2A2_13") (pintype "input"))
    )
    (net (code "169") (name "OUT_3V3_GPO6_H") (class "Default")
      (node (ref "J9") (pin "11") (pinfunction "11_11") (pintype "passive"))
      (node (ref "U7") (pin "15") (pinfunction "2A3_15") (pintype "input"))
    )
    (net (code "170") (name "OUT_3V3_GPO7_H") (class "Default")
      (node (ref "J9") (pin "10") (pinfunction "10_10") (pintype "passive"))
      (node (ref "U7") (pin "17") (pinfunction "2A4_17") (pintype "input"))
    )
    (net (code "171") (name "OUT_3V3_M1_CCW") (class "Default")
      (node (ref "J8/J6") (pin "4") (pinfunction "7_4") (pintype "passive"))
      (node (ref "U5") (pin "4") (pinfunction "1A2_4") (pintype "input"))
    )
    (net (code "172") (name "OUT_3V3_M1_CW") (class "Default")
      (node (ref "J8/J6") (pin "3") (pinfunction "5_3") (pintype "passive"))
      (node (ref "U5") (pin "2") (pinfunction "1A1_2") (pintype "input"))
    )
    (net (code "173") (name "OUT_3V3_M1_RUN") (class "Default")
      (node (ref "J10") (pin "7") (pinfunction "7_7") (pintype "passive"))
      (node (ref "U1") (pin "3") (pinfunction "IN3_3") (pintype "input"))
    )
    (net (code "174") (name "OUT_3V3_M2_CCW") (class "Default")
      (node (ref "J9") (pin "8") (pinfunction "8_8") (pintype "passive"))
      (node (ref "U5") (pin "8") (pinfunction "1A4_8") (pintype "input"))
    )
    (net (code "175") (name "OUT_3V3_M2_CW") (class "Default")
      (node (ref "J8/J6") (pin "6") (pinfunction "11_6") (pintype "passive"))
      (node (ref "U5") (pin "6") (pinfunction "1A3_6") (pintype "input"))
    )
    (net (code "176") (name "OUT_3V3_M2_RUN") (class "Default")
      (node (ref "J10") (pin "18") (pinfunction "18_18") (pintype "passive"))
      (node (ref "U1") (pin "6") (pinfunction "IN6_6") (pintype "input"))
    )
    (net (code "177") (name "OUT_3V3_MZ_DIR") (class "Default")
      (node (ref "IC5") (pin "10") (pinfunction "+IN_10") (pintype "input"))
      (node (ref "J5/J7") (pin "9") (pinfunction "17_9") (pintype "passive"))
    )
    (net (code "178") (name "OUT_3V3_MZ_EN") (class "Default")
      (node (ref "J10") (pin "37") (pinfunction "37_37") (pintype "passive"))
      (node (ref "U2") (pin "1") (pinfunction "IN1_1") (pintype "input"))
    )
    (net (code "179") (name "OUT_3V3_MZ_IMP") (class "Default")
      (node (ref "IC5") (pin "5") (pinfunction "+IN_5") (pintype "input"))
      (node (ref "J8/J6") (pin "2") (pinfunction "3_2") (pintype "passive"))
    )
    (net (code "180") (name "OUT_3V3_MZ_TRIGGER") (class "Default")
      (node (ref "IC5") (pin "3") (pinfunction "+IN_3") (pintype "input"))
      (node (ref "J8/J6") (pin "1") (pinfunction "1_1") (pintype "passive"))
    )
    (net (code "181") (name "OUT_3V3_SCI_TX") (class "Default")
      (node (ref "J1/J3") (pin "4") (pinfunction "7_4") (pintype "passive"))
      (node (ref "U6") (pin "2") (pinfunction "1A1_2") (pintype "input"))
    )
    (net (code "182") (name "OUT_5V_ELVALV_24V") (class "Default")
      (node (ref "J_ARD") (pin "17") (pinfunction "17_17") (pintype "passive"))
      (node (ref "U2") (pin "3") (pinfunction "IN3_3") (pintype "input"))
    )
    (net (code "183") (name "OUT_5V_GPO1_24V") (class "Default")
      (node (ref "J_ARD") (pin "18") (pinfunction "18_18") (pintype "passive"))
      (node (ref "U2") (pin "4") (pinfunction "IN4_4") (pintype "input"))
    )
    (net (code "184") (name "OUT_5V_GPO1_H") (class "Default")
      (node (ref "J_GPO/I2C_H1") (pin "11") (pinfunction "2_11") (pintype "passive"))
      (node (ref "U7") (pin "12") (pinfunction "1Y4_12") (pintype "output"))
    )
    (net (code "185") (name "OUT_5V_GPO2_24V") (class "Default")
      (node (ref "J_ARD") (pin "19") (pinfunction "19_19") (pintype "passive"))
      (node (ref "U2") (pin "5") (pinfunction "IN5_5") (pintype "input"))
    )
    (net (code "186") (name "OUT_5V_GPO2_H") (class "Default")
      (node (ref "J_GPO/I2C_H1") (pin "12") (pinfunction "4_12") (pintype "passive"))
      (node (ref "U7") (pin "14") (pinfunction "1Y3_14") (pintype "output"))
    )
    (net (code "187") (name "OUT_5V_GPO3_H") (class "Default")
      (node (ref "J_GPO/I2C_H1") (pin "13") (pinfunction "6_13") (pintype "passive"))
      (node (ref "U7") (pin "16") (pinfunction "1Y2_16") (pintype "output"))
    )
    (net (code "188") (name "OUT_5V_GPO4_24V-5V") (class "Default")
      (node (ref "IC11") (pin "12") (pinfunction "+IN_12") (pintype "input"))
      (node (ref "J_ARD") (pin "23") (pinfunction "23_23") (pintype "passive"))
    )
    (net (code "189") (name "OUT_5V_GPO4_H") (class "Default")
      (node (ref "J_GPO/I2C_H1") (pin "14") (pinfunction "8_14") (pintype "passive"))
      (node (ref "U7") (pin "18") (pinfunction "1Y1_18") (pintype "output"))
    )
    (net (code "190") (name "OUT_5V_GPO5_24V-5V") (class "Default")
      (node (ref "IC11") (pin "3") (pinfunction "+IN_3") (pintype "input"))
      (node (ref "J_ARD") (pin "20") (pinfunction "20_20") (pintype "passive"))
    )
    (net (code "191") (name "OUT_5V_GPO5_H") (class "Default")
      (node (ref "J_GPO/I2C_H1") (pin "15") (pinfunction "10_15") (pintype "passive"))
      (node (ref "U7") (pin "7") (pinfunction "2Y2_7") (pintype "output"))
    )
    (net (code "192") (name "OUT_5V_GPO6_24V-5V") (class "Default")
      (node (ref "IC11") (pin "5") (pinfunction "+IN_5") (pintype "input"))
      (node (ref "J_ARD") (pin "21") (pinfunction "21_21") (pintype "passive"))
    )
    (net (code "193") (name "OUT_5V_GPO6_H") (class "Default")
      (node (ref "J_GPO/I2C_H1") (pin "16") (pinfunction "12_16") (pintype "passive"))
      (node (ref "U7") (pin "5") (pinfunction "2Y3_5") (pintype "output"))
    )
    (net (code "194") (name "OUT_5V_GPO7_24V-5V") (class "Default")
      (node (ref "IC11") (pin "10") (pinfunction "+IN_10") (pintype "input"))
      (node (ref "J_ARD") (pin "22") (pinfunction "22_22") (pintype "passive"))
    )
    (net (code "195") (name "OUT_5V_GPO7_H") (class "Default")
      (node (ref "J_GPO/I2C_H1") (pin "17") (pinfunction "14_17") (pintype "passive"))
      (node (ref "U7") (pin "3") (pinfunction "2Y4_3") (pintype "output"))
    )
    (net (code "196") (name "OUT_5V_GPO8_24V-5V") (class "Default")
      (node (ref "IC7") (pin "3") (pinfunction "+IN_3") (pintype "input"))
      (node (ref "J_ARD") (pin "24") (pinfunction "24_24") (pintype "passive"))
    )
    (net (code "197") (name "OUT_5V_GPO9_24V-5V") (class "Default")
      (node (ref "IC7") (pin "5") (pinfunction "+IN_5") (pintype "input"))
      (node (ref "J_ARD") (pin "25") (pinfunction "25_25") (pintype "passive"))
    )
    (net (code "198") (name "OUT_5V_GPO10_24V-5V") (class "Default")
      (node (ref "IC7") (pin "10") (pinfunction "+IN_10") (pintype "input"))
      (node (ref "J_ARD") (pin "26") (pinfunction "26_26") (pintype "passive"))
    )
    (net (code "199") (name "OUT_5V_LAMPADA_1") (class "Default")
      (node (ref "J_ARD") (pin "12") (pinfunction "12_12") (pintype "passive"))
      (node (ref "J_LAMPADE") (pin "1") (pinfunction "1_1") (pintype "passive"))
    )
    (net (code "200") (name "OUT_5V_LAMPADA_2") (class "Default")
      (node (ref "J_ARD") (pin "13") (pinfunction "13_13") (pintype "passive"))
      (node (ref "J_LAMPADE") (pin "3") (pinfunction "3_3") (pintype "passive"))
    )
    (net (code "201") (name "OUT_5V_LAMPADA_3") (class "Default")
      (node (ref "J_ARD") (pin "14") (pinfunction "14_14") (pintype "passive"))
      (node (ref "J_LAMPADE") (pin "5") (pinfunction "5_5") (pintype "passive"))
    )
    (net (code "202") (name "OUT_5V_LAMPADA_4") (class "Default")
      (node (ref "J_ARD") (pin "15") (pinfunction "15_15") (pintype "passive"))
      (node (ref "J_LAMPADE") (pin "7") (pinfunction "7_7") (pintype "passive"))
    )
    (net (code "203") (name "OUT_5V_LAMPADA_5") (class "Default")
      (node (ref "J_ARD") (pin "16") (pinfunction "16_16") (pintype "passive"))
      (node (ref "J_LAMPADE") (pin "9") (pinfunction "9_9") (pintype "passive"))
    )
    (net (code "204") (name "OUT_5V_M1_CCW") (class "Default")
      (node (ref "MOT1") (pin "5") (pinfunction "5_5") (pintype "passive"))
      (node (ref "U5") (pin "16") (pinfunction "1Y2_16") (pintype "output"))
    )
    (net (code "205") (name "OUT_5V_M1_CCW_INIB") (class "Default")
      (node (ref "J_ARD") (pin "6") (pinfunction "6_6") (pintype "passive"))
      (node (ref "U1") (pin "2") (pinfunction "IN2_2") (pintype "input"))
    )
    (net (code "206") (name "OUT_5V_M1_CW") (class "Default")
      (node (ref "MOT1") (pin "3") (pinfunction "3_3") (pintype "passive"))
      (node (ref "U5") (pin "18") (pinfunction "1Y1_18") (pintype "output"))
    )
    (net (code "207") (name "OUT_5V_M1_CW_INIB") (class "Default")
      (node (ref "J_ARD") (pin "7") (pinfunction "7_7") (pintype "passive"))
      (node (ref "U1") (pin "1") (pinfunction "IN1_1") (pintype "input"))
    )
    (net (code "208") (name "OUT_5V_M2_BRAKE") (class "Default")
      (node (ref "J_ARD") (pin "10") (pinfunction "10_10") (pintype "passive"))
      (node (ref "U1") (pin "7") (pinfunction "IN7_7") (pintype "input"))
    )
    (net (code "209") (name "OUT_5V_M2_CCW") (class "Default")
      (node (ref "MOT2") (pin "5") (pinfunction "5_5") (pintype "passive"))
      (node (ref "U5") (pin "12") (pinfunction "1Y4_12") (pintype "output"))
    )
    (net (code "210") (name "OUT_5V_M2_CCW_INIB") (class "Default")
      (node (ref "J_ARD") (pin "8") (pinfunction "8_8") (pintype "passive"))
      (node (ref "U1") (pin "5") (pinfunction "IN5_5") (pintype "input"))
    )
    (net (code "211") (name "OUT_5V_M2_CW") (class "Default")
      (node (ref "MOT2") (pin "3") (pinfunction "3_3") (pintype "passive"))
      (node (ref "U5") (pin "14") (pinfunction "1Y3_14") (pintype "output"))
    )
    (net (code "212") (name "OUT_5V_M2_CW_INIB") (class "Default")
      (node (ref "J_ARD") (pin "9") (pinfunction "9_9") (pintype "passive"))
      (node (ref "U1") (pin "4") (pinfunction "IN4_4") (pintype "input"))
    )
    (net (code "213") (name "OUT_5V_MZ_HOMING") (class "Default")
      (node (ref "J_ARD") (pin "11") (pinfunction "11_11") (pintype "passive"))
      (node (ref "U2") (pin "2") (pinfunction "IN2_2") (pintype "input"))
    )
    (net (code "214") (name "OUT_5V_TX") (class "Default")
      (node (ref "J_ARD") (pin "5") (pinfunction "5_5") (pintype "passive"))
      (node (ref "U6") (pin "17") (pinfunction "2A4_17") (pintype "input"))
    )
    (net (code "215") (name "OUT_24V-5V_GPO4") (class "Default")
      (node (ref "IC11") (pin "14") (pinfunction "OUT_14") (pintype "output"))
      (node (ref "J8") (pin "11") (pinfunction "2_11") (pintype "passive"))
    )
    (net (code "216") (name "OUT_24V-5V_GPO5") (class "Default")
      (node (ref "IC11") (pin "1") (pinfunction "OUT_1") (pintype "output"))
      (node (ref "J8") (pin "12") (pinfunction "4_12") (pintype "passive"))
    )
    (net (code "217") (name "OUT_24V-5V_GPO6") (class "Default")
      (node (ref "IC11") (pin "7") (pinfunction "OUT_7") (pintype "output"))
      (node (ref "J8") (pin "13") (pinfunction "6_13") (pintype "passive"))
    )
    (net (code "218") (name "OUT_24V-5V_GPO7") (class "Default")
      (node (ref "IC11") (pin "8") (pinfunction "OUT_8") (pintype "output"))
      (node (ref "J8") (pin "14") (pinfunction "8_14") (pintype "passive"))
    )
    (net (code "219") (name "OUT_24V-5V_GPO8") (class "Default")
      (node (ref "IC7") (pin "1") (pinfunction "OUT_1") (pintype "output"))
      (node (ref "J8") (pin "15") (pinfunction "10_15") (pintype "passive"))
    )
    (net (code "220") (name "OUT_24V-5V_GPO9") (class "Default")
      (node (ref "IC7") (pin "7") (pinfunction "OUT_7") (pintype "output"))
      (node (ref "J8") (pin "16") (pinfunction "12_16") (pintype "passive"))
    )
    (net (code "221") (name "OUT_24V-5V_GPO10") (class "Default")
      (node (ref "IC7") (pin "8") (pinfunction "OUT_8") (pintype "output"))
      (node (ref "J8") (pin "17") (pinfunction "14_17") (pintype "passive"))
    )
    (net (code "222") (name "OUT_24V_ELVALV") (class "Default")
      (node (ref "EL_VALV") (pin "1") (pinfunction "1_1") (pintype "bidirectional"))
      (node (ref "R22") (pin "1") (pinfunction "1_1") (pintype "passive"))
      (node (ref "U$10") (pin "1") (pinfunction "1_1") (pintype "passive"))
      (node (ref "U2") (pin "14") (pinfunction "OUT3_14") (pintype "output"))
    )
    (net (code "223") (name "OUT_24V_GPO1") (class "Default")
      (node (ref "J7") (pin "1") (pinfunction "1_1") (pintype "passive"))
      (node (ref "R23") (pin "1") (pinfunction "1_1") (pintype "passive"))
      (node (ref "U$11") (pin "1") (pinfunction "1_1") (pintype "passive"))
      (node (ref "U2") (pin "13") (pinfunction "OUT4_13") (pintype "output"))
    )
    (net (code "224") (name "OUT_24V_GPO2") (class "Default")
      (node (ref "J7") (pin "3") (pinfunction "3_3") (pintype "passive"))
      (node (ref "R24") (pin "1") (pinfunction "1_1") (pintype "passive"))
      (node (ref "U$12") (pin "1") (pinfunction "1_1") (pintype "passive"))
      (node (ref "U2") (pin "12") (pinfunction "OUT5_12") (pintype "output"))
    )
    (net (code "225") (name "OUT_24V_MZ_DIR") (class "Default")
      (node (ref "IC5") (pin "8") (pinfunction "OUT_8") (pintype "output"))
      (node (ref "MOTZ") (pin "7") (pinfunction "7_7") (pintype "passive"))
    )
    (net (code "226") (name "OUT_24V_MZ_IMP") (class "Default")
      (node (ref "IC5") (pin "7") (pinfunction "OUT_7") (pintype "output"))
      (node (ref "MOTZ") (pin "6") (pinfunction "6_6") (pintype "passive"))
    )
    (net (code "227") (name "OUT_24V_MZ_TRIGGER") (class "Default")
      (node (ref "IC5") (pin "1") (pinfunction "OUT_1") (pintype "output"))
      (node (ref "MOTZ") (pin "3") (pinfunction "3_3") (pintype "passive"))
    )
    (net (code "228") (name "OUT_M1_BKW_INIB") (class "Default")
      (node (ref "MOT1") (pin "8") (pinfunction "8_8") (pintype "passive"))
      (node (ref "U$2") (pin "1") (pinfunction "1_1") (pintype "passive"))
      (node (ref "U1") (pin "15") (pinfunction "OUT2_15") (pintype "output"))
    )
    (net (code "229") (name "OUT_M1_FWD_INIB") (class "Default")
      (node (ref "MOT1") (pin "9") (pinfunction "9_9") (pintype "passive"))
      (node (ref "U$1") (pin "1") (pinfunction "1_1") (pintype "passive"))
      (node (ref "U1") (pin "16") (pinfunction "OUT1_16") (pintype "output"))
    )
    (net (code "230") (name "OUT_M1_RUN") (class "Default")
      (node (ref "MOT1") (pin "29") (pinfunction "29_29") (pintype "passive"))
      (node (ref "U$3") (pin "1") (pinfunction "1_1") (pintype "passive"))
      (node (ref "U1") (pin "14") (pinfunction "OUT3_14") (pintype "output"))
    )
    (net (code "231") (name "OUT_M2_BKW_INIB") (class "Default")
      (node (ref "MOT2") (pin "8") (pinfunction "8_8") (pintype "passive"))
      (node (ref "U$5") (pin "1") (pinfunction "1_1") (pintype "passive"))
      (node (ref "U1") (pin "12") (pinfunction "OUT5_12") (pintype "output"))
    )
    (net (code "232") (name "OUT_M2_BRAKE") (class "Default")
      (node (ref "BRAKE") (pin "1") (pinfunction "1_1") (pintype "bidirectional"))
      (node (ref "U$7") (pin "1") (pinfunction "1_1") (pintype "passive"))
      (node (ref "U1") (pin "10") (pinfunction "OUT7_10") (pintype "output"))
    )
    (net (code "233") (name "OUT_M2_FWD_INIB") (class "Default")
      (node (ref "MOT2") (pin "9") (pinfunction "9_9") (pintype "passive"))
      (node (ref "U$4") (pin "1") (pinfunction "1_1") (pintype "passive"))
      (node (ref "U1") (pin "13") (pinfunction "OUT4_13") (pintype "output"))
    )
    (net (code "234") (name "OUT_M2_RUN") (class "Default")
      (node (ref "MOT2") (pin "29") (pinfunction "29_29") (pintype "passive"))
      (node (ref "U$6") (pin "1") (pinfunction "1_1") (pintype "passive"))
      (node (ref "U1") (pin "11") (pinfunction "OUT6_11") (pintype "output"))
    )
    (net (code "235") (name "OUT_MZ_EN") (class "Default")
      (node (ref "MOTZ") (pin "9") (pinfunction "9_9") (pintype "passive"))
      (node (ref "R20") (pin "1") (pinfunction "1_1") (pintype "passive"))
      (node (ref "U$8") (pin "1") (pinfunction "1_1") (pintype "passive"))
      (node (ref "U2") (pin "16") (pinfunction "OUT1_16") (pintype "output"))
    )
    (net (code "236") (name "OUT_MZ_HOMING") (class "Default")
      (node (ref "MOTZ") (pin "10") (pinfunction "10_10") (pintype "passive"))
      (node (ref "R21") (pin "1") (pinfunction "1_1") (pintype "passive"))
      (node (ref "U$9") (pin "1") (pinfunction "1_1") (pintype "passive"))
      (node (ref "U2") (pin "15") (pinfunction "OUT2_15") (pintype "output"))
    )
    (net (code "237") (name "TEMP") (class "Default")
      (node (ref "IC1") (pin "10") (pinfunction "+IN_10") (pintype "input"))
      (node (ref "U3") (pin "2") (pinfunction "VOUT_2") (pintype "passive"))
    )
    (net (code "238") (name "VS_3V3") (class "Default")
      (node (ref "IC5") (pin "13") (pinfunction "-IN_13") (pintype "input"))
      (node (ref "IC5") (pin "14") (pinfunction "OUT_14") (pintype "output"))
      (node (ref "IC5") (pin "2") (pinfunction "-IN_2") (pintype "input"))
      (node (ref "IC5") (pin "6") (pinfunction "-IN_6") (pintype "input"))
      (node (ref "IC5") (pin "9") (pinfunction "-IN_9") (pintype "input"))
    )
    (net (code "239") (name "VS_5V") (class "Default")
      (node (ref "IC11") (pin "13") (pinfunction "-IN_13") (pintype "input"))
      (node (ref "IC11") (pin "2") (pinfunction "-IN_2") (pintype "input"))
      (node (ref "IC11") (pin "6") (pinfunction "-IN_6") (pintype "input"))
      (node (ref "IC11") (pin "9") (pinfunction "-IN_9") (pintype "input"))
      (node (ref "IC7") (pin "13") (pinfunction "-IN_13") (pintype "input"))
      (node (ref "IC7") (pin "14") (pinfunction "OUT_14") (pintype "output"))
      (node (ref "IC7") (pin "2") (pinfunction "-IN_2") (pintype "input"))
      (node (ref "IC7") (pin "6") (pinfunction "-IN_6") (pintype "input"))
      (node (ref "IC7") (pin "9") (pinfunction "-IN_9") (pintype "input"))
    )
    (net (code "240") (name "VS_IN_ARD") (class "Default")
      (node (ref "IC12") (pin "1") (pinfunction "OUT_1") (pintype "output"))
      (node (ref "IC12") (pin "13") (pinfunction "-IN_13") (pintype "input"))
      (node (ref "IC12") (pin "2") (pinfunction "-IN_2") (pintype "input"))
      (node (ref "IC12") (pin "6") (pinfunction "-IN_6") (pintype "input"))
      (node (ref "IC12") (pin "9") (pinfunction "-IN_9") (pintype "input"))
      (node (ref "IC13") (pin "13") (pinfunction "-IN_13") (pintype "input"))
      (node (ref "IC13") (pin "2") (pinfunction "-IN_2") (pintype "input"))
      (node (ref "IC13") (pin "6") (pinfunction "-IN_6") (pintype "input"))
      (node (ref "IC13") (pin "9") (pinfunction "-IN_9") (pintype "input"))
      (node (ref "IC14") (pin "2") (pinfunction "-IN_2") (pintype "input"))
      (node (ref "IC14") (pin "6") (pinfunction "-IN_6") (pintype "input"))
      (node (ref "IC14") (pin "9") (pinfunction "-IN_9") (pintype "input"))
    )
    (net (code "241") (name "VS_IN_EDGE") (class "Default")
      (node (ref "IC15") (pin "1") (pinfunction "OUT_1") (pintype "output"))
      (node (ref "IC15") (pin "13") (pinfunction "-IN_13") (pintype "input"))
      (node (ref "IC15") (pin "2") (pinfunction "-IN_2") (pintype "input"))
      (node (ref "IC15") (pin "6") (pinfunction "-IN_6") (pintype "input"))
      (node (ref "IC15") (pin "9") (pinfunction "-IN_9") (pintype "input"))
      (node (ref "IC16") (pin "13") (pinfunction "-IN_13") (pintype "input"))
      (node (ref "IC16") (pin "2") (pinfunction "-IN_2") (pintype "input"))
      (node (ref "IC16") (pin "6") (pinfunction "-IN_6") (pintype "input"))
      (node (ref "IC16") (pin "9") (pinfunction "-IN_9") (pintype "input"))
      (node (ref "IC17") (pin "2") (pinfunction "-IN_2") (pintype "input"))
      (node (ref "IC17") (pin "6") (pinfunction "-IN_6") (pintype "input"))
      (node (ref "IC17") (pin "9") (pinfunction "-IN_9") (pintype "input"))
    )
    (net (code "242") (name "VS_TEMP") (class "Default")
      (node (ref "IC1") (pin "13") (pinfunction "-IN_13") (pintype "input"))
      (node (ref "IC1") (pin "14") (pinfunction "OUT_14") (pintype "output"))
      (node (ref "IC1") (pin "9") (pinfunction "-IN_9") (pintype "input"))
    )
    (net (code "243") (name "unconnected-(J1/J3-2-Pad11)") (class "Default")
      (node (ref "J1/J3") (pin "11") (pinfunction "2_11") (pintype "passive"))
    )
    (net (code "244") (name "unconnected-(J1/J3-3-Pad2)") (class "Default")
      (node (ref "J1/J3") (pin "2") (pinfunction "3_2") (pintype "passive"))
    )
    (net (code "245") (name "unconnected-(J1/J3-6-Pad13)") (class "Default")
      (node (ref "J1/J3") (pin "13") (pinfunction "6_13") (pintype "passive"))
    )
    (net (code "246") (name "unconnected-(J1/J3-8-Pad14)") (class "Default")
      (node (ref "J1/J3") (pin "14") (pinfunction "8_14") (pintype "passive"))
    )
    (net (code "247") (name "unconnected-(J1/J3-10-Pad15)") (class "Default")
      (node (ref "J1/J3") (pin "15") (pinfunction "10_15") (pintype "passive"))
    )
    (net (code "248") (name "unconnected-(J1/J3-11-Pad6)") (class "Default")
      (node (ref "J1/J3") (pin "6") (pinfunction "11_6") (pintype "passive"))
    )
    (net (code "249") (name "unconnected-(J1/J3-12-Pad16)") (class "Default")
      (node (ref "J1/J3") (pin "16") (pinfunction "12_16") (pintype "passive"))
    )
    (net (code "250") (name "unconnected-(J1/J3-14-Pad17)") (class "Default")
      (node (ref "J1/J3") (pin "17") (pinfunction "14_17") (pintype "passive"))
    )
    (net (code "251") (name "unconnected-(J1/J3-16-Pad18)") (class "Default")
      (node (ref "J1/J3") (pin "18") (pinfunction "16_18") (pintype "passive"))
    )
    (net (code "252") (name "unconnected-(J1/J3-18-Pad19)") (class "Default")
      (node (ref "J1/J3") (pin "19") (pinfunction "18_19") (pintype "passive"))
    )
    (net (code "253") (name "unconnected-(J1/J3-Pad1)") (class "Default")
      (node (ref "J1/J3") (pin "1") (pinfunction "1_1") (pintype "passive"))
    )
    (net (code "254") (name "unconnected-(J1/J3-Pad20)") (class "Default")
      (node (ref "J1/J3") (pin "20") (pinfunction "20_20") (pintype "passive"))
    )
    (net (code "255") (name "unconnected-(J3-Pad7)") (class "Default")
      (node (ref "J3") (pin "7") (pinfunction "7_7") (pintype "passive"))
    )
    (net (code "256") (name "unconnected-(J3-Pad8)") (class "Default")
      (node (ref "J3") (pin "8") (pinfunction "8_8") (pintype "passive"))
    )
    (net (code "257") (name "unconnected-(J3-Pad9)") (class "Default")
      (node (ref "J3") (pin "9") (pinfunction "9_9") (pintype "passive"))
    )
    (net (code "258") (name "unconnected-(J3-Pad10)") (class "Default")
      (node (ref "J3") (pin "10") (pinfunction "10_10") (pintype "passive"))
    )
    (net (code "259") (name "unconnected-(J4/J2-4-Pad12)") (class "Default")
      (node (ref "J4/J2") (pin "12") (pinfunction "4_12") (pintype "passive"))
    )
    (net (code "260") (name "unconnected-(J4/J2-6-Pad13)") (class "Default")
      (node (ref "J4/J2") (pin "13") (pinfunction "6_13") (pintype "passive"))
    )
    (net (code "261") (name "unconnected-(J4/J2-7-Pad4)") (class "Default")
      (node (ref "J4/J2") (pin "4") (pinfunction "7_4") (pintype "passive"))
    )
    (net (code "262") (name "unconnected-(J4/J2-8-Pad14)") (class "Default")
      (node (ref "J4/J2") (pin "14") (pinfunction "8_14") (pintype "passive"))
    )
    (net (code "263") (name "unconnected-(J4/J2-10-Pad15)") (class "Default")
      (node (ref "J4/J2") (pin "15") (pinfunction "10_15") (pintype "passive"))
    )
    (net (code "264") (name "unconnected-(J4/J2-12-Pad16)") (class "Default")
      (node (ref "J4/J2") (pin "16") (pinfunction "12_16") (pintype "passive"))
    )
    (net (code "265") (name "unconnected-(J4/J2-14-Pad17)") (class "Default")
      (node (ref "J4/J2") (pin "17") (pinfunction "14_17") (pintype "passive"))
    )
    (net (code "266") (name "unconnected-(J4/J2-16-Pad18)") (class "Default")
      (node (ref "J4/J2") (pin "18") (pinfunction "16_18") (pintype "passive"))
    )
    (net (code "267") (name "unconnected-(J4/J2-18-Pad19)") (class "Default")
      (node (ref "J4/J2") (pin "19") (pinfunction "18_19") (pintype "passive"))
    )
    (net (code "268") (name "unconnected-(J4/J2-19-Pad10)") (class "Default")
      (node (ref "J4/J2") (pin "10") (pinfunction "19_10") (pintype "passive"))
    )
    (net (code "269") (name "unconnected-(J5/J7-2-Pad11)") (class "Default")
      (node (ref "J5/J7") (pin "11") (pinfunction "2_11") (pintype "passive"))
    )
    (net (code "270") (name "unconnected-(J5/J7-3-Pad2)") (class "Default")
      (node (ref "J5/J7") (pin "2") (pinfunction "3_2") (pintype "passive"))
    )
    (net (code "271") (name "unconnected-(J5/J7-5-Pad3)") (class "Default")
      (node (ref "J5/J7") (pin "3") (pinfunction "5_3") (pintype "passive"))
    )
    (net (code "272") (name "unconnected-(J5/J7-6-Pad13)") (class "Default")
      (node (ref "J5/J7") (pin "13") (pinfunction "6_13") (pintype "passive"))
    )
    (net (code "273") (name "unconnected-(J5/J7-7-Pad4)") (class "Default")
      (node (ref "J5/J7") (pin "4") (pinfunction "7_4") (pintype "passive"))
    )
    (net (code "274") (name "unconnected-(J5/J7-8-Pad14)") (class "Default")
      (node (ref "J5/J7") (pin "14") (pinfunction "8_14") (pintype "passive"))
    )
    (net (code "275") (name "unconnected-(J5/J7-10-Pad15)") (class "Default")
      (node (ref "J5/J7") (pin "15") (pinfunction "10_15") (pintype "passive"))
    )
    (net (code "276") (name "unconnected-(J5/J7-11-Pad6)") (class "Default")
      (node (ref "J5/J7") (pin "6") (pinfunction "11_6") (pintype "passive"))
    )
    (net (code "277") (name "unconnected-(J5/J7-12-Pad16)") (class "Default")
      (node (ref "J5/J7") (pin "16") (pinfunction "12_16") (pintype "passive"))
    )
    (net (code "278") (name "unconnected-(J5/J7-13-Pad7)") (class "Default")
      (node (ref "J5/J7") (pin "7") (pinfunction "13_7") (pintype "passive"))
    )
    (net (code "279") (name "unconnected-(J5/J7-14-Pad17)") (class "Default")
      (node (ref "J5/J7") (pin "17") (pinfunction "14_17") (pintype "passive"))
    )
    (net (code "280") (name "unconnected-(J5/J7-16-Pad18)") (class "Default")
      (node (ref "J5/J7") (pin "18") (pinfunction "16_18") (pintype "passive"))
    )
    (net (code "281") (name "unconnected-(J5/J7-18-Pad19)") (class "Default")
      (node (ref "J5/J7") (pin "19") (pinfunction "18_19") (pintype "passive"))
    )
    (net (code "282") (name "unconnected-(J5/J7-19-Pad10)") (class "Default")
      (node (ref "J5/J7") (pin "10") (pinfunction "19_10") (pintype "passive"))
    )
    (net (code "283") (name "unconnected-(J5/J7-Pad1)") (class "Default")
      (node (ref "J5/J7") (pin "1") (pinfunction "1_1") (pintype "passive"))
    )
    (net (code "284") (name "unconnected-(J5/J7-Pad20)") (class "Default")
      (node (ref "J5/J7") (pin "20") (pinfunction "20_20") (pintype "passive"))
    )
    (net (code "285") (name "unconnected-(J6-Pad7)") (class "Default")
      (node (ref "J6") (pin "7") (pinfunction "7_7") (pintype "passive"))
    )
    (net (code "286") (name "unconnected-(J6-Pad8)") (class "Default")
      (node (ref "J6") (pin "8") (pinfunction "8_8") (pintype "passive"))
    )
    (net (code "287") (name "unconnected-(J6-Pad9)") (class "Default")
      (node (ref "J6") (pin "9") (pinfunction "9_9") (pintype "passive"))
    )
    (net (code "288") (name "unconnected-(J6-Pad10)") (class "Default")
      (node (ref "J6") (pin "10") (pinfunction "10_10") (pintype "passive"))
    )
    (net (code "289") (name "unconnected-(J7-Pad5)") (class "Default")
      (node (ref "J7") (pin "5") (pinfunction "5_5") (pintype "passive"))
    )
    (net (code "290") (name "unconnected-(J7-Pad6)") (class "Default")
      (node (ref "J7") (pin "6") (pinfunction "6_6") (pintype "passive"))
    )
    (net (code "291") (name "unconnected-(J7-Pad7)") (class "Default")
      (node (ref "J7") (pin "7") (pinfunction "7_7") (pintype "passive"))
    )
    (net (code "292") (name "unconnected-(J7-Pad8)") (class "Default")
      (node (ref "J7") (pin "8") (pinfunction "8_8") (pintype "passive"))
    )
    (net (code "293") (name "unconnected-(J7-Pad9)") (class "Default")
      (node (ref "J7") (pin "9") (pinfunction "9_9") (pintype "passive"))
    )
    (net (code "294") (name "unconnected-(J7-Pad10)") (class "Default")
      (node (ref "J7") (pin "10") (pinfunction "10_10") (pintype "passive"))
    )
    (net (code "295") (name "unconnected-(J8-16-Pad18)") (class "Default")
      (node (ref "J8") (pin "18") (pinfunction "16_18") (pintype "passive"))
    )
    (net (code "296") (name "unconnected-(J8-18-Pad19)") (class "Default")
      (node (ref "J8") (pin "19") (pinfunction "18_19") (pintype "passive"))
    )
    (net (code "297") (name "unconnected-(J8-Pad20)") (class "Default")
      (node (ref "J8") (pin "20") (pinfunction "20_20") (pintype "passive"))
    )
    (net (code "298") (name "unconnected-(J8/J6-6-Pad13)") (class "Default")
      (node (ref "J8/J6") (pin "13") (pinfunction "6_13") (pintype "passive"))
    )
    (net (code "299") (name "unconnected-(J8/J6-8-Pad14)") (class "Default")
      (node (ref "J8/J6") (pin "14") (pinfunction "8_14") (pintype "passive"))
    )
    (net (code "300") (name "unconnected-(J8/J6-9-Pad5)") (class "Default")
      (node (ref "J8/J6") (pin "5") (pinfunction "9_5") (pintype "passive"))
    )
    (net (code "301") (name "unconnected-(J8/J6-10-Pad15)") (class "Default")
      (node (ref "J8/J6") (pin "15") (pinfunction "10_15") (pintype "passive"))
    )
    (net (code "302") (name "unconnected-(J8/J6-12-Pad16)") (class "Default")
      (node (ref "J8/J6") (pin "16") (pinfunction "12_16") (pintype "passive"))
    )
    (net (code "303") (name "unconnected-(J8/J6-13-Pad7)") (class "Default")
      (node (ref "J8/J6") (pin "7") (pinfunction "13_7") (pintype "passive"))
    )
    (net (code "304") (name "unconnected-(J8/J6-14-Pad17)") (class "Default")
      (node (ref "J8/J6") (pin "17") (pinfunction "14_17") (pintype "passive"))
    )
    (net (code "305") (name "unconnected-(J8/J6-15-Pad8)") (class "Default")
      (node (ref "J8/J6") (pin "8") (pinfunction "15_8") (pintype "passive"))
    )
    (net (code "306") (name "unconnected-(J8/J6-16-Pad18)") (class "Default")
      (node (ref "J8/J6") (pin "18") (pinfunction "16_18") (pintype "passive"))
    )
    (net (code "307") (name "unconnected-(J8/J6-17-Pad9)") (class "Default")
      (node (ref "J8/J6") (pin "9") (pinfunction "17_9") (pintype "passive"))
    )
    (net (code "308") (name "unconnected-(J8/J6-18-Pad19)") (class "Default")
      (node (ref "J8/J6") (pin "19") (pinfunction "18_19") (pintype "passive"))
    )
    (net (code "309") (name "unconnected-(J8/J6-19-Pad10)") (class "Default")
      (node (ref "J8/J6") (pin "10") (pinfunction "19_10") (pintype "passive"))
    )
    (net (code "310") (name "unconnected-(J8/J6-Pad20)") (class "Default")
      (node (ref "J8/J6") (pin "20") (pinfunction "20_20") (pintype "passive"))
    )
    (net (code "311") (name "unconnected-(J9-Pad1)") (class "Default")
      (node (ref "J9") (pin "1") (pinfunction "1_1") (pintype "passive"))
    )
    (net (code "312") (name "unconnected-(J9-Pad3)") (class "Default")
      (node (ref "J9") (pin "3") (pinfunction "3_3") (pintype "passive"))
    )
    (net (code "313") (name "unconnected-(J9-Pad5)") (class "Default")
      (node (ref "J9") (pin "5") (pinfunction "5_5") (pintype "passive"))
    )
    (net (code "314") (name "unconnected-(J9-Pad6)") (class "Default")
      (node (ref "J9") (pin "6") (pinfunction "6_6") (pintype "passive"))
    )
    (net (code "315") (name "unconnected-(J9-Pad7)") (class "Default")
      (node (ref "J9") (pin "7") (pinfunction "7_7") (pintype "passive"))
    )
    (net (code "316") (name "unconnected-(J9-Pad9)") (class "Default")
      (node (ref "J9") (pin "9") (pinfunction "9_9") (pintype "passive"))
    )
    (net (code "317") (name "unconnected-(J9-Pad12)") (class "Default")
      (node (ref "J9") (pin "12") (pinfunction "12_12") (pintype "passive"))
    )
    (net (code "318") (name "unconnected-(J9-Pad13)") (class "Default")
      (node (ref "J9") (pin "13") (pinfunction "13_13") (pintype "passive"))
    )
    (net (code "319") (name "unconnected-(J9-Pad19)") (class "Default")
      (node (ref "J9") (pin "19") (pinfunction "19_19") (pintype "passive"))
    )
    (net (code "320") (name "unconnected-(J9-Pad21)") (class "Default")
      (node (ref "J9") (pin "21") (pinfunction "21_21") (pintype "passive"))
    )
    (net (code "321") (name "unconnected-(J9-Pad29)") (class "Default")
      (node (ref "J9") (pin "29") (pinfunction "29_29") (pintype "passive"))
    )
    (net (code "322") (name "unconnected-(J9-Pad30)") (class "Default")
      (node (ref "J9") (pin "30") (pinfunction "30_30") (pintype "passive"))
    )
    (net (code "323") (name "unconnected-(J9-Pad31)") (class "Default")
      (node (ref "J9") (pin "31") (pinfunction "31_31") (pintype "passive"))
    )
    (net (code "324") (name "unconnected-(J9-Pad32)") (class "Default")
      (node (ref "J9") (pin "32") (pinfunction "32_32") (pintype "passive"))
    )
    (net (code "325") (name "unconnected-(J9-Pad33)") (class "Default")
      (node (ref "J9") (pin "33") (pinfunction "33_33") (pintype "passive"))
    )
    (net (code "326") (name "unconnected-(J9-Pad35)") (class "Default")
      (node (ref "J9") (pin "35") (pinfunction "35_35") (pintype "passive"))
    )
    (net (code "327") (name "unconnected-(J9-Pad36)") (class "Default")
      (node (ref "J9") (pin "36") (pinfunction "36_36") (pintype "passive"))
    )
    (net (code "328") (name "unconnected-(J9-Pad37)") (class "Default")
      (node (ref "J9") (pin "37") (pinfunction "37_37") (pintype "passive"))
    )
    (net (code "329") (name "unconnected-(J9-Pad38)") (class "Default")
      (node (ref "J9") (pin "38") (pinfunction "38_38") (pintype "passive"))
    )
    (net (code "330") (name "unconnected-(J9-Pad39)") (class "Default")
      (node (ref "J9") (pin "39") (pinfunction "39_39") (pintype "passive"))
    )
    (net (code "331") (name "unconnected-(J9-Pad40)") (class "Default")
      (node (ref "J9") (pin "40") (pinfunction "40_40") (pintype "passive"))
    )
    (net (code "332") (name "unconnected-(J9-Pad41)") (class "Default")
      (node (ref "J9") (pin "41") (pinfunction "41_41") (pintype "passive"))
    )
    (net (code "333") (name "unconnected-(J9-Pad42)") (class "Default")
      (node (ref "J9") (pin "42") (pinfunction "42_42") (pintype "passive"))
    )
    (net (code "334") (name "unconnected-(J9-Pad43)") (class "Default")
      (node (ref "J9") (pin "43") (pinfunction "43_43") (pintype "passive"))
    )
    (net (code "335") (name "unconnected-(J9-Pad44)") (class "Default")
      (node (ref "J9") (pin "44") (pinfunction "44_44") (pintype "passive"))
    )
    (net (code "336") (name "unconnected-(J9-Pad45)") (class "Default")
      (node (ref "J9") (pin "45") (pinfunction "45_45") (pintype "passive"))
    )
    (net (code "337") (name "unconnected-(J9-Pad46)") (class "Default")
      (node (ref "J9") (pin "46") (pinfunction "46_46") (pintype "passive"))
    )
    (net (code "338") (name "unconnected-(J9-Pad47)") (class "Default")
      (node (ref "J9") (pin "47") (pinfunction "47_47") (pintype "passive"))
    )
    (net (code "339") (name "unconnected-(J9-Pad48)") (class "Default")
      (node (ref "J9") (pin "48") (pinfunction "48_48") (pintype "passive"))
    )
    (net (code "340") (name "unconnected-(J9-Pad49)") (class "Default")
      (node (ref "J9") (pin "49") (pinfunction "49_49") (pintype "passive"))
    )
    (net (code "341") (name "unconnected-(J9-Pad50)") (class "Default")
      (node (ref "J9") (pin "50") (pinfunction "50_50") (pintype "passive"))
    )
    (net (code "342") (name "unconnected-(J10-Pad1)") (class "Default")
      (node (ref "J10") (pin "1") (pinfunction "1_1") (pintype "passive"))
    )
    (net (code "343") (name "unconnected-(J10-Pad3)") (class "Default")
      (node (ref "J10") (pin "3") (pinfunction "3_3") (pintype "passive"))
    )
    (net (code "344") (name "unconnected-(J10-Pad5)") (class "Default")
      (node (ref "J10") (pin "5") (pinfunction "5_5") (pintype "passive"))
    )
    (net (code "345") (name "unconnected-(J10-Pad10)") (class "Default")
      (node (ref "J10") (pin "10") (pinfunction "10_10") (pintype "passive"))
    )
    (net (code "346") (name "unconnected-(J10-Pad11)") (class "Default")
      (node (ref "J10") (pin "11") (pinfunction "11_11") (pintype "passive"))
    )
    (net (code "347") (name "unconnected-(J10-Pad12)") (class "Default")
      (node (ref "J10") (pin "12") (pinfunction "12_12") (pintype "passive"))
    )
    (net (code "348") (name "unconnected-(J10-Pad13)") (class "Default")
      (node (ref "J10") (pin "13") (pinfunction "13_13") (pintype "passive"))
    )
    (net (code "349") (name "unconnected-(J10-Pad15)") (class "Default")
      (node (ref "J10") (pin "15") (pinfunction "15_15") (pintype "passive"))
    )
    (net (code "350") (name "unconnected-(J10-Pad16)") (class "Default")
      (node (ref "J10") (pin "16") (pinfunction "16_16") (pintype "passive"))
    )
    (net (code "351") (name "unconnected-(J10-Pad17)") (class "Default")
      (node (ref "J10") (pin "17") (pinfunction "17_17") (pintype "passive"))
    )
    (net (code "352") (name "unconnected-(J10-Pad20)") (class "Default")
      (node (ref "J10") (pin "20") (pinfunction "20_20") (pintype "passive"))
    )
    (net (code "353") (name "unconnected-(J10-Pad21)") (class "Default")
      (node (ref "J10") (pin "21") (pinfunction "21_21") (pintype "passive"))
    )
    (net (code "354") (name "unconnected-(J10-Pad24)") (class "Default")
      (node (ref "J10") (pin "24") (pinfunction "24_24") (pintype "passive"))
    )
    (net (code "355") (name "unconnected-(J10-Pad25)") (class "Default")
      (node (ref "J10") (pin "25") (pinfunction "25_25") (pintype "passive"))
    )
    (net (code "356") (name "unconnected-(J10-Pad26)") (class "Default")
      (node (ref "J10") (pin "26") (pinfunction "26_26") (pintype "passive"))
    )
    (net (code "357") (name "unconnected-(J10-Pad27)") (class "Default")
      (node (ref "J10") (pin "27") (pinfunction "27_27") (pintype "passive"))
    )
    (net (code "358") (name "unconnected-(J10-Pad28)") (class "Default")
      (node (ref "J10") (pin "28") (pinfunction "28_28") (pintype "passive"))
    )
    (net (code "359") (name "unconnected-(J10-Pad29)") (class "Default")
      (node (ref "J10") (pin "29") (pinfunction "29_29") (pintype "passive"))
    )
    (net (code "360") (name "unconnected-(J10-Pad30)") (class "Default")
      (node (ref "J10") (pin "30") (pinfunction "30_30") (pintype "passive"))
    )
    (net (code "361") (name "unconnected-(J10-Pad31)") (class "Default")
      (node (ref "J10") (pin "31") (pinfunction "31_31") (pintype "passive"))
    )
    (net (code "362") (name "unconnected-(J10-Pad33)") (class "Default")
      (node (ref "J10") (pin "33") (pinfunction "33_33") (pintype "passive"))
    )
    (net (code "363") (name "unconnected-(J10-Pad35)") (class "Default")
      (node (ref "J10") (pin "35") (pinfunction "35_35") (pintype "passive"))
    )
    (net (code "364") (name "unconnected-(J10-Pad36)") (class "Default")
      (node (ref "J10") (pin "36") (pinfunction "36_36") (pintype "passive"))
    )
    (net (code "365") (name "unconnected-(J10-Pad38)") (class "Default")
      (node (ref "J10") (pin "38") (pinfunction "38_38") (pintype "passive"))
    )
    (net (code "366") (name "unconnected-(J10-Pad40)") (class "Default")
      (node (ref "J10") (pin "40") (pinfunction "40_40") (pintype "passive"))
    )
    (net (code "367") (name "unconnected-(J10-Pad41)") (class "Default")
      (node (ref "J10") (pin "41") (pinfunction "41_41") (pintype "passive"))
    )
    (net (code "368") (name "unconnected-(J10-Pad42)") (class "Default")
      (node (ref "J10") (pin "42") (pinfunction "42_42") (pintype "passive"))
    )
    (net (code "369") (name "unconnected-(J10-Pad43)") (class "Default")
      (node (ref "J10") (pin "43") (pinfunction "43_43") (pintype "passive"))
    )
    (net (code "370") (name "unconnected-(J10-Pad44)") (class "Default")
      (node (ref "J10") (pin "44") (pinfunction "44_44") (pintype "passive"))
    )
    (net (code "371") (name "unconnected-(J10-Pad45)") (class "Default")
      (node (ref "J10") (pin "45") (pinfunction "45_45") (pintype "passive"))
    )
    (net (code "372") (name "unconnected-(J10-Pad46)") (class "Default")
      (node (ref "J10") (pin "46") (pinfunction "46_46") (pintype "passive"))
    )
    (net (code "373") (name "unconnected-(J10-Pad47)") (class "Default")
      (node (ref "J10") (pin "47") (pinfunction "47_47") (pintype "passive"))
    )
    (net (code "374") (name "unconnected-(J10-Pad48)") (class "Default")
      (node (ref "J10") (pin "48") (pinfunction "48_48") (pintype "passive"))
    )
    (net (code "375") (name "unconnected-(J10-Pad49)") (class "Default")
      (node (ref "J10") (pin "49") (pinfunction "49_49") (pintype "passive"))
    )
    (net (code "376") (name "unconnected-(J10-Pad50)") (class "Default")
      (node (ref "J10") (pin "50") (pinfunction "50_50") (pintype "passive"))
    )
    (net (code "377") (name "unconnected-(J_ARD-Pad37)") (class "Default")
      (node (ref "J_ARD") (pin "37") (pinfunction "37_37") (pintype "passive"))
    )
    (net (code "378") (name "unconnected-(J_ARD-Pad38)") (class "Default")
      (node (ref "J_ARD") (pin "38") (pinfunction "38_38") (pintype "passive"))
    )
    (net (code "379") (name "unconnected-(J_ARD-Pad39)") (class "Default")
      (node (ref "J_ARD") (pin "39") (pinfunction "39_39") (pintype "passive"))
    )
    (net (code "380") (name "unconnected-(J_ARD-Pad40)") (class "Default")
      (node (ref "J_ARD") (pin "40") (pinfunction "40_40") (pintype "passive"))
    )
    (net (code "381") (name "unconnected-(J_ARD-Pad41)") (class "Default")
      (node (ref "J_ARD") (pin "41") (pinfunction "41_41") (pintype "passive"))
    )
    (net (code "382") (name "unconnected-(J_ARD-Pad42)") (class "Default")
      (node (ref "J_ARD") (pin "42") (pinfunction "42_42") (pintype "passive"))
    )
    (net (code "383") (name "unconnected-(J_ARD-Pad43)") (class "Default")
      (node (ref "J_ARD") (pin "43") (pinfunction "43_43") (pintype "passive"))
    )
    (net (code "384") (name "unconnected-(J_ARD-Pad44)") (class "Default")
      (node (ref "J_ARD") (pin "44") (pinfunction "44_44") (pintype "passive"))
    )
    (net (code "385") (name "unconnected-(J_ARD-Pad45)") (class "Default")
      (node (ref "J_ARD") (pin "45") (pinfunction "45_45") (pintype "passive"))
    )
    (net (code "386") (name "unconnected-(J_ARD-Pad46)") (class "Default")
      (node (ref "J_ARD") (pin "46") (pinfunction "46_46") (pintype "passive"))
    )
    (net (code "387") (name "unconnected-(J_ARD-Pad47)") (class "Default")
      (node (ref "J_ARD") (pin "47") (pinfunction "47_47") (pintype "passive"))
    )
    (net (code "388") (name "unconnected-(J_ARD-Pad48)") (class "Default")
      (node (ref "J_ARD") (pin "48") (pinfunction "48_48") (pintype "passive"))
    )
    (net (code "389") (name "unconnected-(J_ARD-Pad49)") (class "Default")
      (node (ref "J_ARD") (pin "49") (pinfunction "49_49") (pintype "passive"))
    )
    (net (code "390") (name "unconnected-(J_ARD-Pad50)") (class "Default")
      (node (ref "J_ARD") (pin "50") (pinfunction "50_50") (pintype "passive"))
    )
    (net (code "391") (name "unconnected-(MOTZ-Pad4)") (class "Default")
      (node (ref "MOTZ") (pin "4") (pinfunction "4_4") (pintype "passive"))
    )
    (net (code "392") (name "unconnected-(MOTZ-Pad5)") (class "Default")
      (node (ref "MOTZ") (pin "5") (pinfunction "5_5") (pintype "passive"))
    )
    (net (code "393") (name "unconnected-(SUP_3V3-PadNC)") (class "Default")
      (node (ref "SUP_3V3") (pin "NC") (pinfunction "NC_NC") (pintype "no_connect"))
    )
    (net (code "394") (name "unconnected-(SUP_5V-PadNC)") (class "Default")
      (node (ref "SUP_5V") (pin "NC") (pinfunction "NC_NC") (pintype "no_connect"))
    )
    (net (code "395") (name "unconnected-(U2-IN6-Pad6)") (class "Default")
      (node (ref "U2") (pin "6") (pinfunction "IN6_6") (pintype "input"))
    )
    (net (code "396") (name "unconnected-(U2-IN7-Pad7)") (class "Default")
      (node (ref "U2") (pin "7") (pinfunction "IN7_7") (pintype "input"))
    )
    (net (code "397") (name "unconnected-(U2-OUT6-Pad11)") (class "Default")
      (node (ref "U2") (pin "11") (pinfunction "OUT6_11") (pintype "output"))
    )
    (net (code "398") (name "unconnected-(U2-OUT7-Pad10)") (class "Default")
      (node (ref "U2") (pin "10") (pinfunction "OUT7_10") (pintype "output"))
    )
    (net (code "399") (name "unconnected-(U4-2A1-Pad11)") (class "Default")
      (node (ref "U4") (pin "11") (pinfunction "2A1_11") (pintype "input"))
    )
    (net (code "400") (name "unconnected-(U4-2A2-Pad13)") (class "Default")
      (node (ref "U4") (pin "13") (pinfunction "2A2_13") (pintype "input"))
    )
    (net (code "401") (name "unconnected-(U4-2Y1-Pad9)") (class "Default")
      (node (ref "U4") (pin "9") (pinfunction "2Y1_9") (pintype "output"))
    )
    (net (code "402") (name "unconnected-(U4-2Y2-Pad7)") (class "Default")
      (node (ref "U4") (pin "7") (pinfunction "2Y2_7") (pintype "output"))
    )
    (net (code "403") (name "unconnected-(U5-2A1-Pad11)") (class "Default")
      (node (ref "U5") (pin "11") (pinfunction "2A1_11") (pintype "input"))
    )
    (net (code "404") (name "unconnected-(U5-2A2-Pad13)") (class "Default")
      (node (ref "U5") (pin "13") (pinfunction "2A2_13") (pintype "input"))
    )
    (net (code "405") (name "unconnected-(U5-2A3-Pad15)") (class "Default")
      (node (ref "U5") (pin "15") (pinfunction "2A3_15") (pintype "input"))
    )
    (net (code "406") (name "unconnected-(U5-2A4-Pad17)") (class "Default")
      (node (ref "U5") (pin "17") (pinfunction "2A4_17") (pintype "input"))
    )
    (net (code "407") (name "unconnected-(U5-2Y1-Pad9)") (class "Default")
      (node (ref "U5") (pin "9") (pinfunction "2Y1_9") (pintype "output"))
    )
    (net (code "408") (name "unconnected-(U5-2Y2-Pad7)") (class "Default")
      (node (ref "U5") (pin "7") (pinfunction "2Y2_7") (pintype "output"))
    )
    (net (code "409") (name "unconnected-(U5-2Y3-Pad5)") (class "Default")
      (node (ref "U5") (pin "5") (pinfunction "2Y3_5") (pintype "output"))
    )
    (net (code "410") (name "unconnected-(U5-2Y4-Pad3)") (class "Default")
      (node (ref "U5") (pin "3") (pinfunction "2Y4_3") (pintype "output"))
    )
    (net (code "411") (name "unconnected-(U6-1A2-Pad4)") (class "Default")
      (node (ref "U6") (pin "4") (pinfunction "1A2_4") (pintype "input"))
    )
    (net (code "412") (name "unconnected-(U6-1A3-Pad6)") (class "Default")
      (node (ref "U6") (pin "6") (pinfunction "1A3_6") (pintype "input"))
    )
    (net (code "413") (name "unconnected-(U6-1A4-Pad8)") (class "Default")
      (node (ref "U6") (pin "8") (pinfunction "1A4_8") (pintype "input"))
    )
    (net (code "414") (name "unconnected-(U6-1Y2-Pad16)") (class "Default")
      (node (ref "U6") (pin "16") (pinfunction "1Y2_16") (pintype "output"))
    )
    (net (code "415") (name "unconnected-(U6-1Y3-Pad14)") (class "Default")
      (node (ref "U6") (pin "14") (pinfunction "1Y3_14") (pintype "output"))
    )
    (net (code "416") (name "unconnected-(U6-1Y4-Pad12)") (class "Default")
      (node (ref "U6") (pin "12") (pinfunction "1Y4_12") (pintype "output"))
    )
    (net (code "417") (name "unconnected-(U6-2A1-Pad11)") (class "Default")
      (node (ref "U6") (pin "11") (pinfunction "2A1_11") (pintype "input"))
    )
    (net (code "418") (name "unconnected-(U6-2A2-Pad13)") (class "Default")
      (node (ref "U6") (pin "13") (pinfunction "2A2_13") (pintype "input"))
    )
    (net (code "419") (name "unconnected-(U6-2A3-Pad15)") (class "Default")
      (node (ref "U6") (pin "15") (pinfunction "2A3_15") (pintype "input"))
    )
    (net (code "420") (name "unconnected-(U6-2Y1-Pad9)") (class "Default")
      (node (ref "U6") (pin "9") (pinfunction "2Y1_9") (pintype "output"))
    )
    (net (code "421") (name "unconnected-(U6-2Y2-Pad7)") (class "Default")
      (node (ref "U6") (pin "7") (pinfunction "2Y2_7") (pintype "output"))
    )
    (net (code "422") (name "unconnected-(U6-2Y3-Pad5)") (class "Default")
      (node (ref "U6") (pin "5") (pinfunction "2Y3_5") (pintype "output"))
    )
    (net (code "423") (name "unconnected-(U7-2A1-Pad11)") (class "Default")
      (node (ref "U7") (pin "11") (pinfunction "2A1_11") (pintype "input"))
    )
    (net (code "424") (name "unconnected-(U7-2Y1-Pad9)") (class "Default")
      (node (ref "U7") (pin "9") (pinfunction "2Y1_9") (pintype "output"))
    )
    (net (code "425") (name "unconnected-(U8-NC-Pad3)") (class "Default")
      (node (ref "U8") (pin "3") (pinfunction "NC_3") (pintype "no_connect"))
    )
  )
)
